# smart.net
KiCad netlist of a schematic drawn in Altium Designer
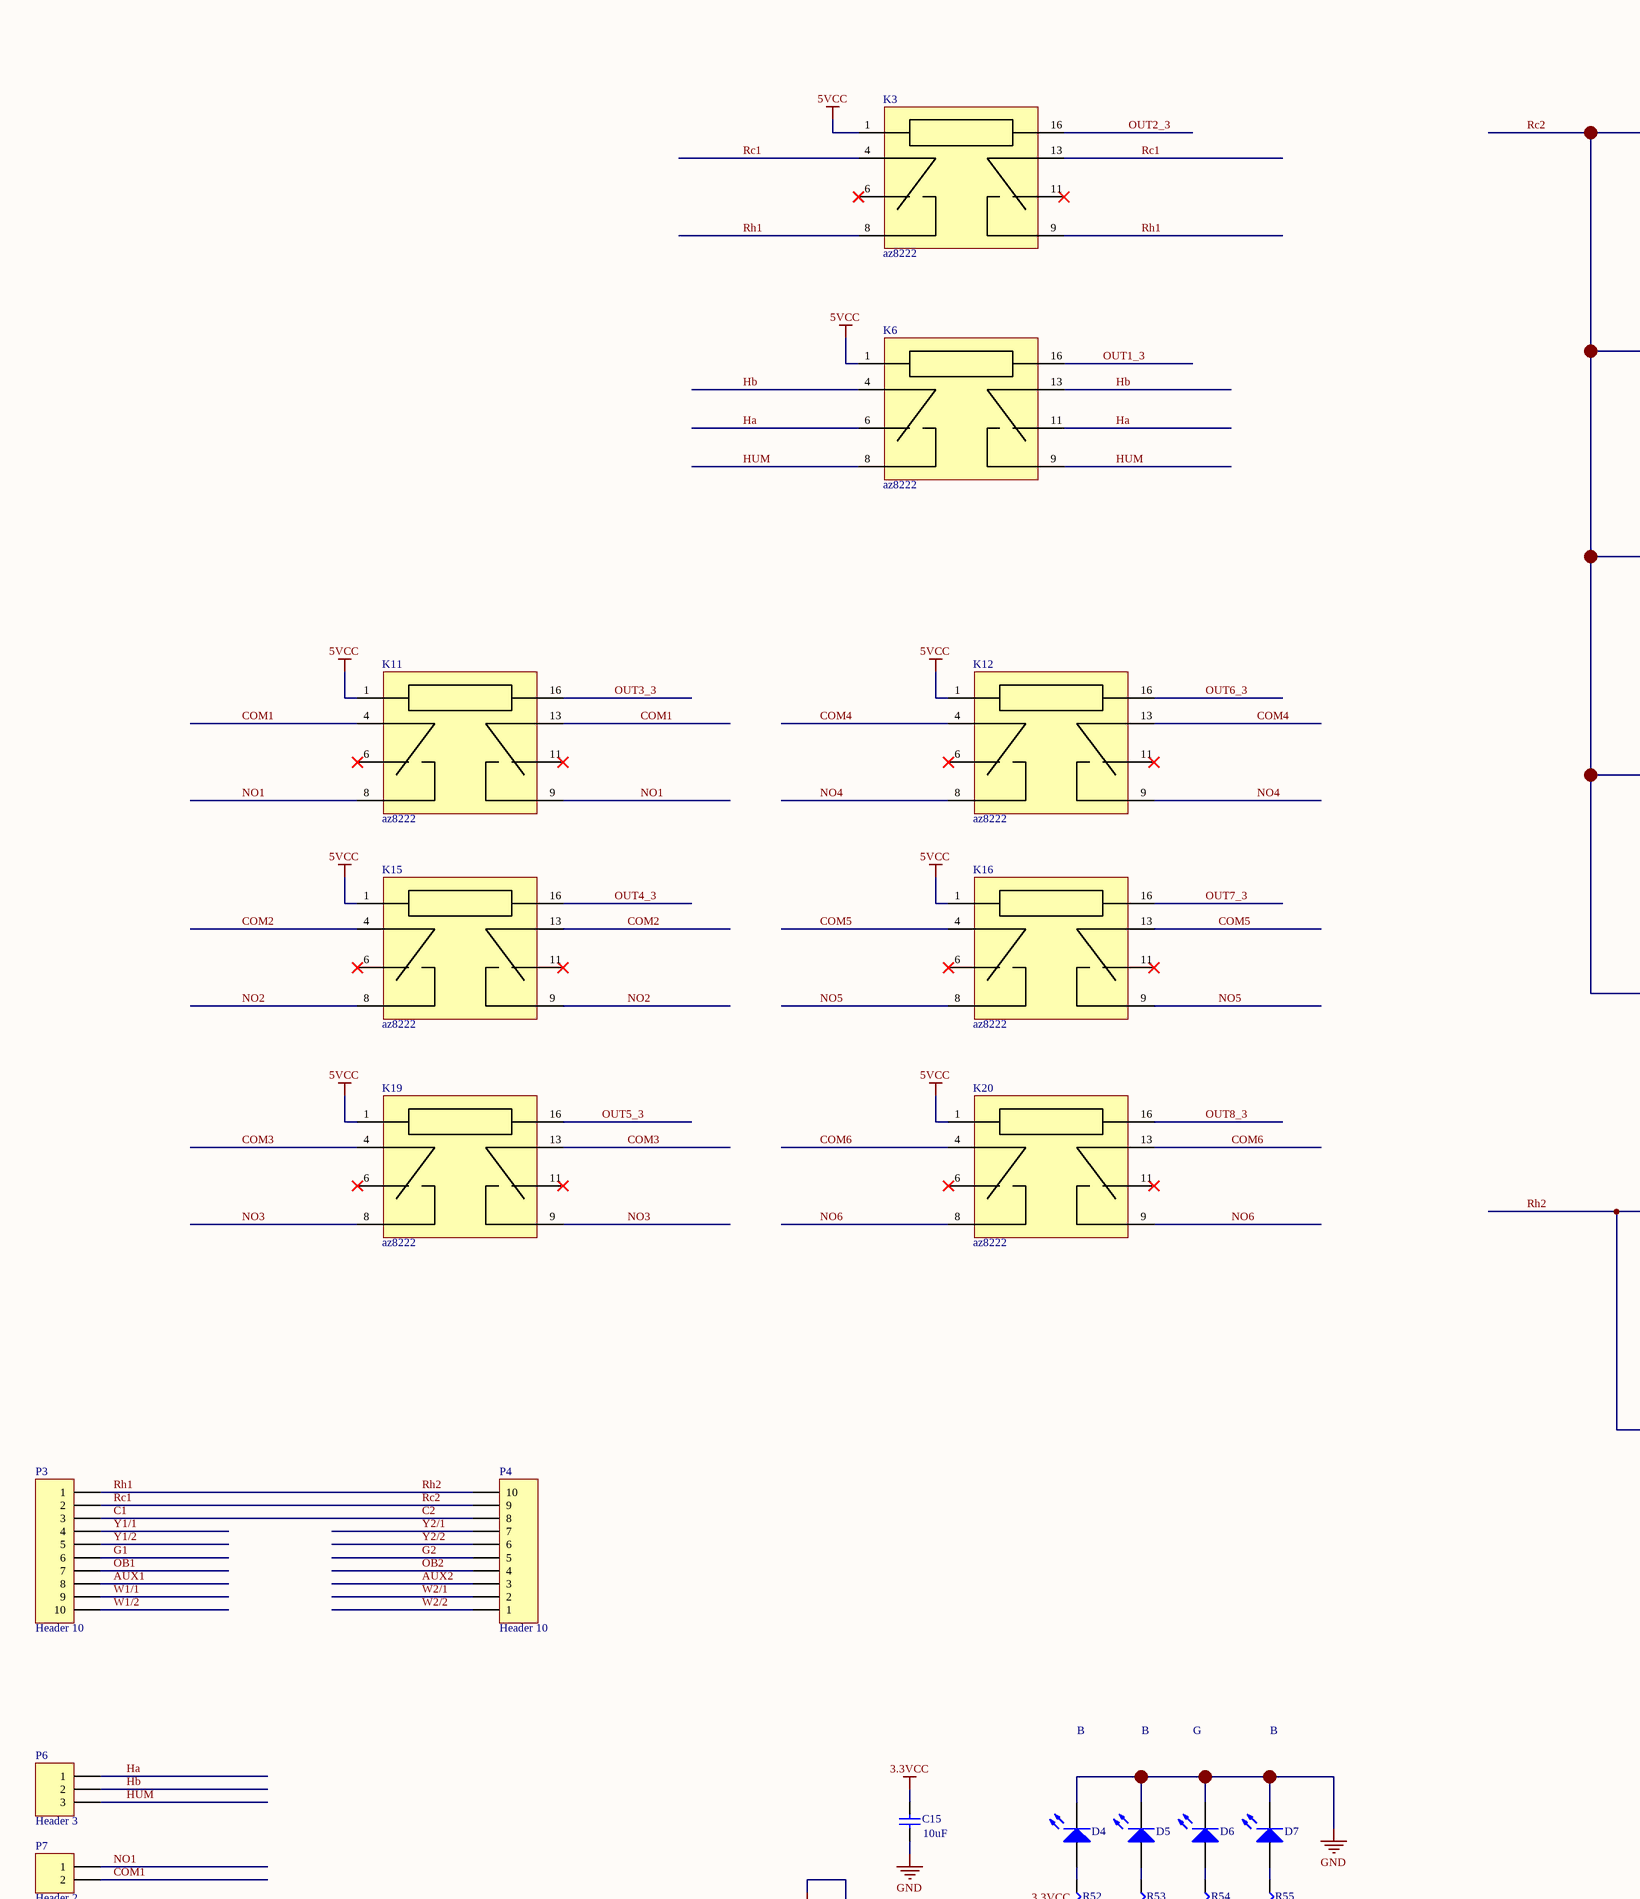
[diagram p0: smart.SchDoc, top left]
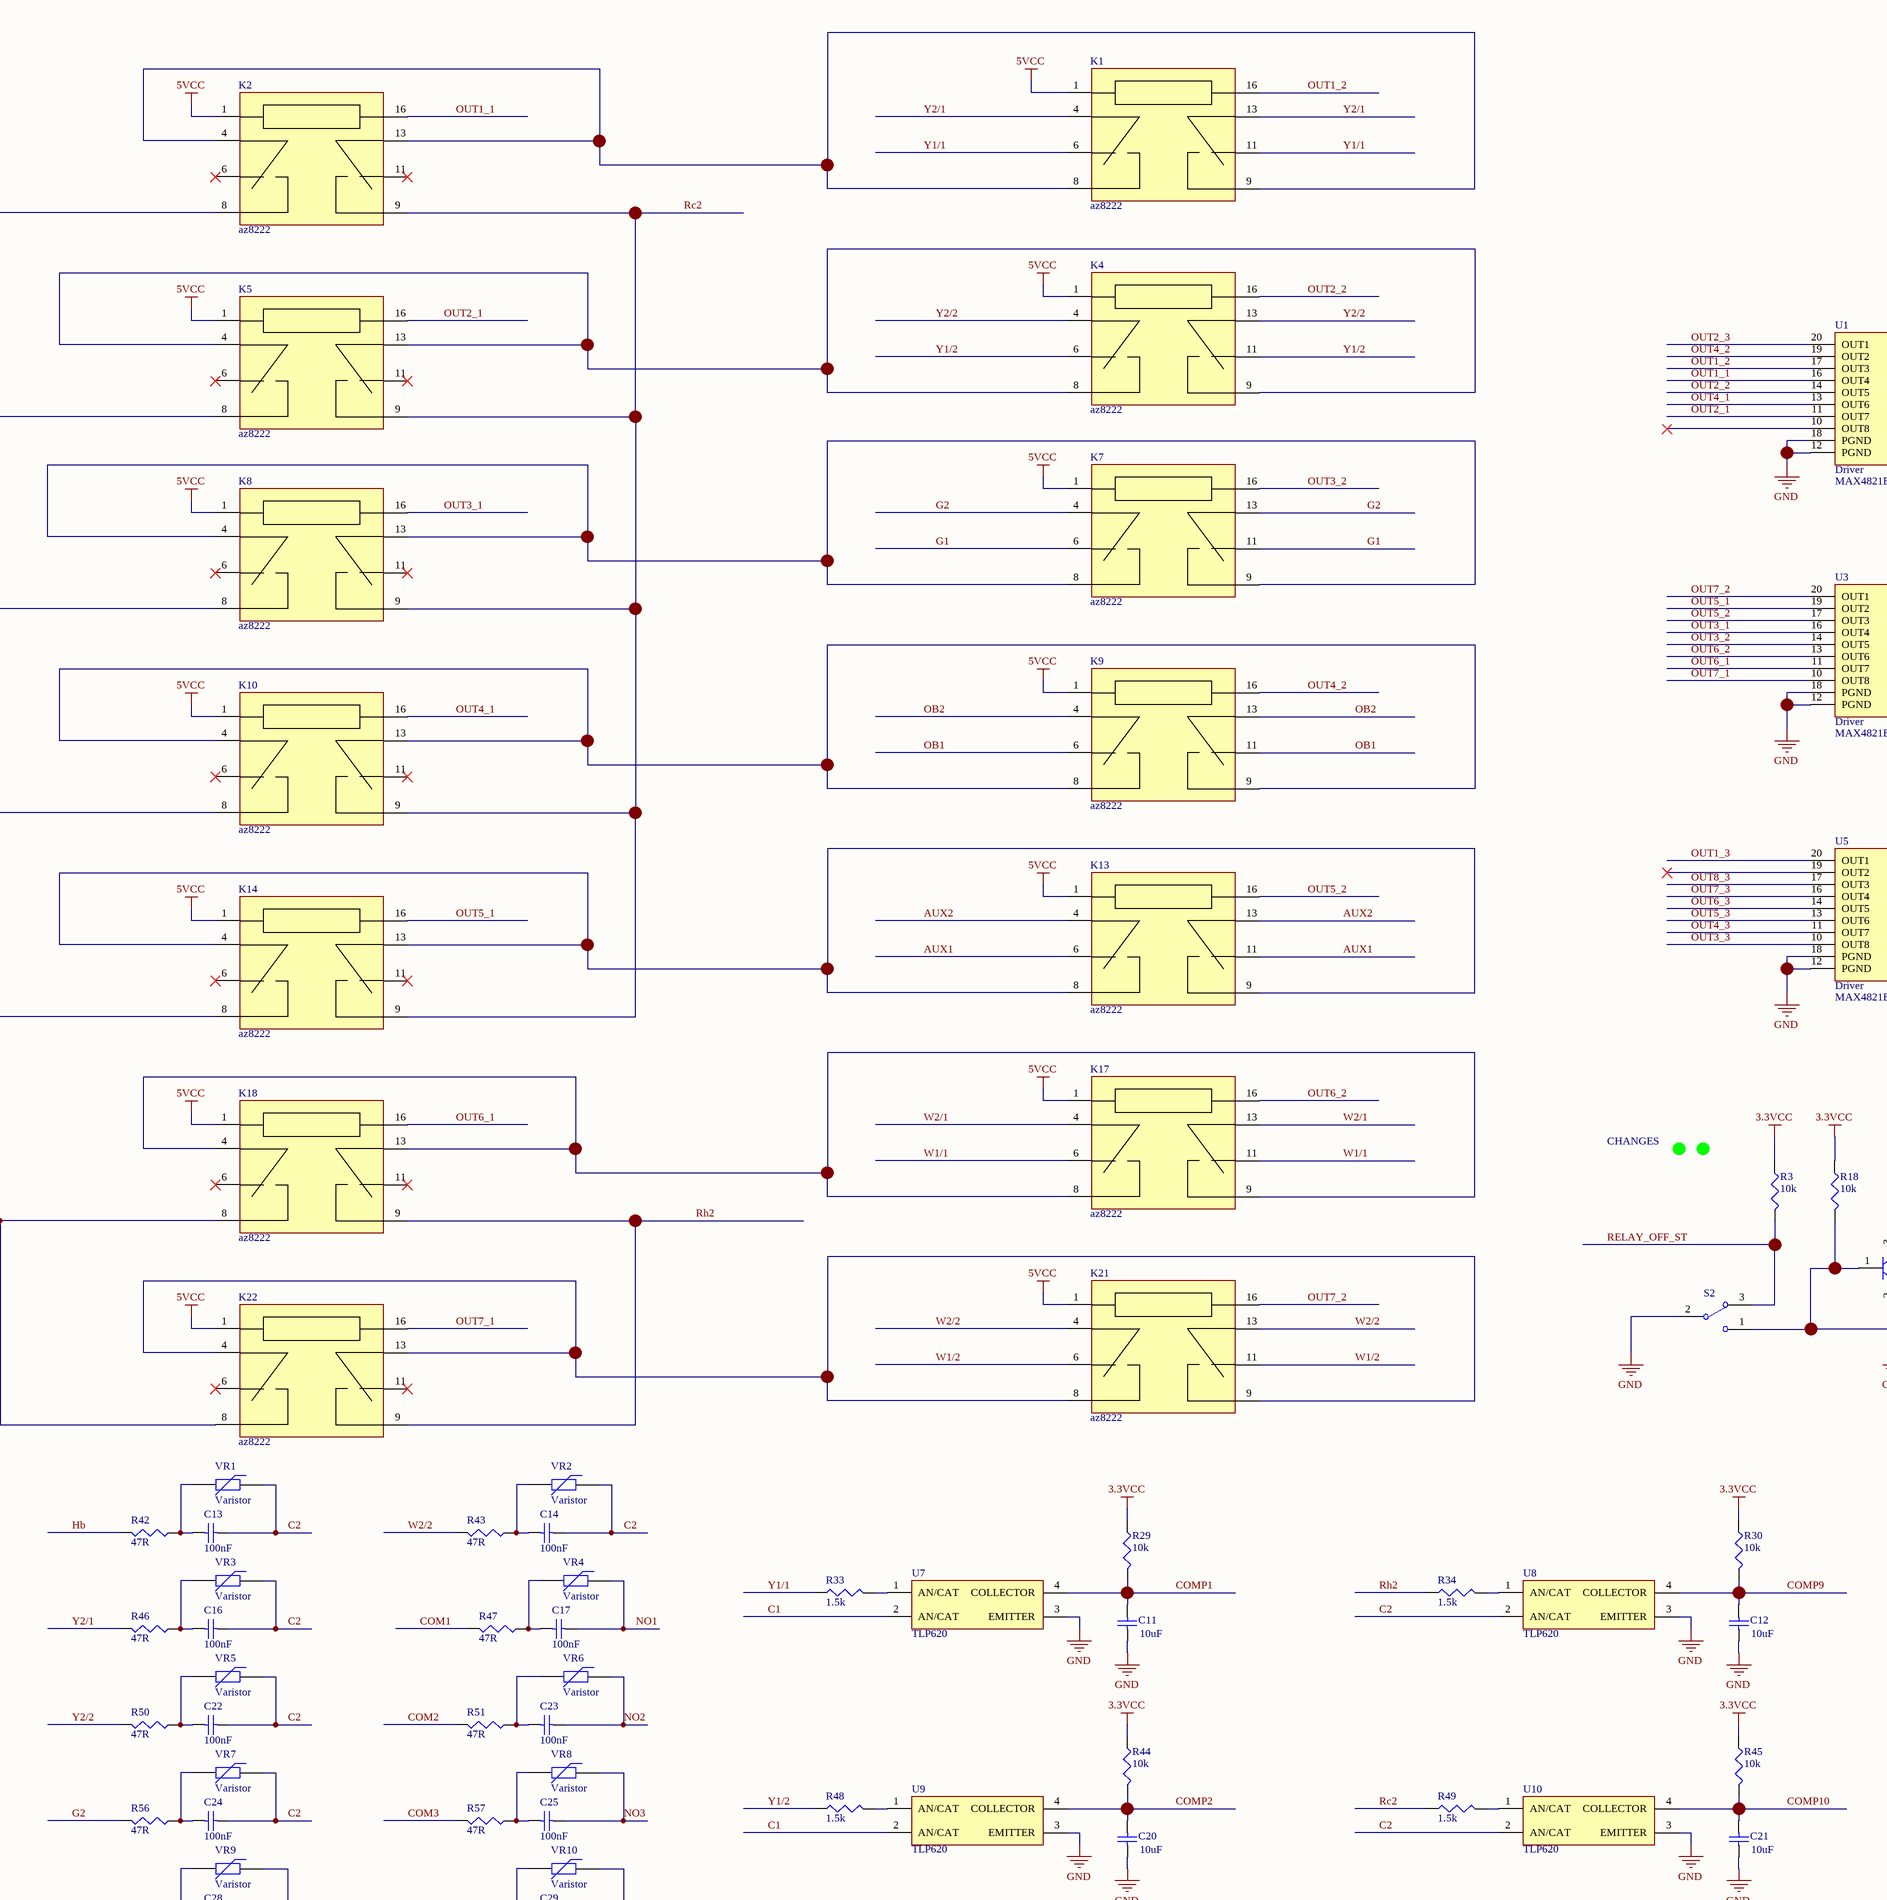
[diagram p1: smart.SchDoc, top middle]
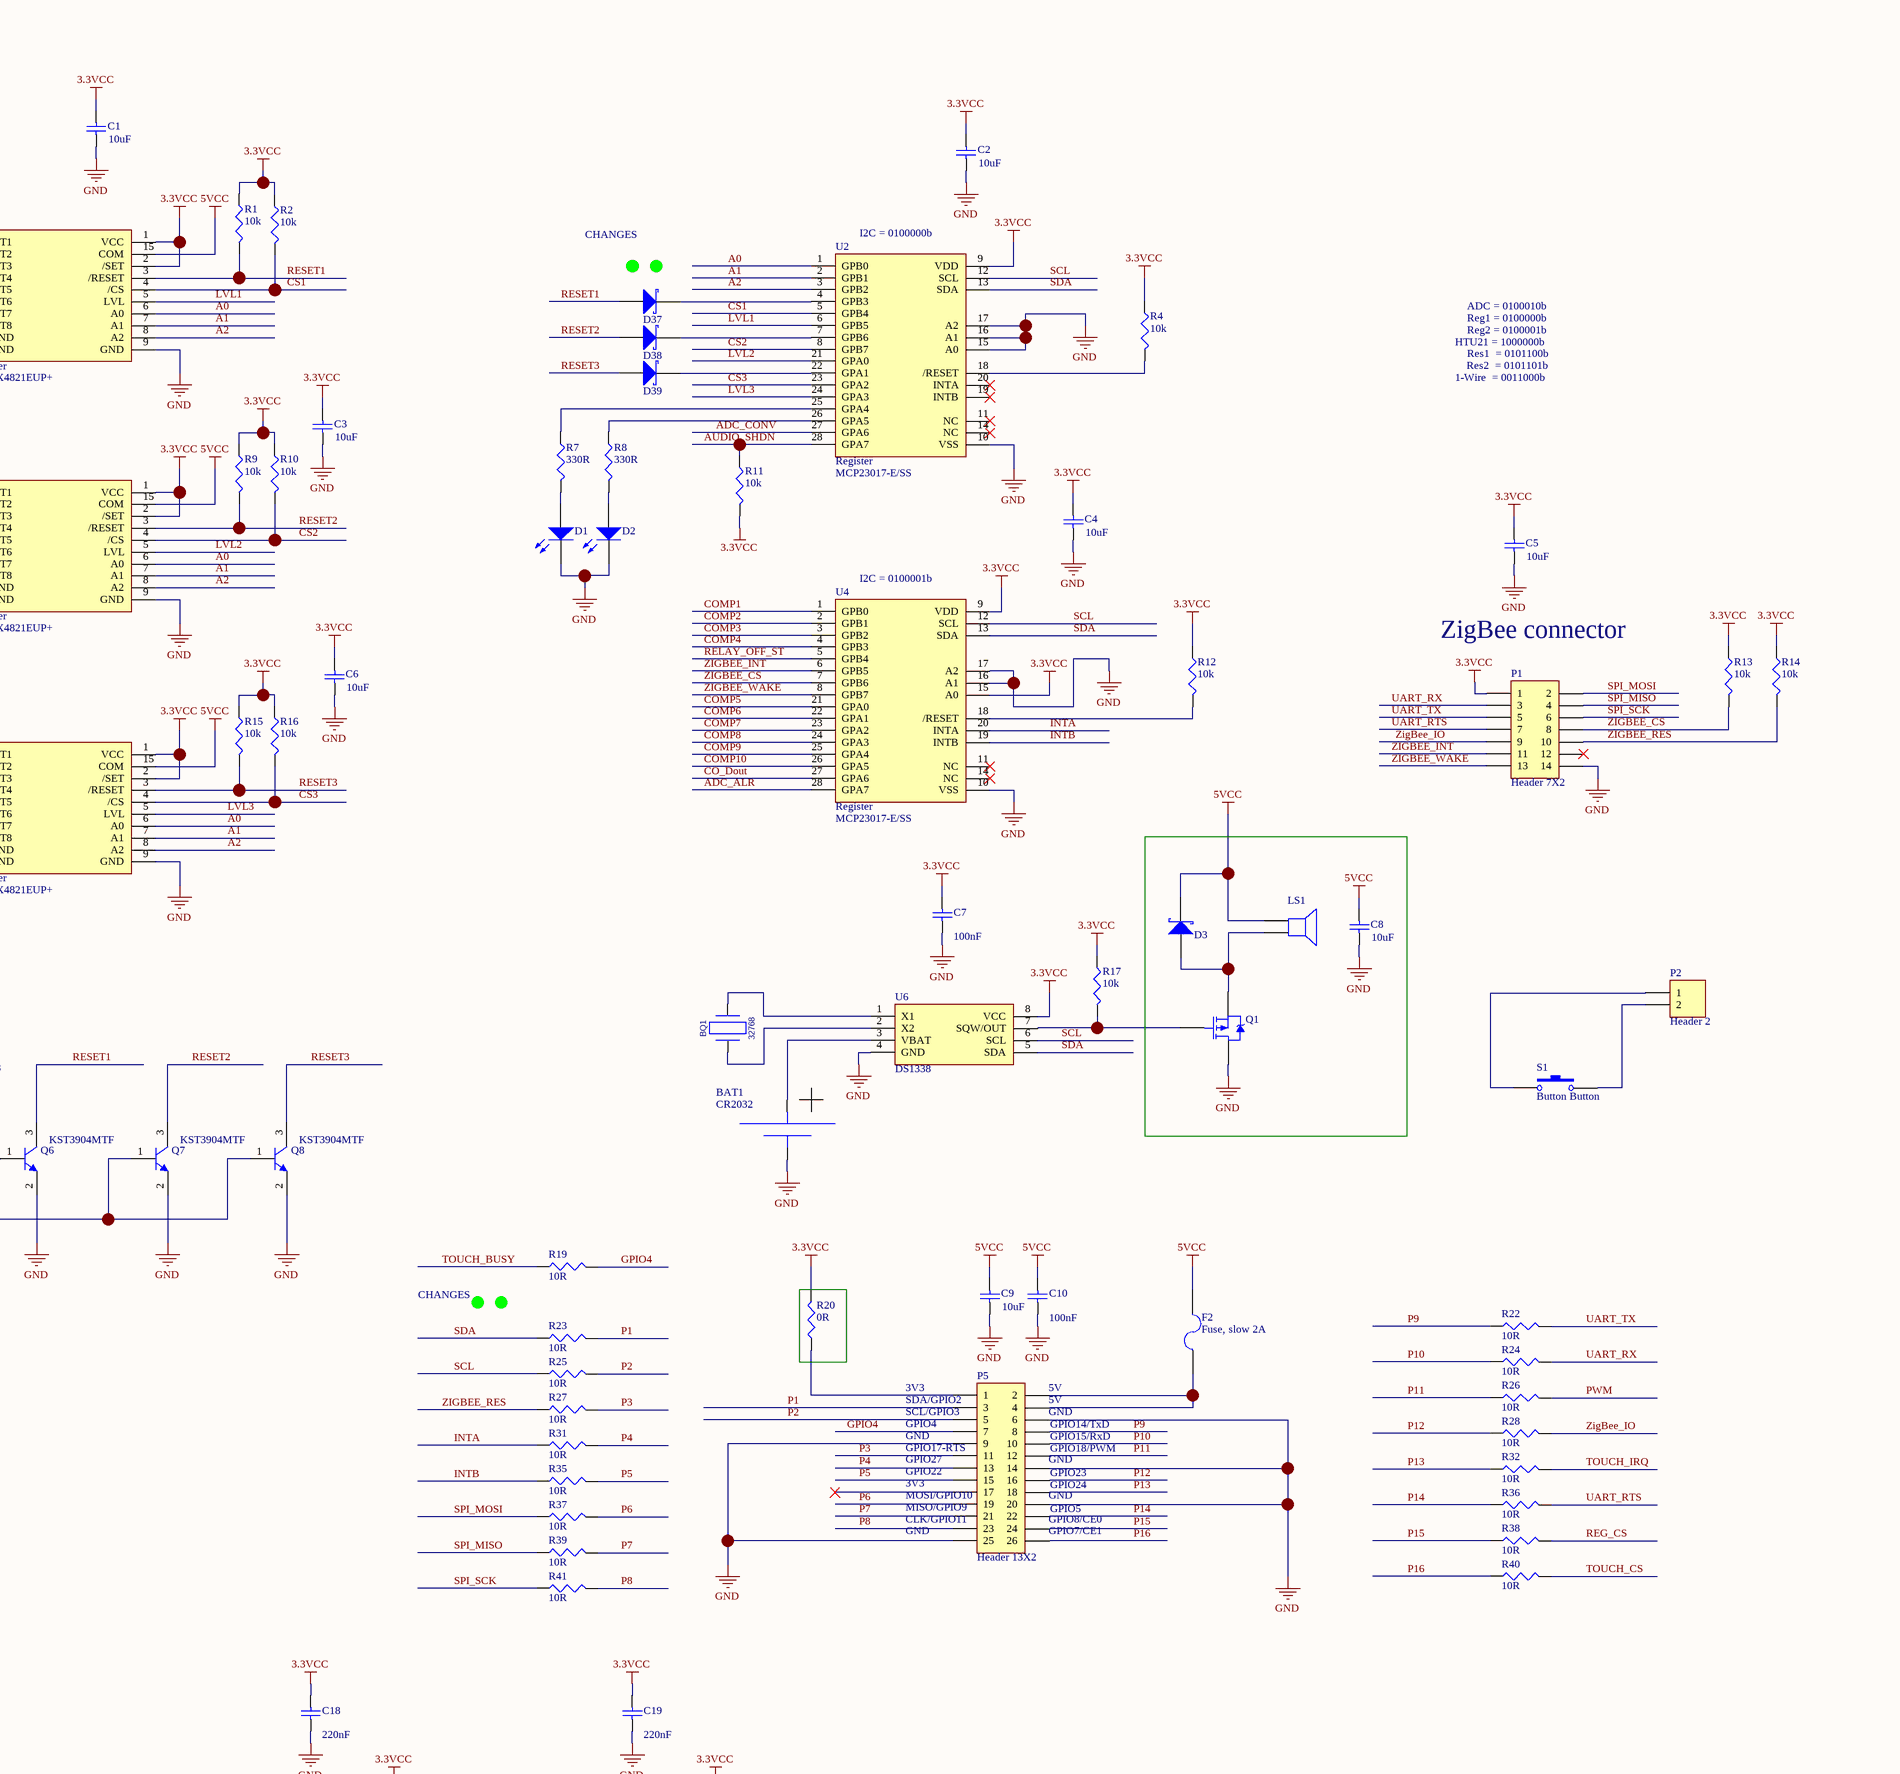
[diagram p2: smart.SchDoc, top right]
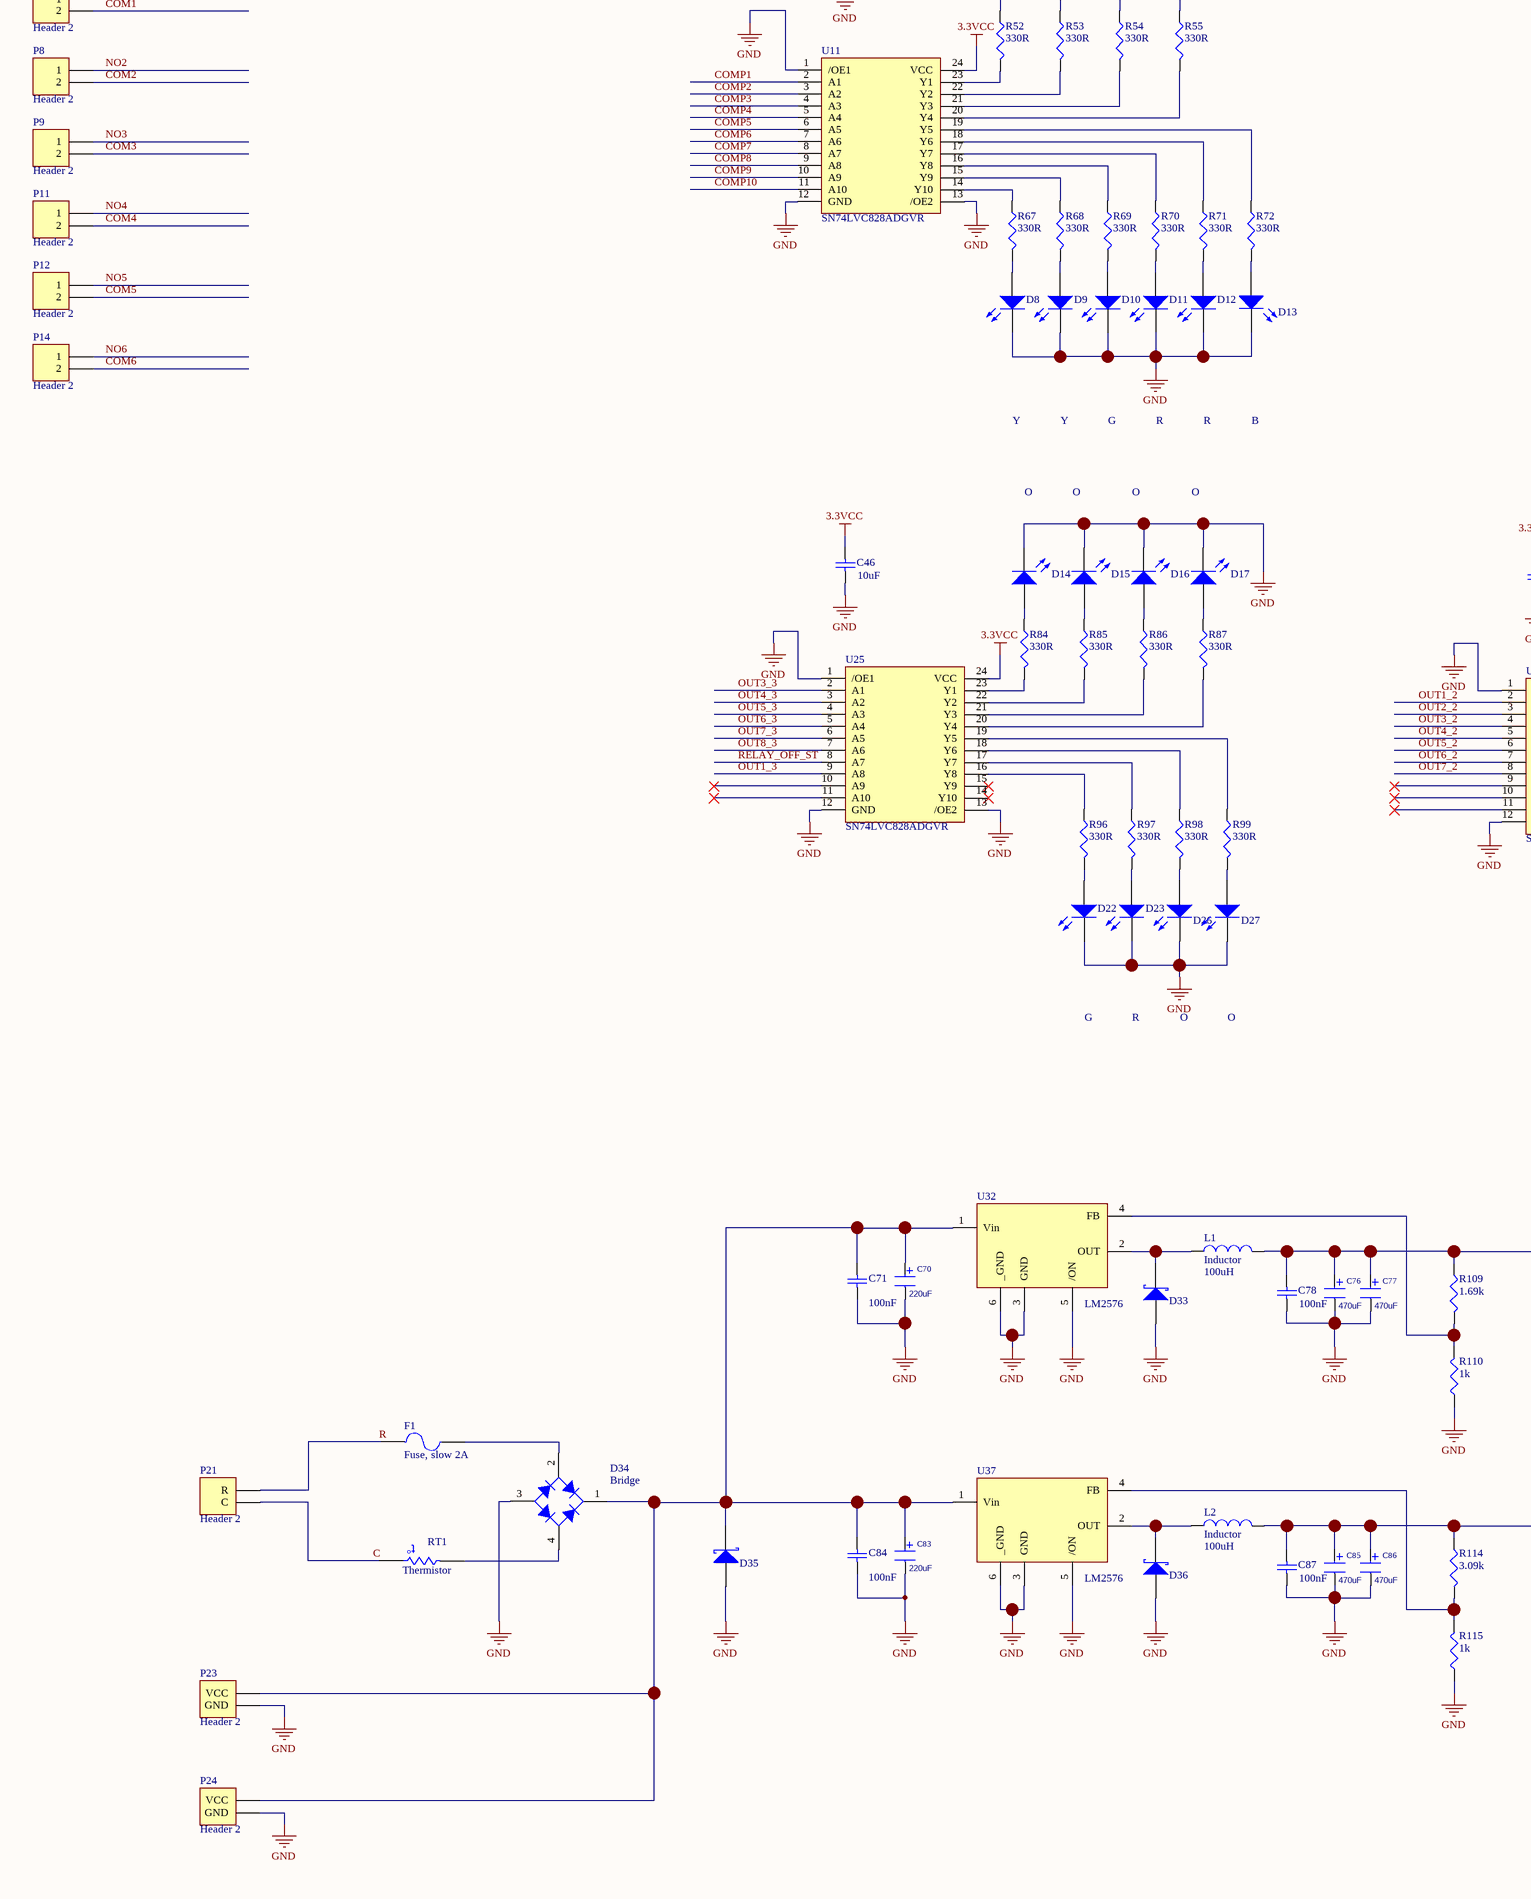
[diagram p3: smart.SchDoc, bottom left]
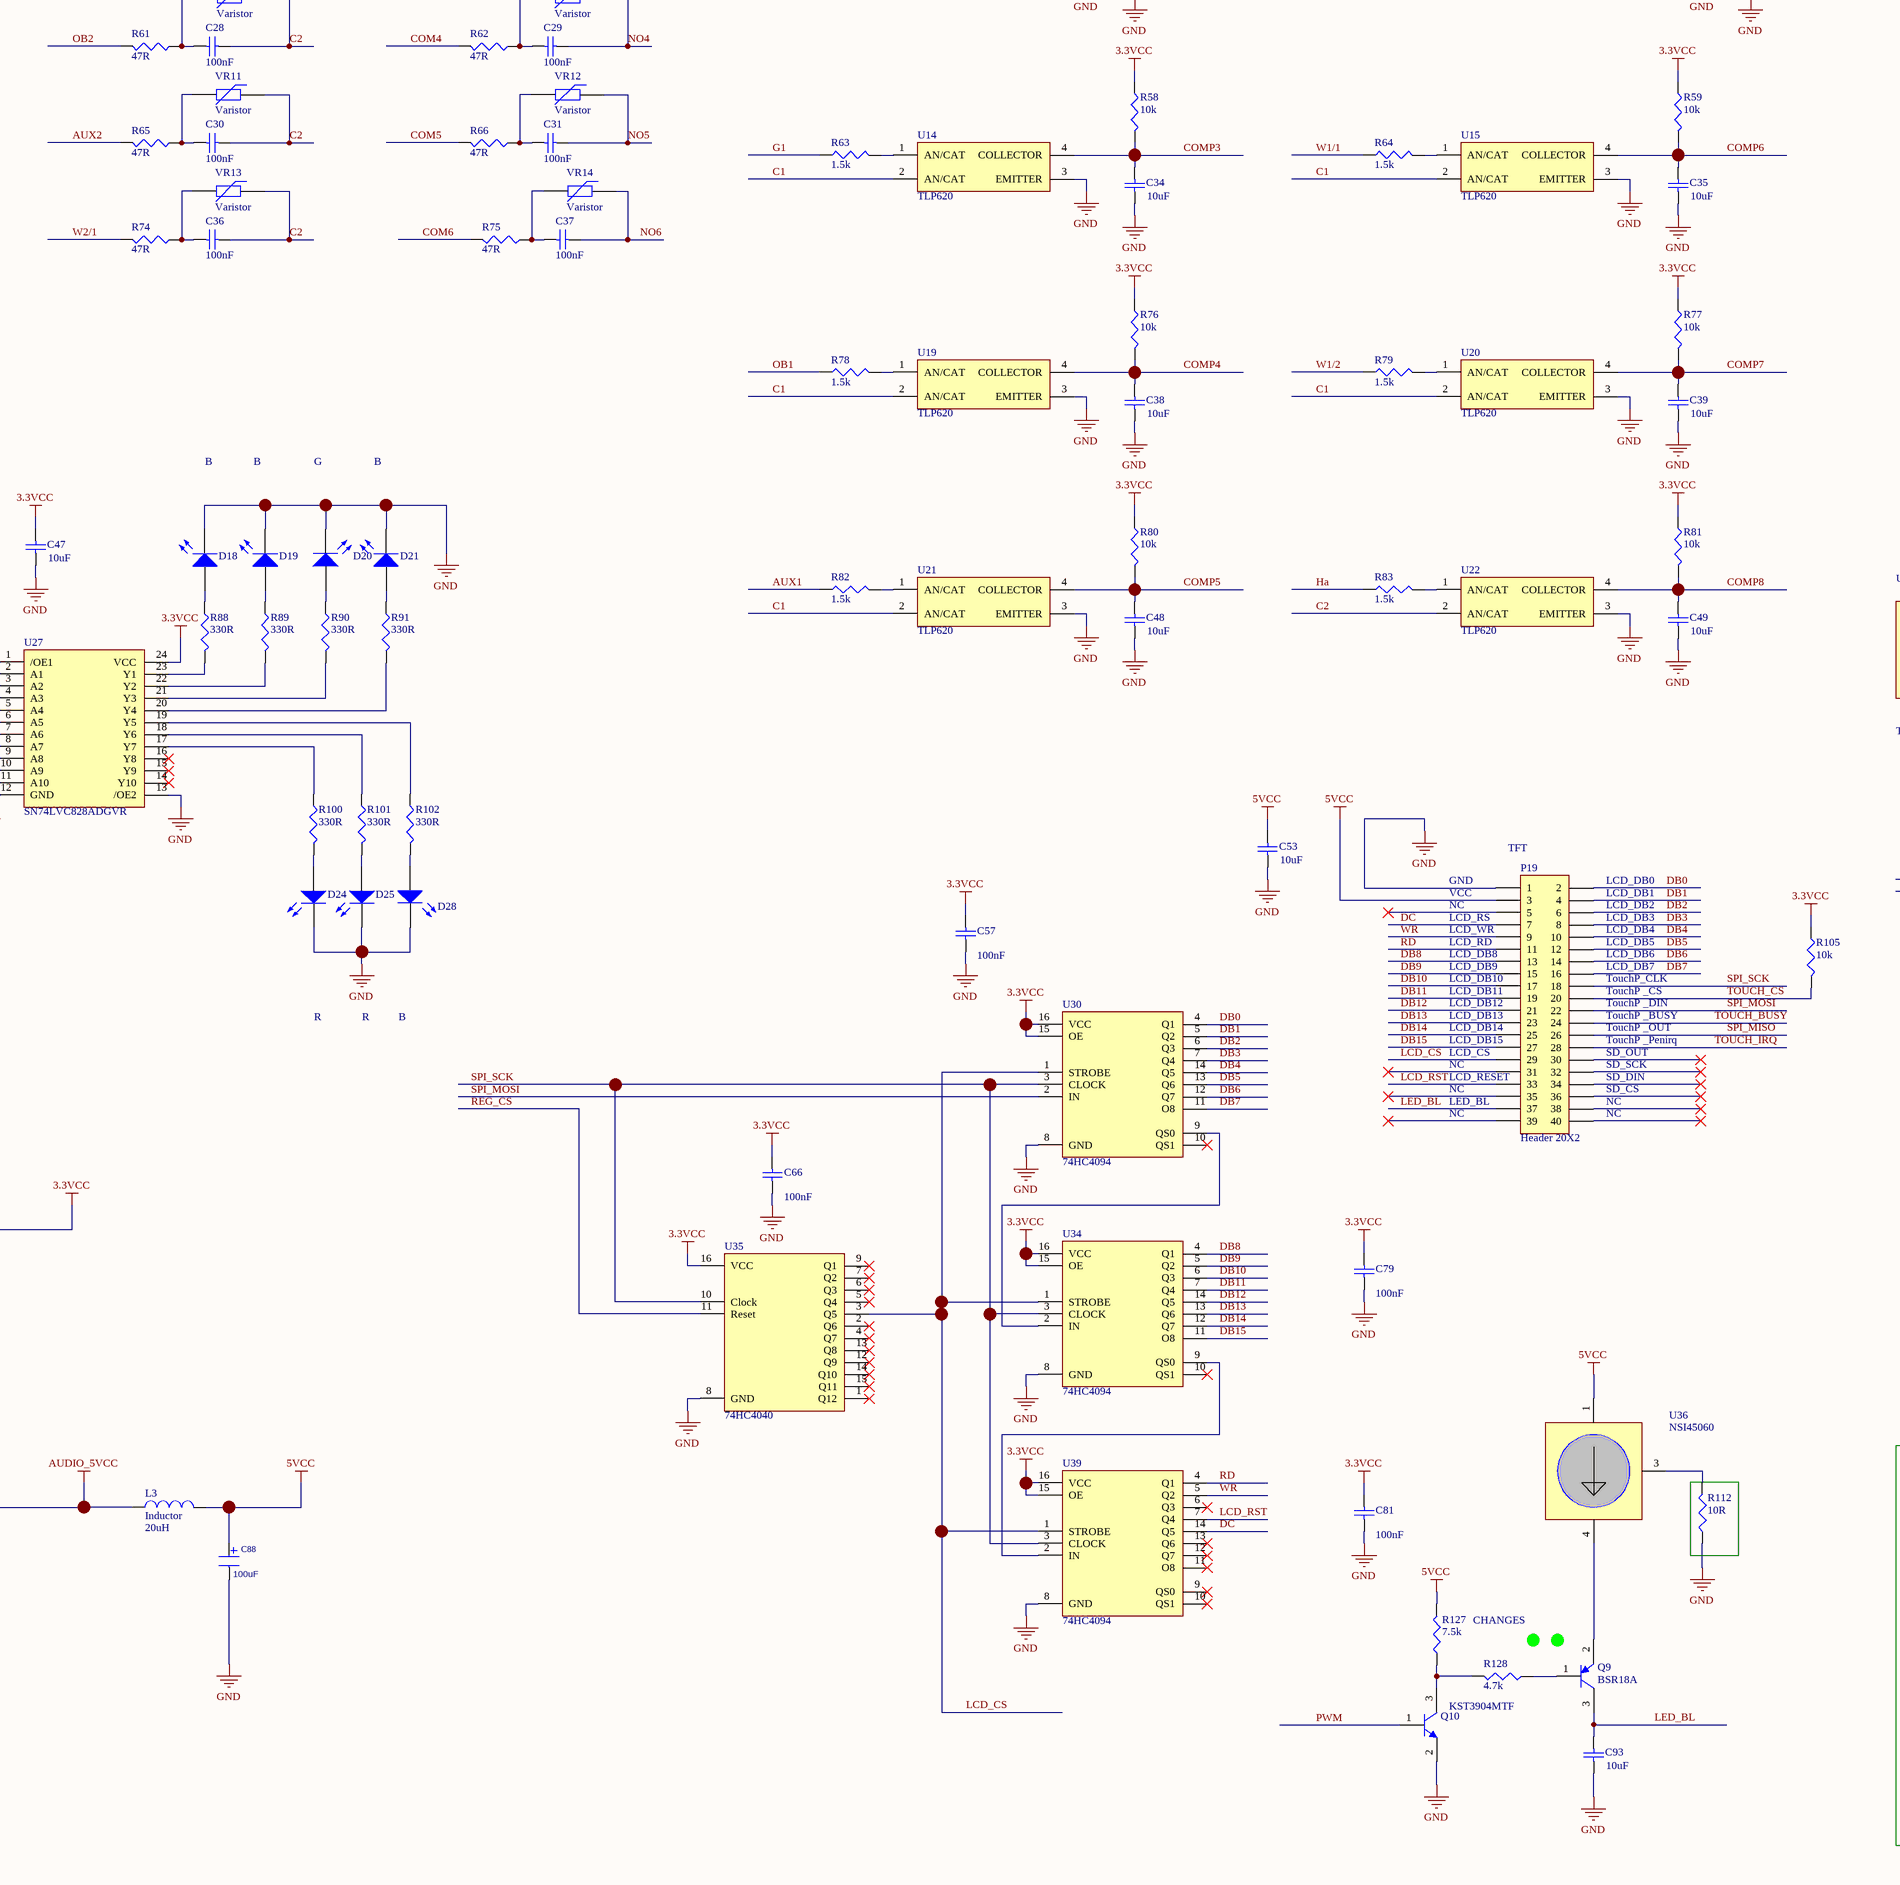
[diagram p4: smart.SchDoc, bottom middle]
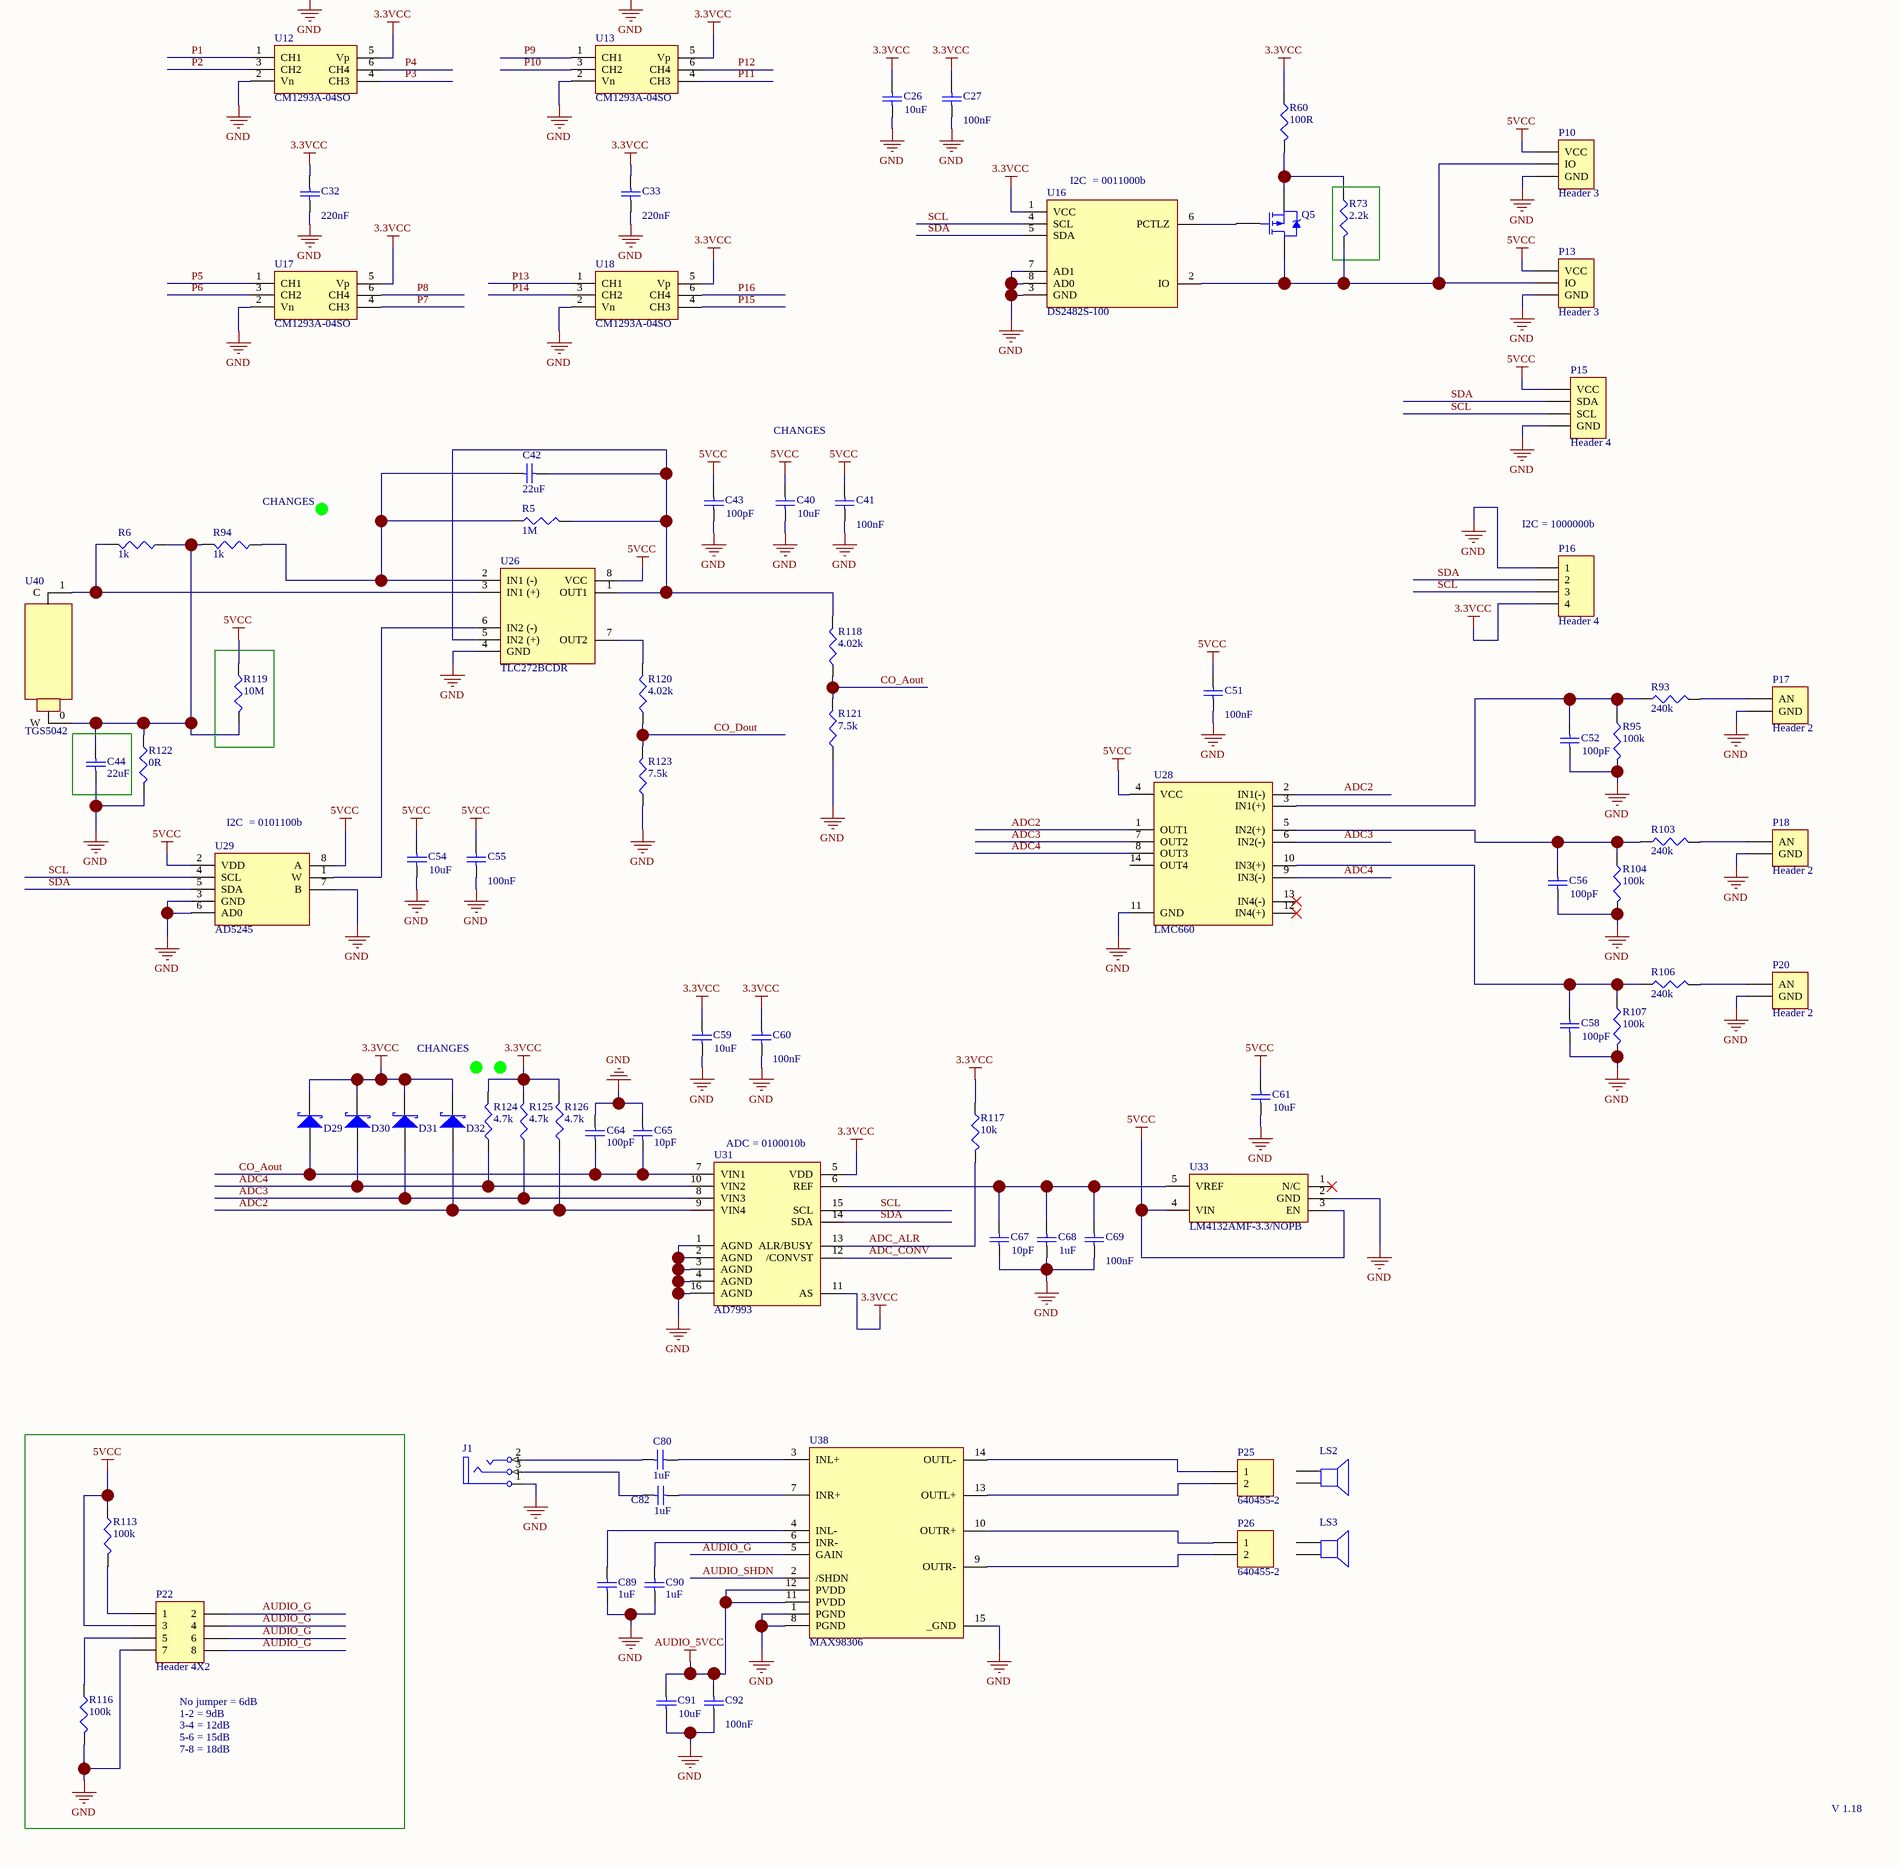
[diagram p5: smart.SchDoc, bottom right]

(export (version "E")
  (design (tool "Eeschema 10.0.6"))
  (components
    (comp (ref "BAT1")
      (value "CR2032")
      (footprint "BS-3")
      (description "Battery holder")
      (fields
        (field (name "MANUFACTURER PART NUMBER") "BH32T-C")
        (field (name "MANUFACTURER") "MPD (Memory Protection Devices)")
      )
      (libsource (lib "thermostat_main") (part "Battery"))
    )
    (comp (ref "BQ1")
      (value "32768")
      (footprint "SOJ4")
      (description "CRYSTAL 32.768KHZ 12.5PF SMD")
      (fields
        (field (name "MANUFACTURER PART NUMBER") "ABS25-32.768KHZ-T")
        (field (name "MANUFACTURER") "Abracon Corporation")
      )
      (libsource (lib "*") (part "6LC{colon}308C"))
    )
    (comp (ref "C1")
      (value "10uF")
      (footprint "C0805")
      (description "CAP CER 10UF 10V 20% X5R 0805")
      (fields
        (field (name "MANUFACTURER PART NUMBER") "C2012X5R1A106M125AB")
        (field (name "MANUFACTURER") "TDK Corporation")
      )
      (libsource (lib "") (part "Cap_1"))
    )
    (comp (ref "C2")
      (value "10uF")
      (footprint "C0805")
      (description "CAP CER 10UF 10V 20% X5R 0805")
      (fields
        (field (name "MANUFACTURER PART NUMBER") "C2012X5R1A106M125AB")
        (field (name "MANUFACTURER") "TDK Corporation")
      )
      (libsource (lib "") (part "Cap_1"))
    )
    (comp (ref "C3")
      (value "10uF")
      (footprint "C0805")
      (description "CAP CER 10UF 10V 20% X5R 0805")
      (fields
        (field (name "MANUFACTURER PART NUMBER") "C2012X5R1A106M125AB")
        (field (name "MANUFACTURER") "TDK Corporation")
      )
      (libsource (lib "") (part "Cap_1"))
    )
    (comp (ref "C4")
      (value "10uF")
      (footprint "C0805")
      (description "CAP CER 10UF 10V 20% X5R 0805")
      (fields
        (field (name "MANUFACTURER PART NUMBER") "C2012X5R1A106M125AB")
        (field (name "MANUFACTURER") "TDK Corporation")
      )
      (libsource (lib "") (part "Cap_1"))
    )
    (comp (ref "C5")
      (value "10uF")
      (footprint "C0805")
      (description "CAP CER 10UF 10V 20% X5R 0805")
      (fields
        (field (name "MANUFACTURER PART NUMBER") "C2012X5R1A106M125AB")
        (field (name "MANUFACTURER") "TDK Corporation")
      )
      (libsource (lib "") (part "Cap_1"))
    )
    (comp (ref "C6")
      (value "10uF")
      (footprint "C0805")
      (description "CAP CER 10UF 10V 20% X5R 0805")
      (fields
        (field (name "MANUFACTURER PART NUMBER") "C2012X5R1A106M125AB")
        (field (name "MANUFACTURER") "TDK Corporation")
      )
      (libsource (lib "") (part "Cap_1"))
    )
    (comp (ref "C7")
      (value "100nF")
      (footprint "0603")
      (description "CAP CER 0.1UF 50V Y5V 0603")
      (fields
        (field (name "MANUFACTURER PART NUMBER") "CC0603ZRY5V9BB104")
        (field (name "MANUFACTURER") "Yageo")
      )
      (libsource (lib "Miscellaneous Devices") (part "Cap"))
    )
    (comp (ref "C8")
      (value "10uF")
      (footprint "C0805")
      (description "CAP CER 10UF 10V 20% X5R 0805")
      (fields
        (field (name "MANUFACTURER PART NUMBER") "C2012X5R1A106M125AB")
        (field (name "MANUFACTURER") "TDK Corporation")
      )
      (libsource (lib "") (part "Cap_1"))
    )
    (comp (ref "C9")
      (value "10uF")
      (footprint "C0805")
      (description "CAP CER 10UF 10V 20% X5R 0805")
      (fields
        (field (name "MANUFACTURER PART NUMBER") "C2012X5R1A106M125AB")
        (field (name "MANUFACTURER") "TDK Corporation")
      )
      (libsource (lib "") (part "Cap_1"))
    )
    (comp (ref "C10")
      (value "100nF")
      (footprint "0603")
      (description "CAP CER 0.1UF 50V Y5V 0603")
      (fields
        (field (name "MANUFACTURER PART NUMBER") "CC0603ZRY5V9BB104")
        (field (name "MANUFACTURER") "Yageo")
      )
      (libsource (lib "Miscellaneous Devices") (part "Cap"))
    )
    (comp (ref "C11")
      (value "10uF")
      (footprint "C0805")
      (description "CAP CER 10UF 10V 20% X5R 0805")
      (fields
        (field (name "MANUFACTURER PART NUMBER") "C2012X5R1A106M125AB")
        (field (name "MANUFACTURER") "TDK Corporation")
      )
      (libsource (lib "") (part "Cap_1"))
    )
    (comp (ref "C12")
      (value "10uF")
      (footprint "C0805")
      (description "CAP CER 10UF 10V 20% X5R 0805")
      (fields
        (field (name "MANUFACTURER PART NUMBER") "C2012X5R1A106M125AB")
        (field (name "MANUFACTURER") "TDK Corporation")
      )
      (libsource (lib "") (part "Cap_1"))
    )
    (comp (ref "C13")
      (value "100nF")
      (footprint "B32521C3104K")
      (description "CAP FILM 0.1UF 250VDC RADIAL")
      (fields
        (field (name "MANUFACTURER PART NUMBER") "B32521C3104K")
        (field (name "MANUFACTURER") "EPCOS Inc")
      )
      (libsource (lib "Miscellaneous Devices") (part "Cap"))
    )
    (comp (ref "C14")
      (value "100nF")
      (footprint "B32521C3104K")
      (description "CAP FILM 0.1UF 250VDC RADIAL")
      (fields
        (field (name "MANUFACTURER") "EPCOS Inc")
        (field (name "MANUFACTURER PART NUMBER") "B32521C3104K")
      )
      (libsource (lib "Miscellaneous Devices") (part "Cap"))
    )
    (comp (ref "C15")
      (value "10uF")
      (footprint "C0805")
      (description "CAP CER 10UF 10V 20% X5R 0805")
      (fields
        (field (name "MANUFACTURER PART NUMBER") "C2012X5R1A106M125AB")
        (field (name "MANUFACTURER") "TDK Corporation")
      )
      (libsource (lib "") (part "Cap_1"))
    )
    (comp (ref "C16")
      (value "100nF")
      (footprint "B32521C3104K")
      (description "CAP FILM 0.1UF 250VDC RADIAL")
      (fields
        (field (name "MANUFACTURER PART NUMBER") "B32521C3104K")
        (field (name "MANUFACTURER") "EPCOS Inc")
      )
      (libsource (lib "Miscellaneous Devices") (part "Cap"))
    )
    (comp (ref "C17")
      (value "100nF")
      (footprint "B32521C3104K")
      (description "CAP FILM 0.1UF 250VDC RADIAL")
      (fields
        (field (name "MANUFACTURER") "EPCOS Inc")
        (field (name "MANUFACTURER PART NUMBER") "B32521C3104K")
      )
      (libsource (lib "Miscellaneous Devices") (part "Cap"))
    )
    (comp (ref "C18")
      (value "220nF")
      (footprint "0603")
      (description "CAP CER 0.22UF 50V 10% X7R 0603")
      (fields
        (field (name "MANUFACTURER PART NUMBER") "C1608X7R1H224K080AB")
        (field (name "MANUFACTURER") "TDK Corporation")
      )
      (libsource (lib "Miscellaneous Devices") (part "Cap"))
    )
    (comp (ref "C19")
      (value "220nF")
      (footprint "0603")
      (description "CAP CER 0.22UF 50V 10% X7R 0603")
      (fields
        (field (name "MANUFACTURER PART NUMBER") "C1608X7R1H224K080AB")
        (field (name "MANUFACTURER") "TDK Corporation")
      )
      (libsource (lib "Miscellaneous Devices") (part "Cap"))
    )
    (comp (ref "C20")
      (value "10uF")
      (footprint "C0805")
      (description "CAP CER 10UF 10V 20% X5R 0805")
      (fields
        (field (name "MANUFACTURER PART NUMBER") "C2012X5R1A106M125AB")
        (field (name "MANUFACTURER") "TDK Corporation")
      )
      (libsource (lib "") (part "Cap_1"))
    )
    (comp (ref "C21")
      (value "10uF")
      (footprint "C0805")
      (description "CAP CER 10UF 10V 20% X5R 0805")
      (fields
        (field (name "MANUFACTURER PART NUMBER") "C2012X5R1A106M125AB")
        (field (name "MANUFACTURER") "TDK Corporation")
      )
      (libsource (lib "") (part "Cap_1"))
    )
    (comp (ref "C22")
      (value "100nF")
      (footprint "B32521C3104K")
      (description "CAP FILM 0.1UF 250VDC RADIAL")
      (fields
        (field (name "MANUFACTURER") "EPCOS Inc")
        (field (name "MANUFACTURER PART NUMBER") "B32521C3104K")
      )
      (libsource (lib "Miscellaneous Devices") (part "Cap"))
    )
    (comp (ref "C23")
      (value "100nF")
      (footprint "B32521C3104K")
      (description "CAP FILM 0.1UF 250VDC RADIAL")
      (fields
        (field (name "MANUFACTURER") "EPCOS Inc")
        (field (name "MANUFACTURER PART NUMBER") "B32521C3104K")
      )
      (libsource (lib "Miscellaneous Devices") (part "Cap"))
    )
    (comp (ref "C24")
      (value "100nF")
      (footprint "B32521C3104K")
      (description "CAP FILM 0.1UF 250VDC RADIAL")
      (fields
        (field (name "MANUFACTURER") "EPCOS Inc")
        (field (name "MANUFACTURER PART NUMBER") "B32521C3104K")
      )
      (libsource (lib "Miscellaneous Devices") (part "Cap"))
    )
    (comp (ref "C25")
      (value "100nF")
      (footprint "B32521C3104K")
      (description "CAP FILM 0.1UF 250VDC RADIAL")
      (fields
        (field (name "MANUFACTURER") "EPCOS Inc")
        (field (name "MANUFACTURER PART NUMBER") "B32521C3104K")
      )
      (libsource (lib "Miscellaneous Devices") (part "Cap"))
    )
    (comp (ref "C26")
      (value "10uF")
      (footprint "C0805")
      (description "CAP CER 10UF 10V 20% X5R 0805")
      (fields
        (field (name "MANUFACTURER PART NUMBER") "C2012X5R1A106M125AB")
        (field (name "MANUFACTURER") "TDK Corporation")
      )
      (libsource (lib "") (part "Cap_1"))
    )
    (comp (ref "C27")
      (value "100nF")
      (footprint "0603")
      (description "CAP CER 0.1UF 50V Y5V 0603")
      (fields
        (field (name "MANUFACTURER PART NUMBER") "CC0603ZRY5V9BB104")
        (field (name "MANUFACTURER") "Yageo")
      )
      (libsource (lib "Miscellaneous Devices") (part "Cap"))
    )
    (comp (ref "C28")
      (value "100nF")
      (footprint "B32521C3104K")
      (description "CAP FILM 0.1UF 250VDC RADIAL")
      (fields
        (field (name "MANUFACTURER") "EPCOS Inc")
        (field (name "MANUFACTURER PART NUMBER") "B32521C3104K")
      )
      (libsource (lib "Miscellaneous Devices") (part "Cap"))
    )
    (comp (ref "C29")
      (value "100nF")
      (footprint "B32521C3104K")
      (description "CAP FILM 0.1UF 250VDC RADIAL")
      (fields
        (field (name "MANUFACTURER") "EPCOS Inc")
        (field (name "MANUFACTURER PART NUMBER") "B32521C3104K")
      )
      (libsource (lib "Miscellaneous Devices") (part "Cap"))
    )
    (comp (ref "C30")
      (value "100nF")
      (footprint "B32521C3104K")
      (description "CAP FILM 0.1UF 250VDC RADIAL")
      (fields
        (field (name "MANUFACTURER") "EPCOS Inc")
        (field (name "MANUFACTURER PART NUMBER") "B32521C3104K")
      )
      (libsource (lib "Miscellaneous Devices") (part "Cap"))
    )
    (comp (ref "C31")
      (value "100nF")
      (footprint "B32521C3104K")
      (description "CAP FILM 0.1UF 250VDC RADIAL")
      (fields
        (field (name "MANUFACTURER") "EPCOS Inc")
        (field (name "MANUFACTURER PART NUMBER") "B32521C3104K")
      )
      (libsource (lib "Miscellaneous Devices") (part "Cap"))
    )
    (comp (ref "C32")
      (value "220nF")
      (footprint "0603")
      (description "CAP CER 0.22UF 50V 10% X7R 0603")
      (fields
        (field (name "MANUFACTURER PART NUMBER") "C1608X7R1H224K080AB")
        (field (name "MANUFACTURER") "TDK Corporation")
      )
      (libsource (lib "Miscellaneous Devices") (part "Cap"))
    )
    (comp (ref "C33")
      (value "220nF")
      (footprint "0603")
      (description "CAP CER 0.22UF 50V 10% X7R 0603")
      (fields
        (field (name "MANUFACTURER PART NUMBER") "C1608X7R1H224K080AB")
        (field (name "MANUFACTURER") "TDK Corporation")
      )
      (libsource (lib "Miscellaneous Devices") (part "Cap"))
    )
    (comp (ref "C34")
      (value "10uF")
      (footprint "C0805")
      (description "CAP CER 10UF 10V 20% X5R 0805")
      (fields
        (field (name "MANUFACTURER PART NUMBER") "C2012X5R1A106M125AB")
        (field (name "MANUFACTURER") "TDK Corporation")
      )
      (libsource (lib "") (part "Cap_1"))
    )
    (comp (ref "C35")
      (value "10uF")
      (footprint "C0805")
      (description "CAP CER 10UF 10V 20% X5R 0805")
      (fields
        (field (name "MANUFACTURER PART NUMBER") "C2012X5R1A106M125AB")
        (field (name "MANUFACTURER") "TDK Corporation")
      )
      (libsource (lib "") (part "Cap_1"))
    )
    (comp (ref "C36")
      (value "100nF")
      (footprint "B32521C3104K")
      (description "CAP FILM 0.1UF 250VDC RADIAL")
      (fields
        (field (name "MANUFACTURER") "EPCOS Inc")
        (field (name "MANUFACTURER PART NUMBER") "B32521C3104K")
      )
      (libsource (lib "Miscellaneous Devices") (part "Cap"))
    )
    (comp (ref "C37")
      (value "100nF")
      (footprint "B32521C3104K")
      (description "CAP FILM 0.1UF 250VDC RADIAL")
      (fields
        (field (name "MANUFACTURER") "EPCOS Inc")
        (field (name "MANUFACTURER PART NUMBER") "B32521C3104K")
      )
      (libsource (lib "Miscellaneous Devices") (part "Cap"))
    )
    (comp (ref "C38")
      (value "10uF")
      (footprint "C0805")
      (description "CAP CER 10UF 10V 20% X5R 0805")
      (fields
        (field (name "MANUFACTURER PART NUMBER") "C2012X5R1A106M125AB")
        (field (name "MANUFACTURER") "TDK Corporation")
      )
      (libsource (lib "") (part "Cap_1"))
    )
    (comp (ref "C39")
      (value "10uF")
      (footprint "C0805")
      (description "CAP CER 10UF 10V 20% X5R 0805")
      (fields
        (field (name "MANUFACTURER PART NUMBER") "C2012X5R1A106M125AB")
        (field (name "MANUFACTURER") "TDK Corporation")
      )
      (libsource (lib "") (part "Cap_1"))
    )
    (comp (ref "C40")
      (value "10uF")
      (footprint "C0805")
      (description "CAP CER 10UF 10V 20% X5R 0805")
      (fields
        (field (name "MANUFACTURER PART NUMBER") "C2012X5R1A106M125AB")
        (field (name "MANUFACTURER") "TDK Corporation")
      )
      (libsource (lib "") (part "Cap_1"))
    )
    (comp (ref "C41")
      (value "100nF")
      (footprint "0603")
      (description "CAP CER 0.1UF 50V Y5V 0603")
      (fields
        (field (name "MANUFACTURER PART NUMBER") "CC0603ZRY5V9BB104")
        (field (name "MANUFACTURER") "Yageo")
      )
      (libsource (lib "Miscellaneous Devices") (part "Cap"))
    )
    (comp (ref "C42")
      (value "22uF")
      (footprint "0603")
      (description "CAP CER 22UF 6.3V 10% X5R 0603")
      (fields
        (field (name "MANUFACTURER PART NUMBER") "CL10A226KQ8NRNE")
        (field (name "MANUFACTURER") "Samsung Electro-Mechanics America, Inc")
      )
      (libsource (lib "Miscellaneous Devices") (part "Cap"))
    )
    (comp (ref "C43")
      (value "100pF")
      (footprint "0603")
      (description "CAP CER 100PF 100V 5% NP0 0603")
      (fields
        (field (name "MANUFACTURER PART NUMBER") "CL10C101JC81PNC")
        (field (name "MANUFACTURER") "Samsung Electro-Mechanics America, Inc")
      )
      (libsource (lib "Miscellaneous Devices") (part "Cap"))
    )
    (comp (ref "C44")
      (value "22uF")
      (footprint "0603")
      (description "CAP CER 22UF 6.3V 10% X5R 0603")
      (fields
        (field (name "MANUFACTURER PART NUMBER") "CL10A226KQ8NRNE")
        (field (name "MANUFACTURER") "Samsung Electro-Mechanics America, Inc")
      )
      (libsource (lib "Miscellaneous Devices") (part "Cap"))
    )
    (comp (ref "C46")
      (value "10uF")
      (footprint "C0805")
      (description "CAP CER 10UF 10V 20% X5R 0805")
      (fields
        (field (name "MANUFACTURER PART NUMBER") "C2012X5R1A106M125AB")
        (field (name "MANUFACTURER") "TDK Corporation")
      )
      (libsource (lib "") (part "Cap_1"))
    )
    (comp (ref "C47")
      (value "10uF")
      (footprint "C0805")
      (description "CAP CER 10UF 10V 20% X5R 0805")
      (fields
        (field (name "MANUFACTURER PART NUMBER") "C2012X5R1A106M125AB")
        (field (name "MANUFACTURER") "TDK Corporation")
      )
      (libsource (lib "") (part "Cap_1"))
    )
    (comp (ref "C48")
      (value "10uF")
      (footprint "C0805")
      (description "CAP CER 10UF 10V 20% X5R 0805")
      (fields
        (field (name "MANUFACTURER PART NUMBER") "C2012X5R1A106M125AB")
        (field (name "MANUFACTURER") "TDK Corporation")
      )
      (libsource (lib "") (part "Cap_1"))
    )
    (comp (ref "C49")
      (value "10uF")
      (footprint "C0805")
      (description "CAP CER 10UF 10V 20% X5R 0805")
      (fields
        (field (name "MANUFACTURER PART NUMBER") "C2012X5R1A106M125AB")
        (field (name "MANUFACTURER") "TDK Corporation")
      )
      (libsource (lib "") (part "Cap_1"))
    )
    (comp (ref "C51")
      (value "100nF")
      (footprint "0603")
      (description "CAP CER 0.1UF 50V Y5V 0603")
      (fields
        (field (name "MANUFACTURER PART NUMBER") "CC0603ZRY5V9BB104")
        (field (name "MANUFACTURER") "Yageo")
      )
      (libsource (lib "Miscellaneous Devices") (part "Cap"))
    )
    (comp (ref "C52")
      (value "100pF")
      (footprint "0603")
      (description "CAP CER 100PF 100V 5% NP0 0603")
      (fields
        (field (name "MANUFACTURER PART NUMBER") "CL10C101JC81PNC")
        (field (name "MANUFACTURER") "Samsung Electro-Mechanics America, Inc")
      )
      (libsource (lib "Miscellaneous Devices") (part "Cap"))
    )
    (comp (ref "C53")
      (value "10uF")
      (footprint "C0805")
      (description "CAP CER 10UF 10V 20% X5R 0805")
      (fields
        (field (name "MANUFACTURER PART NUMBER") "C2012X5R1A106M125AB")
        (field (name "MANUFACTURER") "TDK Corporation")
      )
      (libsource (lib "") (part "Cap_1"))
    )
    (comp (ref "C54")
      (value "10uF")
      (footprint "C0805")
      (description "CAP CER 10UF 10V 20% X5R 0805")
      (fields
        (field (name "MANUFACTURER PART NUMBER") "C2012X5R1A106M125AB")
        (field (name "MANUFACTURER") "TDK Corporation")
      )
      (libsource (lib "") (part "Cap_1"))
    )
    (comp (ref "C55")
      (value "100nF")
      (footprint "0603")
      (description "CAP CER 0.1UF 50V Y5V 0603")
      (fields
        (field (name "MANUFACTURER PART NUMBER") "CC0603ZRY5V9BB104")
        (field (name "MANUFACTURER") "Yageo")
      )
      (libsource (lib "Miscellaneous Devices") (part "Cap"))
    )
    (comp (ref "C56")
      (value "100pF")
      (footprint "0603")
      (description "CAP CER 100PF 100V 5% NP0 0603")
      (fields
        (field (name "MANUFACTURER PART NUMBER") "CL10C101JC81PNC")
        (field (name "MANUFACTURER") "Samsung Electro-Mechanics America, Inc")
      )
      (libsource (lib "Miscellaneous Devices") (part "Cap"))
    )
    (comp (ref "C57")
      (value "100nF")
      (footprint "0603")
      (description "CAP CER 0.1UF 50V Y5V 0603")
      (fields
        (field (name "MANUFACTURER PART NUMBER") "CC0603ZRY5V9BB104")
        (field (name "MANUFACTURER") "Yageo")
      )
      (libsource (lib "Miscellaneous Devices") (part "Cap"))
    )
    (comp (ref "C58")
      (value "100pF")
      (footprint "0603")
      (description "CAP CER 100PF 100V 5% NP0 0603")
      (fields
        (field (name "MANUFACTURER PART NUMBER") "CL10C101JC81PNC")
        (field (name "MANUFACTURER") "Samsung Electro-Mechanics America, Inc")
      )
      (libsource (lib "Miscellaneous Devices") (part "Cap"))
    )
    (comp (ref "C59")
      (value "10uF")
      (footprint "C0805")
      (description "CAP CER 10UF 10V 20% X5R 0805")
      (fields
        (field (name "MANUFACTURER PART NUMBER") "C2012X5R1A106M125AB")
        (field (name "MANUFACTURER") "TDK Corporation")
      )
      (libsource (lib "") (part "Cap_1"))
    )
    (comp (ref "C60")
      (value "100nF")
      (footprint "0603")
      (description "CAP CER 0.1UF 50V Y5V 0603")
      (fields
        (field (name "MANUFACTURER PART NUMBER") "CC0603ZRY5V9BB104")
        (field (name "MANUFACTURER") "Yageo")
      )
      (libsource (lib "Miscellaneous Devices") (part "Cap"))
    )
    (comp (ref "C61")
      (value "10uF")
      (footprint "C0805")
      (description "CAP CER 10UF 10V 20% X5R 0805")
      (fields
        (field (name "MANUFACTURER PART NUMBER") "C2012X5R1A106M125AB")
        (field (name "MANUFACTURER") "TDK Corporation")
      )
      (libsource (lib "") (part "Cap_1"))
    )
    (comp (ref "C64")
      (value "100pF")
      (footprint "0603")
      (description "CAP CER 100PF 100V 5% NP0 0603")
      (fields
        (field (name "MANUFACTURER PART NUMBER") "CL10C101JC81PNC")
        (field (name "MANUFACTURER") "Samsung Electro-Mechanics America, Inc")
      )
      (libsource (lib "Miscellaneous Devices") (part "Cap"))
    )
    (comp (ref "C65")
      (value "10pF")
      (footprint "0603")
      (description "CAP CER 10PF 50V NP0 0603")
      (fields
        (field (name "MANUFACTURER PART NUMBER") "CL10C100CB81PNC")
        (field (name "MANUFACTURER") "Samsung Electro-Mechanics America, Inc")
      )
      (libsource (lib "Miscellaneous Devices") (part "Cap"))
    )
    (comp (ref "C66")
      (value "100nF")
      (footprint "0603")
      (description "CAP CER 0.1UF 50V Y5V 0603")
      (fields
        (field (name "MANUFACTURER PART NUMBER") "CC0603ZRY5V9BB104")
        (field (name "MANUFACTURER") "Yageo")
      )
      (libsource (lib "Miscellaneous Devices") (part "Cap"))
    )
    (comp (ref "C67")
      (value "10pF")
      (footprint "0603")
      (description "CAP CER 10PF 50V NP0 0603")
      (fields
        (field (name "MANUFACTURER PART NUMBER") "CL10C100CB81PNC")
        (field (name "MANUFACTURER") "Samsung Electro-Mechanics America, Inc")
      )
      (libsource (lib "Miscellaneous Devices") (part "Cap"))
    )
    (comp (ref "C68")
      (value "1uF")
      (footprint "0603")
      (description "CAP CER 1UF 10V 10% X5R 0603")
      (fields
        (field (name "MANUFACTURER PART NUMBER") "C0603C105K8PACTU")
        (field (name "MANUFACTURER") "Kemet")
      )
      (libsource (lib "Miscellaneous Devices") (part "Cap"))
    )
    (comp (ref "C69")
      (value "100nF")
      (footprint "0603")
      (description "CAP CER 0.1UF 50V 10% X7R 0603")
      (fields
        (field (name "MANUFACTURER PART NUMBER") "CL10B104KB8SFNC")
        (field (name "MANUFACTURER") "Samsung Electro-Mechanics America, Inc")
      )
      (libsource (lib "Miscellaneous Devices") (part "Cap"))
    )
    (comp (ref "C70")
      (value "220uF")
      (footprint "UUR1H330MCL1GS")
      (description "CAP ALUM 220UF 50V 20% SMD")
      (fields
        (field (name "MANUFACTURER PART NUMBER") "EEE-FT1H221AP")
        (field (name "MANUFACTURER") "Panasonic Electronic Components")
      )
      (libsource (lib "AX_Altium_v2.3") (part "CAP0810Alu"))
    )
    (comp (ref "C71")
      (value "100nF")
      (footprint "1206")
      (description "CAP CER 0.1UF 100V 10% X7R 1206")
      (fields
        (field (name "MANUFACTURER PART NUMBER") "CC1206KKX7R0BB104")
        (field (name "MANUFACTURER") "Yageo")
      )
      (libsource (lib "Miscellaneous Devices") (part "Cap"))
    )
    (comp (ref "C76")
      (value "470uF")
      (footprint "UUR1H330MCL1GS")
      (description "CAP ALUM 470UF 16V 20% SMD")
      (fields
        (field (name "MANUFACTURER PART NUMBER") "EEE-FP1C471AP")
        (field (name "MANUFACTURER") "Panasonic Electronic Components")
      )
      (libsource (lib "AX_Altium_v2.3") (part "CAP0810Alu"))
    )
    (comp (ref "C77")
      (value "470uF")
      (footprint "UUR1H330MCL1GS")
      (description "CAP ALUM 470UF 16V 20% SMD")
      (fields
        (field (name "MANUFACTURER PART NUMBER") "EEE-FP1C471AP")
        (field (name "MANUFACTURER") "Panasonic Electronic Components")
      )
      (libsource (lib "AX_Altium_v2.3") (part "CAP0810Alu"))
    )
    (comp (ref "C78")
      (value "100nF")
      (footprint "0603")
      (description "CAP CER 0.1UF 50V Y5V 0603")
      (fields
        (field (name "MANUFACTURER PART NUMBER") "CC0603ZRY5V9BB104")
        (field (name "MANUFACTURER") "Yageo")
      )
      (libsource (lib "Miscellaneous Devices") (part "Cap"))
    )
    (comp (ref "C79")
      (value "100nF")
      (footprint "0603")
      (description "CAP CER 0.1UF 50V Y5V 0603")
      (fields
        (field (name "MANUFACTURER PART NUMBER") "CC0603ZRY5V9BB104")
        (field (name "MANUFACTURER") "Yageo")
      )
      (libsource (lib "Miscellaneous Devices") (part "Cap"))
    )
    (comp (ref "C80")
      (value "1uF")
      (footprint "0603")
      (description "CAP CER 1UF 10V 10% X5R 0603")
      (fields
        (field (name "MANUFACTURER PART NUMBER") "C0603C105K8PACTU")
        (field (name "MANUFACTURER") "Kemet")
      )
      (libsource (lib "Miscellaneous Devices") (part "Cap"))
    )
    (comp (ref "C81")
      (value "100nF")
      (footprint "0603")
      (description "CAP CER 0.1UF 50V Y5V 0603")
      (fields
        (field (name "MANUFACTURER PART NUMBER") "CC0603ZRY5V9BB104")
        (field (name "MANUFACTURER") "Yageo")
      )
      (libsource (lib "Miscellaneous Devices") (part "Cap"))
    )
    (comp (ref "C82")
      (value "1uF")
      (footprint "0603")
      (description "CAP CER 1UF 10V 10% X5R 0603")
      (fields
        (field (name "MANUFACTURER PART NUMBER") "C0603C105K8PACTU")
        (field (name "MANUFACTURER") "Kemet")
      )
      (libsource (lib "Miscellaneous Devices") (part "Cap"))
    )
    (comp (ref "C83")
      (value "220uF")
      (footprint "UUR1H330MCL1GS")
      (description "CAP ALUM 220UF 50V 20% SMD")
      (fields
        (field (name "MANUFACTURER PART NUMBER") "EEE-FT1H221AP")
        (field (name "MANUFACTURER") "Panasonic Electronic Components")
      )
      (libsource (lib "AX_Altium_v2.3") (part "CAP0810Alu"))
    )
    (comp (ref "C84")
      (value "100nF")
      (footprint "1206")
      (description "CAP CER 0.1UF 100V 10% X7R 1206")
      (fields
        (field (name "MANUFACTURER PART NUMBER") "CC1206KKX7R0BB104")
        (field (name "MANUFACTURER") "Yageo")
      )
      (libsource (lib "Miscellaneous Devices") (part "Cap"))
    )
    (comp (ref "C85")
      (value "470uF")
      (footprint "UUR1H330MCL1GS")
      (description "CAP ALUM 470UF 16V 20% SMD")
      (fields
        (field (name "MANUFACTURER PART NUMBER") "EEE-FP1C471AP")
        (field (name "MANUFACTURER") "Panasonic Electronic Components")
      )
      (libsource (lib "AX_Altium_v2.3") (part "CAP0810Alu"))
    )
    (comp (ref "C86")
      (value "470uF")
      (footprint "UUR1H330MCL1GS")
      (description "CAP ALUM 470UF 16V 20% SMD")
      (fields
        (field (name "MANUFACTURER PART NUMBER") "EEE-FP1C471AP")
        (field (name "MANUFACTURER") "Panasonic Electronic Components")
      )
      (libsource (lib "AX_Altium_v2.3") (part "CAP0810Alu"))
    )
    (comp (ref "C87")
      (value "100nF")
      (footprint "0603")
      (description "CAP CER 0.1UF 50V Y5V 0603")
      (fields
        (field (name "MANUFACTURER PART NUMBER") "CC0603ZRY5V9BB104")
        (field (name "MANUFACTURER") "Yageo")
      )
      (libsource (lib "Miscellaneous Devices") (part "Cap"))
    )
    (comp (ref "C88")
      (value "100uF")
      (footprint "UUR1H330MCL1GS")
      (description "CAP ALUM 100UF 35V 20% SMD")
      (fields
        (field (name "MANUFACTURER PART NUMBER") "EEE-FP1V101AP")
        (field (name "MANUFACTURER") "Panasonic Electronic Components")
      )
      (libsource (lib "AX_Altium_v2.3") (part "CAP0810Alu"))
    )
    (comp (ref "C89")
      (value "1uF")
      (footprint "0603")
      (description "CAP CER 1UF 10V 10% X5R 0603")
      (fields
        (field (name "MANUFACTURER PART NUMBER") "C0603C105K8PACTU")
        (field (name "MANUFACTURER") "Kemet")
      )
      (libsource (lib "Miscellaneous Devices") (part "Cap"))
    )
    (comp (ref "C90")
      (value "1uF")
      (footprint "0603")
      (description "CAP CER 1UF 10V 10% X5R 0603")
      (fields
        (field (name "MANUFACTURER PART NUMBER") "C0603C105K8PACTU")
        (field (name "MANUFACTURER") "Kemet")
      )
      (libsource (lib "Miscellaneous Devices") (part "Cap"))
    )
    (comp (ref "C91")
      (value "10uF")
      (footprint "C0805")
      (description "CAP CER 10UF 10V 20% X5R 0805")
      (fields
        (field (name "MANUFACTURER PART NUMBER") "C2012X5R1A106M125AB")
        (field (name "MANUFACTURER") "TDK Corporation")
      )
      (libsource (lib "") (part "Cap_1"))
    )
    (comp (ref "C92")
      (value "100nF")
      (footprint "0603")
      (description "CAP CER 0.1UF 50V Y5V 0603")
      (fields
        (field (name "MANUFACTURER PART NUMBER") "CC0603ZRY5V9BB104")
        (field (name "MANUFACTURER") "Yageo")
      )
      (libsource (lib "Miscellaneous Devices") (part "Cap"))
    )
    (comp (ref "C93")
      (value "10uF")
      (footprint "C0805")
      (description "CAP CER 10UF 10V 20% X5R 0805")
      (fields
        (field (name "MANUFACTURER PART NUMBER") "C2012X5R1A106M125AB")
        (field (name "MANUFACTURER") "TDK Corporation")
      )
      (libsource (lib "") (part "Cap_1"))
    )
    (comp (ref "D1")
      (value "Led")
      (footprint "LED0603")
      (description "LED RED CLEAR 0603 SMD")
      (fields
        (field (name "MANUFACTURER PART NUMBER") "LTST-C190EKT")
        (field (name "MANUFACTURER") "Lite-On Inc")
      )
      (libsource (lib "Miscellaneous Devices") (part "LED0"))
    )
    (comp (ref "D2")
      (value "Led")
      (footprint "LED0603")
      (description "LED GREEN CLEAR THIN 0603 SMD")
      (fields
        (field (name "MANUFACTURER PART NUMBER") "LTST-C191KGKT")
        (field (name "MANUFACTURER") "Lite-On Inc")
      )
      (libsource (lib "Miscellaneous Devices") (part "LED0"))
    )
    (comp (ref "D3")
      (value "Diode")
      (footprint "D1206")
      (description "DIODE SCHOTTKY 100V 1A 1206")
      (fields
        (field (name "MANUFACTURER PART NUMBER") "SD1206S100S1R0")
        (field (name "MANUFACTURER") "AVX Corporation")
      )
      (libsource (lib "Miscellaneous Devices") (part "Diode 10TQ035"))
    )
    (comp (ref "D4")
      (value "Led")
      (footprint "LED0603")
      (description "LED BLUE CLEAR THIN 0603 SMD")
      (fields
        (field (name "MANUFACTURER PART NUMBER") "LTST-C191TBKT")
        (field (name "MANUFACTURER") "Lite-On Inc")
      )
      (libsource (lib "Miscellaneous Devices") (part "LED0"))
    )
    (comp (ref "D5")
      (value "Led")
      (footprint "LED0603")
      (description "LED BLUE CLEAR THIN 0603 SMD")
      (fields
        (field (name "MANUFACTURER PART NUMBER") "LTST-C191TBKT")
        (field (name "MANUFACTURER") "Lite-On Inc")
      )
      (libsource (lib "Miscellaneous Devices") (part "LED0"))
    )
    (comp (ref "D6")
      (value "Led")
      (footprint "LED0603")
      (description "LED GREEN CLEAR THIN 0603 SMD")
      (fields
        (field (name "MANUFACTURER PART NUMBER") "LTST-C191KGKT")
        (field (name "MANUFACTURER") "Lite-On Inc")
      )
      (libsource (lib "Miscellaneous Devices") (part "LED0"))
    )
    (comp (ref "D7")
      (value "Led")
      (footprint "LED0603")
      (description "LED BLUE CLEAR THIN 0603 SMD")
      (fields
        (field (name "MANUFACTURER PART NUMBER") "LTST-C191TBKT")
        (field (name "MANUFACTURER") "Lite-On Inc")
      )
      (libsource (lib "Miscellaneous Devices") (part "LED0"))
    )
    (comp (ref "D8")
      (value "Led")
      (footprint "LED0603")
      (description "LED YELLOW CLEAR THIN 0603 SMD")
      (fields
        (field (name "MANUFACTURER PART NUMBER") "LTST-C191KSKT")
        (field (name "MANUFACTURER") "Lite-On Inc")
      )
      (libsource (lib "Miscellaneous Devices") (part "LED0"))
    )
    (comp (ref "D9")
      (value "Led")
      (footprint "LED0603")
      (description "LED YELLOW CLEAR THIN 0603 SMD")
      (fields
        (field (name "MANUFACTURER PART NUMBER") "LTST-C191KSKT")
        (field (name "MANUFACTURER") "Lite-On Inc")
      )
      (libsource (lib "Miscellaneous Devices") (part "LED0"))
    )
    (comp (ref "D10")
      (value "Led")
      (footprint "LED0603")
      (description "LED GREEN CLEAR THIN 0603 SMD")
      (fields
        (field (name "MANUFACTURER PART NUMBER") "LTST-C191KGKT")
        (field (name "MANUFACTURER") "Lite-On Inc")
      )
      (libsource (lib "Miscellaneous Devices") (part "LED0"))
    )
    (comp (ref "D11")
      (value "Led")
      (footprint "LED0603")
      (description "LED RED CLEAR 0603 SMD")
      (fields
        (field (name "MANUFACTURER PART NUMBER") "LTST-C190EKT")
        (field (name "MANUFACTURER") "Lite-On Inc")
      )
      (libsource (lib "Miscellaneous Devices") (part "LED0"))
    )
    (comp (ref "D12")
      (value "Led")
      (footprint "LED0603")
      (description "LED RED CLEAR 0603 SMD")
      (fields
        (field (name "MANUFACTURER PART NUMBER") "LTST-C190EKT")
        (field (name "MANUFACTURER") "Lite-On Inc")
      )
      (libsource (lib "Miscellaneous Devices") (part "LED0"))
    )
    (comp (ref "D13")
      (value "Led")
      (footprint "LED0603")
      (description "LED BLUE CLEAR THIN 0603 SMD")
      (fields
        (field (name "MANUFACTURER PART NUMBER") "LTST-C191TBKT")
        (field (name "MANUFACTURER") "Lite-On Inc")
      )
      (libsource (lib "Miscellaneous Devices") (part "LED0"))
    )
    (comp (ref "D14")
      (value "Led")
      (footprint "LED0603")
      (description "LED  ORAN CLR THIN 0603 SMD")
      (fields
        (field (name "MANUFACTURER PART NUMBER") "LTST-C191KFKT")
        (field (name "MANUFACTURER") "Lite-On Inc")
      )
      (libsource (lib "Miscellaneous Devices") (part "LED0"))
    )
    (comp (ref "D15")
      (value "Led")
      (footprint "LED0603")
      (description "LED  ORAN CLR THIN 0603 SMD")
      (fields
        (field (name "MANUFACTURER PART NUMBER") "LTST-C191KFKT")
        (field (name "MANUFACTURER") "Lite-On Inc")
      )
      (libsource (lib "Miscellaneous Devices") (part "LED0"))
    )
    (comp (ref "D16")
      (value "Led")
      (footprint "LED0603")
      (description "LED  ORAN CLR THIN 0603 SMD")
      (fields
        (field (name "MANUFACTURER PART NUMBER") "LTST-C191KFKT")
        (field (name "MANUFACTURER") "Lite-On Inc")
      )
      (libsource (lib "Miscellaneous Devices") (part "LED0"))
    )
    (comp (ref "D17")
      (value "Led")
      (footprint "LED0603")
      (description "LED  ORAN CLR THIN 0603 SMD")
      (fields
        (field (name "MANUFACTURER PART NUMBER") "LTST-C191KFKT")
        (field (name "MANUFACTURER") "Lite-On Inc")
      )
      (libsource (lib "Miscellaneous Devices") (part "LED0"))
    )
    (comp (ref "D18")
      (value "Led")
      (footprint "LED0603")
      (description "LED BLUE CLEAR THIN 0603 SMD")
      (fields
        (field (name "MANUFACTURER PART NUMBER") "LTST-C191TBKT")
        (field (name "MANUFACTURER") "Lite-On Inc")
      )
      (libsource (lib "Miscellaneous Devices") (part "LED0"))
    )
    (comp (ref "D19")
      (value "Led")
      (footprint "LED0603")
      (description "LED BLUE CLEAR THIN 0603 SMD")
      (fields
        (field (name "MANUFACTURER PART NUMBER") "LTST-C191TBKT")
        (field (name "MANUFACTURER") "Lite-On Inc")
      )
      (libsource (lib "Miscellaneous Devices") (part "LED0"))
    )
    (comp (ref "D20")
      (value "Led")
      (footprint "LED0603")
      (description "LED GREEN CLEAR THIN 0603 SMD")
      (fields
        (field (name "MANUFACTURER PART NUMBER") "LTST-C191KGKT")
        (field (name "MANUFACTURER") "Lite-On Inc")
      )
      (libsource (lib "Miscellaneous Devices") (part "LED0"))
    )
    (comp (ref "D21")
      (value "Led")
      (footprint "LED0603")
      (description "LED BLUE CLEAR THIN 0603 SMD")
      (fields
        (field (name "MANUFACTURER PART NUMBER") "LTST-C191TBKT")
        (field (name "MANUFACTURER") "Lite-On Inc")
      )
      (libsource (lib "Miscellaneous Devices") (part "LED0"))
    )
    (comp (ref "D22")
      (value "Led")
      (footprint "LED0603")
      (description "LED GREEN CLEAR THIN 0603 SMD")
      (fields
        (field (name "MANUFACTURER PART NUMBER") "LTST-C191KGKT")
        (field (name "MANUFACTURER") "Lite-On Inc")
      )
      (libsource (lib "Miscellaneous Devices") (part "LED0"))
    )
    (comp (ref "D23")
      (value "Led")
      (footprint "LED0603")
      (description "LED RED CLEAR 0603 SMD")
      (fields
        (field (name "MANUFACTURER PART NUMBER") "LTST-C190EKT")
        (field (name "MANUFACTURER") "Lite-On Inc")
      )
      (libsource (lib "Miscellaneous Devices") (part "LED0"))
    )
    (comp (ref "D24")
      (value "Led")
      (footprint "LED0603")
      (description "LED RED CLEAR 0603 SMD")
      (fields
        (field (name "MANUFACTURER PART NUMBER") "LTST-C190EKT")
        (field (name "MANUFACTURER") "Lite-On Inc")
      )
      (libsource (lib "Miscellaneous Devices") (part "LED0"))
    )
    (comp (ref "D25")
      (value "Led")
      (footprint "LED0603")
      (description "LED RED CLEAR 0603 SMD")
      (fields
        (field (name "MANUFACTURER PART NUMBER") "LTST-C190EKT")
        (field (name "MANUFACTURER") "Lite-On Inc")
      )
      (libsource (lib "Miscellaneous Devices") (part "LED0"))
    )
    (comp (ref "D26")
      (value "Led")
      (footprint "LED0603")
      (description "LED  ORAN CLR THIN 0603 SMD")
      (fields
        (field (name "MANUFACTURER PART NUMBER") "LTST-C191KFKT")
        (field (name "MANUFACTURER") "Lite-On Inc")
      )
      (libsource (lib "Miscellaneous Devices") (part "LED0"))
    )
    (comp (ref "D27")
      (value "Led")
      (footprint "LED0603")
      (description "LED  ORAN CLR THIN 0603 SMD")
      (fields
        (field (name "MANUFACTURER PART NUMBER") "LTST-C191KFKT")
        (field (name "MANUFACTURER") "Lite-On Inc")
      )
      (libsource (lib "Miscellaneous Devices") (part "LED0"))
    )
    (comp (ref "D28")
      (value "Led")
      (footprint "LED0603")
      (description "LED BLUE CLEAR THIN 0603 SMD")
      (fields
        (field (name "MANUFACTURER PART NUMBER") "LTST-C191TBKT")
        (field (name "MANUFACTURER") "Lite-On Inc")
      )
      (libsource (lib "Miscellaneous Devices") (part "LED0"))
    )
    (comp (ref "D29")
      (value "Diode")
      (footprint "D1206")
      (description "DIODE SCHOTTKY 100V 1A 1206")
      (fields
        (field (name "MANUFACTURER PART NUMBER") "SD1206S100S1R0")
        (field (name "MANUFACTURER") "AVX Corporation")
      )
      (libsource (lib "Miscellaneous Devices") (part "Diode 10TQ035"))
    )
    (comp (ref "D30")
      (value "Diode")
      (footprint "D1206")
      (description "DIODE SCHOTTKY 100V 1A 1206")
      (fields
        (field (name "MANUFACTURER PART NUMBER") "SD1206S100S1R0")
        (field (name "MANUFACTURER") "AVX Corporation")
      )
      (libsource (lib "Miscellaneous Devices") (part "Diode 10TQ035"))
    )
    (comp (ref "D31")
      (value "Diode")
      (footprint "D1206")
      (description "DIODE SCHOTTKY 100V 1A 1206")
      (fields
        (field (name "MANUFACTURER PART NUMBER") "SD1206S100S1R0")
        (field (name "MANUFACTURER") "AVX Corporation")
      )
      (libsource (lib "Miscellaneous Devices") (part "Diode 10TQ035"))
    )
    (comp (ref "D32")
      (value "Diode")
      (footprint "D1206")
      (description "DIODE SCHOTTKY 100V 1A 1206")
      (fields
        (field (name "MANUFACTURER PART NUMBER") "SD1206S100S1R0")
        (field (name "MANUFACTURER") "AVX Corporation")
      )
      (libsource (lib "Miscellaneous Devices") (part "Diode 10TQ035"))
    )
    (comp (ref "D33")
      (value "Diode")
      (footprint "D1206")
      (description "DIODE SCHOTTKY 100V 1A 1206")
      (fields
        (field (name "MANUFACTURER PART NUMBER") "SD1206S100S1R0")
        (field (name "MANUFACTURER") "AVX Corporation")
      )
      (libsource (lib "Miscellaneous Devices") (part "Diode 10TQ035"))
    )
    (comp (ref "D34")
      (value "Bridge")
      (footprint "CDBHM2100L-HF")
      (description "BRIDGE RECTIFIER 100V 2A MBS2")
      (fields
        (field (name "MANUFACTURER PART NUMBER") "CDBHM2100L-HF")
        (field (name "MANUFACTURER") "Comchip Technology")
      )
      (libsource (lib "Miscellaneous Devices") (part "Bridge1"))
    )
    (comp (ref "D35")
      (value "Suppressor")
      (footprint "DO214AA")
      (description "TVS DIODE 51VWM 82.4VC SMB")
      (fields
        (field (name "MANUFACTURER PART NUMBER") "SMBJ51A")
        (field (name "MANUFACTURER") "Fairchild Semiconductor")
      )
      (libsource (lib "Miscellaneous Devices") (part "Diode 10TQ035"))
    )
    (comp (ref "D36")
      (value "Diode")
      (footprint "D1206")
      (description "DIODE SCHOTTKY 100V 1A 1206")
      (fields
        (field (name "MANUFACTURER PART NUMBER") "SD1206S100S1R0")
        (field (name "MANUFACTURER") "AVX Corporation")
      )
      (libsource (lib "Miscellaneous Devices") (part "Diode 10TQ035"))
    )
    (comp (ref "D37")
      (value "Diode")
      (footprint "D0603")
      (description "DIODE SCHOTTKY 40V 0.03A 0603")
      (fields
        (field (name "MANUFACTURER PART NUMBER") "CDBU00340")
        (field (name "MANUFACTURER") "Comchip Technology")
      )
      (libsource (lib "Miscellaneous Devices") (part "Diode 10TQ035"))
    )
    (comp (ref "D38")
      (value "Diode")
      (footprint "D0603")
      (description "DIODE SCHOTTKY 40V 0.03A 0603")
      (fields
        (field (name "MANUFACTURER PART NUMBER") "CDBU00340")
        (field (name "MANUFACTURER") "Comchip Technology")
      )
      (libsource (lib "Miscellaneous Devices") (part "Diode 10TQ035"))
    )
    (comp (ref "D39")
      (value "Diode")
      (footprint "D0603")
      (description "DIODE SCHOTTKY 40V 0.03A 0603")
      (fields
        (field (name "MANUFACTURER PART NUMBER") "CDBU00340")
        (field (name "MANUFACTURER") "Comchip Technology")
      )
      (libsource (lib "Miscellaneous Devices") (part "Diode 10TQ035"))
    )
    (comp (ref "F1")
      (value "Fuse, slow 2A")
      (footprint "C1206")
      (description "FUSE 2A 63V 1206 SLOW C1S")
      (fields (field (name "MANUFACTURER PART NUMBER") "C1S 2") (field (name "MANUFACTURER") "Bel Fuse Inc"))
      (libsource (lib "Miscellaneous Devices") (part "Fuse 2"))
    )
    (comp (ref "F2")
      (value "Fuse, slow 2A")
      (footprint "C1206")
      (description "FUSE 2A 63V 1206 SLOW C1S")
      (fields (field (name "MANUFACTURER PART NUMBER") "C1S 2") (field (name "MANUFACTURER") "Bel Fuse Inc"))
      (libsource (lib "Miscellaneous Devices") (part "Fuse 2"))
    )
    (comp (ref "J1")
      (value "Phonejack3")
      (footprint "audio")
      (description "CONN JACK STEREO 3POS 3.5MM SMD")
      (fields
        (field (name "MANUFACTURER PART NUMBER") "SJ1-3513-SMT-TR")
        (field (name "MANUFACTURER") "CUI Inc")
      )
      (libsource (lib "Miscellaneous Connectors") (part "Phonejack3"))
    )
    (comp (ref "K1")
      (value "az8222")
      (footprint "az8222")
      (description "5V 2A Relay")
      (fields
        (field (name "MANUFACTURER PART NUMBER") "AZ8222–2C–5DME")
        (field (name "MANUFACTURER") "American Zettler")
      )
      (libsource (lib "thermostat_main") (part "az8222"))
    )
    (comp (ref "K2")
      (value "az8222")
      (footprint "az8222")
      (description "5V 2A Relay")
      (fields
        (field (name "MANUFACTURER PART NUMBER") "AZ8222–2C–5DME")
        (field (name "MANUFACTURER") "American Zettler")
      )
      (libsource (lib "thermostat_main") (part "az8222"))
    )
    (comp (ref "K3")
      (value "az8222")
      (footprint "az8222")
      (description "5V 2A Relay")
      (fields
        (field (name "MANUFACTURER PART NUMBER") "AZ8222–2C–5DME")
        (field (name "MANUFACTURER") "American Zettler")
      )
      (libsource (lib "thermostat_main") (part "az8222"))
    )
    (comp (ref "K4")
      (value "az8222")
      (footprint "az8222")
      (description "5V 2A Relay")
      (fields
        (field (name "MANUFACTURER PART NUMBER") "AZ8222–2C–5DME")
        (field (name "MANUFACTURER") "American Zettler")
      )
      (libsource (lib "thermostat_main") (part "az8222"))
    )
    (comp (ref "K5")
      (value "az8222")
      (footprint "az8222")
      (description "5V 2A Relay")
      (fields
        (field (name "MANUFACTURER PART NUMBER") "AZ8222–2C–5DME")
        (field (name "MANUFACTURER") "American Zettler")
      )
      (libsource (lib "thermostat_main") (part "az8222"))
    )
    (comp (ref "K6")
      (value "az8222")
      (footprint "az8222")
      (description "5V 2A Relay")
      (fields
        (field (name "MANUFACTURER PART NUMBER") "AZ8222–2C–5DME")
        (field (name "MANUFACTURER") "American Zettler")
      )
      (libsource (lib "thermostat_main") (part "az8222"))
    )
    (comp (ref "K7")
      (value "az8222")
      (footprint "az8222")
      (description "5V 2A Relay")
      (fields
        (field (name "MANUFACTURER PART NUMBER") "AZ8222–2C–5DME")
        (field (name "MANUFACTURER") "American Zettler")
      )
      (libsource (lib "thermostat_main") (part "az8222"))
    )
    (comp (ref "K8")
      (value "az8222")
      (footprint "az8222")
      (description "5V 2A Relay")
      (fields
        (field (name "MANUFACTURER PART NUMBER") "AZ8222–2C–5DME")
        (field (name "MANUFACTURER") "American Zettler")
      )
      (libsource (lib "thermostat_main") (part "az8222"))
    )
    (comp (ref "K9")
      (value "az8222")
      (footprint "az8222")
      (description "5V 2A Relay")
      (fields
        (field (name "MANUFACTURER PART NUMBER") "AZ8222–2C–5DME")
        (field (name "MANUFACTURER") "American Zettler")
      )
      (libsource (lib "thermostat_main") (part "az8222"))
    )
    (comp (ref "K10")
      (value "az8222")
      (footprint "az8222")
      (description "5V 2A Relay")
      (fields
        (field (name "MANUFACTURER PART NUMBER") "AZ8222–2C–5DME")
        (field (name "MANUFACTURER") "American Zettler")
      )
      (libsource (lib "thermostat_main") (part "az8222"))
    )
    (comp (ref "K11")
      (value "az8222")
      (footprint "az8222")
      (description "5V 2A Relay")
      (fields
        (field (name "MANUFACTURER PART NUMBER") "AZ8222–2C–5DME")
        (field (name "MANUFACTURER") "American Zettler")
      )
      (libsource (lib "thermostat_main") (part "az8222"))
    )
    (comp (ref "K12")
      (value "az8222")
      (footprint "az8222")
      (description "5V 2A Relay")
      (fields
        (field (name "MANUFACTURER PART NUMBER") "AZ8222–2C–5DME")
        (field (name "MANUFACTURER") "American Zettler")
      )
      (libsource (lib "thermostat_main") (part "az8222"))
    )
    (comp (ref "K13")
      (value "az8222")
      (footprint "az8222")
      (description "5V 2A Relay")
      (fields
        (field (name "MANUFACTURER PART NUMBER") "AZ8222–2C–5DME")
        (field (name "MANUFACTURER") "American Zettler")
      )
      (libsource (lib "thermostat_main") (part "az8222"))
    )
    (comp (ref "K14")
      (value "az8222")
      (footprint "az8222")
      (description "5V 2A Relay")
      (fields
        (field (name "MANUFACTURER PART NUMBER") "AZ8222–2C–5DME")
        (field (name "MANUFACTURER") "American Zettler")
      )
      (libsource (lib "thermostat_main") (part "az8222"))
    )
    (comp (ref "K15")
      (value "az8222")
      (footprint "az8222")
      (description "5V 2A Relay")
      (fields
        (field (name "MANUFACTURER PART NUMBER") "AZ8222–2C–5DME")
        (field (name "MANUFACTURER") "American Zettler")
      )
      (libsource (lib "thermostat_main") (part "az8222"))
    )
    (comp (ref "K16")
      (value "az8222")
      (footprint "az8222")
      (description "5V 2A Relay")
      (fields
        (field (name "MANUFACTURER PART NUMBER") "AZ8222–2C–5DME")
        (field (name "MANUFACTURER") "American Zettler")
      )
      (libsource (lib "thermostat_main") (part "az8222"))
    )
    (comp (ref "K17")
      (value "az8222")
      (footprint "az8222")
      (description "5V 2A Relay")
      (fields
        (field (name "MANUFACTURER PART NUMBER") "AZ8222–2C–5DME")
        (field (name "MANUFACTURER") "American Zettler")
      )
      (libsource (lib "thermostat_main") (part "az8222"))
    )
    (comp (ref "K18")
      (value "az8222")
      (footprint "az8222")
      (description "5V 2A Relay")
      (fields
        (field (name "MANUFACTURER PART NUMBER") "AZ8222–2C–5DME")
        (field (name "MANUFACTURER") "American Zettler")
      )
      (libsource (lib "thermostat_main") (part "az8222"))
    )
    (comp (ref "K19")
      (value "az8222")
      (footprint "az8222")
      (description "5V 2A Relay")
      (fields
        (field (name "MANUFACTURER PART NUMBER") "AZ8222–2C–5DME")
        (field (name "MANUFACTURER") "American Zettler")
      )
      (libsource (lib "thermostat_main") (part "az8222"))
    )
    (comp (ref "K20")
      (value "az8222")
      (footprint "az8222")
      (description "5V 2A Relay")
      (fields
        (field (name "MANUFACTURER PART NUMBER") "AZ8222–2C–5DME")
        (field (name "MANUFACTURER") "American Zettler")
      )
      (libsource (lib "thermostat_main") (part "az8222"))
    )
    (comp (ref "K21")
      (value "az8222")
      (footprint "az8222")
      (description "5V 2A Relay")
      (fields
        (field (name "MANUFACTURER PART NUMBER") "AZ8222–2C–5DME")
        (field (name "MANUFACTURER") "American Zettler")
      )
      (libsource (lib "thermostat_main") (part "az8222"))
    )
    (comp (ref "K22")
      (value "az8222")
      (footprint "az8222")
      (description "5V 2A Relay")
      (fields
        (field (name "MANUFACTURER PART NUMBER") "AZ8222–2C–5DME")
        (field (name "MANUFACTURER") "American Zettler")
      )
      (libsource (lib "thermostat_main") (part "az8222"))
    )
    (comp (ref "L1")
      (value "Inductor")
      (footprint "KM_4")
      (description "INDUCTOR PWR TOROID 100UH T/H")
      (fields
        (field (name "ALTIUM_VALUE") "100uH")
        (field (name "MANUFACTURER PART NUMBER") "PE-92108KNL")
        (field (name "MANUFACTURER") "Pulse Electronics Corporation")
      )
      (libsource (lib "Miscellaneous Devices") (part "Inductor"))
    )
    (comp (ref "L2")
      (value "Inductor")
      (footprint "KM_4")
      (description "INDUCTOR PWR TOROID 100UH T/H")
      (fields
        (field (name "ALTIUM_VALUE") "100uH")
        (field (name "MANUFACTURER PART NUMBER") "PE-92108KNL")
        (field (name "MANUFACTURER") "Pulse Electronics Corporation")
      )
      (libsource (lib "Miscellaneous Devices") (part "Inductor"))
    )
    (comp (ref "L3")
      (value "Inductor")
      (footprint "IND22")
      (description "INDUCTOR 20UH 2.6A 8095 RAD")
      (fields
        (field (name "ALTIUM_VALUE") "20uH")
        (field (name "MANUFACTURER PART NUMBER") "744772200")
        (field (name "MANUFACTURER") "Wurth Electronics Inc")
      )
      (libsource (lib "Miscellaneous Devices") (part "Inductor"))
    )
    (comp (ref "LS1")
      (value "Speaker")
      (footprint "CEP2242")
      (description "BUZZER PIEZO 12V 13.7MM RADIAL")
      (fields
        (field (name "MANUFACTURER PART NUMBER") "CEP-2242")
        (field (name "MANUFACTURER") "CUI Inc")
        (field (name "PUBLISHER") "Altium Limited")
      )
      (libsource (lib "Miscellaneous Devices") (part "Speaker"))
    )
    (comp (ref "LS2")
      (value "Speaker")
      (footprint "AS02808MR")
      (description "SPEAKER 8OHM 1W 80DB 28MM")
      (fields
        (field (name "MANUFACTURER PART NUMBER") "AS02808MR-R")
        (field (name "MANUFACTURER") "PUI Audio, Inc.")
        (field (name "PUBLISHER") "Altium Limited")
      )
      (libsource (lib "Miscellaneous Devices") (part "Speaker"))
    )
    (comp (ref "LS3")
      (value "Speaker")
      (footprint "AS02808MR")
      (description "SPEAKER 8OHM 1W 80DB 28MM")
      (fields
        (field (name "MANUFACTURER PART NUMBER") "AS02808MR-R")
        (field (name "MANUFACTURER") "PUI Audio, Inc.")
        (field (name "PUBLISHER") "Altium Limited")
      )
      (libsource (lib "Miscellaneous Devices") (part "Speaker"))
    )
    (comp (ref "P1")
      (value "Header 7X2")
      (footprint "JTAG14")
      (description "CONN FEMALE 14POS DL .1\" TIN SMD")
      (fields
        (field (name "MANUFACTURER PART NUMBER") "NPTC072KFMS-RC")
        (field (name "MANUFACTURER") "Sullins Connector Solutions")
      )
      (libsource (lib "Miscellaneous Connectors") (part "Header 7X2"))
    )
    (comp (ref "P2")
      (value "Header 2")
      (footprint "HDR1X2")
      (description "CONN HDR BRKWAY .100 2POS VERT")
      (fields
        (field (name "MANUFACTURER PART NUMBER") "5-146274-2")
        (field (name "MANUFACTURER") "TE Connectivity")
      )
      (libsource (lib "") (part "Header 2_1"))
    )
    (comp (ref "P3")
      (value "Header 10")
      (footprint "10pin_socket")
      (description "TERM BLOCK HDR 10POS R/A 5.08MM")
      (fields
        (field (name "MANUFACTURER PART NUMBER") "20020109-H101A01LF")
        (field (name "MANUFACTURER") "FCI")
      )
      (libsource (lib "Miscellaneous Connectors") (part "Header 10"))
    )
    (comp (ref "P4")
      (value "Header 10")
      (footprint "10pin_socket")
      (description "TERM BLOCK HDR 10POS R/A 5.08MM")
      (fields
        (field (name "MANUFACTURER PART NUMBER") "20020109-H101A01LF")
        (field (name "MANUFACTURER") "FCI")
      )
      (libsource (lib "") (part "Header 10_1"))
    )
    (comp (ref "P5")
      (value "Header 13X2")
      (footprint "HDR2X13")
      (description "CONN HEADER 26POS .100 STR 30AU")
      (fields (field (name "MANUFACTURER PART NUMBER") "68602-126HLF") (field (name "MANUFACTURER") "FCI"))
      (libsource (lib "Miscellaneous Connectors") (part "Header 13X2"))
    )
    (comp (ref "P6")
      (value "Header 3")
      (footprint "3pin_socket")
      (description "Header, 3-Pin")
      (fields
        (field (name "MANUFACTURER PART NUMBER") "1759020")
        (field (name "MANUFACTURER") "Phoenix Contact")
      )
      (libsource (lib "Miscellaneous Connectors") (part "Header 3"))
    )
    (comp (ref "P7")
      (value "Header 2")
      (footprint "2pin_socket")
      (description "TERM BLOCK HDR 2POS R/A 5.08MM")
      (fields
        (field (name "MANUFACTURER PART NUMBER") "1759017")
        (field (name "MANUFACTURER") "Phoenix Contact")
      )
      (libsource (lib "Miscellaneous Connectors") (part "Header 2"))
    )
    (comp (ref "P8")
      (value "Header 2")
      (footprint "2pin_socket")
      (description "TERM BLOCK HDR 2POS R/A 5.08MM")
      (fields
        (field (name "MANUFACTURER PART NUMBER") "1759017")
        (field (name "MANUFACTURER") "Phoenix Contact")
      )
      (libsource (lib "Miscellaneous Connectors") (part "Header 2"))
    )
    (comp (ref "P9")
      (value "Header 2")
      (footprint "2pin_socket")
      (description "TERM BLOCK HDR 2POS R/A 5.08MM")
      (fields
        (field (name "MANUFACTURER PART NUMBER") "1759017")
        (field (name "MANUFACTURER") "Phoenix Contact")
      )
      (libsource (lib "Miscellaneous Connectors") (part "Header 2"))
    )
    (comp (ref "P10")
      (value "Header 3")
      (footprint "RJ11")
      (description "CONN MOD JACK R/A 6P6C")
      (fields
        (field (name "MANUFACTURER PART NUMBER") "5555165-1")
        (field (name "MANUFACTURER") "TE Connectivity")
        (field (name "PUBLISHER") "Altium Limited")
      )
      (libsource (lib "") (part "Header 3_1"))
    )
    (comp (ref "P11")
      (value "Header 2")
      (footprint "2pin_socket")
      (description "TERM BLOCK HDR 2POS R/A 5.08MM")
      (fields
        (field (name "MANUFACTURER PART NUMBER") "1759017")
        (field (name "MANUFACTURER") "Phoenix Contact")
      )
      (libsource (lib "Miscellaneous Connectors") (part "Header 2"))
    )
    (comp (ref "P12")
      (value "Header 2")
      (footprint "2pin_socket")
      (description "TERM BLOCK HDR 2POS R/A 5.08MM")
      (fields
        (field (name "MANUFACTURER PART NUMBER") "1759017")
        (field (name "MANUFACTURER") "Phoenix Contact")
      )
      (libsource (lib "Miscellaneous Connectors") (part "Header 2"))
    )
    (comp (ref "P13")
      (value "Header 3")
      (footprint "RJ11")
      (description "CONN MOD JACK R/A 6P6C")
      (fields
        (field (name "MANUFACTURER PART NUMBER") "5555165-1")
        (field (name "MANUFACTURER") "TE Connectivity")
        (field (name "PUBLISHER") "Altium Limited")
      )
      (libsource (lib "") (part "Header 3_1"))
    )
    (comp (ref "P14")
      (value "Header 2")
      (footprint "2pin_socket")
      (description "TERM BLOCK HDR 2POS R/A 5.08MM")
      (fields
        (field (name "MANUFACTURER PART NUMBER") "1759017")
        (field (name "MANUFACTURER") "Phoenix Contact")
      )
      (libsource (lib "Miscellaneous Connectors") (part "Header 2"))
    )
    (comp (ref "P15")
      (value "Header 4")
      (footprint "RJ11")
      (description "CONN MOD JACK R/A 6P6C")
      (fields
        (field (name "MANUFACTURER PART NUMBER") "5555165-1")
        (field (name "MANUFACTURER") "TE Connectivity")
      )
      (libsource (lib "") (part "Header 4_1"))
    )
    (comp (ref "P16")
      (value "Header 4")
      (footprint "GRPB041VWCN_RC")
      (description "CONN HEADER .050\" 4POS PCB R/A")
      (fields
        (field (name "MANUFACTURER PART NUMBER") "GRPB041VWCN-RC")
        (field (name "MANUFACTURER") "Sullins Connector Solutions")
      )
      (libsource (lib "Miscellaneous Connectors") (part "Header 4"))
    )
    (comp (ref "P17")
      (value "Header 2")
      (footprint "2pin_socket")
      (description "TERM BLOCK HDR 2POS R/A 5.08MM")
      (fields
        (field (name "MANUFACTURER PART NUMBER") "1759017")
        (field (name "MANUFACTURER") "Phoenix Contact")
      )
      (libsource (lib "") (part "Header 2_2"))
    )
    (comp (ref "P18")
      (value "Header 2")
      (footprint "2pin_socket")
      (description "TERM BLOCK HDR 2POS R/A 5.08MM")
      (fields
        (field (name "MANUFACTURER PART NUMBER") "1759017")
        (field (name "MANUFACTURER") "Phoenix Contact")
      )
      (libsource (lib "") (part "Header 2_2"))
    )
    (comp (ref "P19")
      (value "Header 20X2")
      (footprint "CON40")
      (description "CONN FMALE 40POS DL .1\" GOLD SMD")
      (fields
        (field (name "MANUFACTURER PART NUMBER") "NPPC202KFMS-RC")
        (field (name "MANUFACTURER") "Sullins Connector Solutions")
      )
      (libsource (lib "Miscellaneous Connectors") (part "Header 20X2"))
    )
    (comp (ref "P20")
      (value "Header 2")
      (footprint "2pin_socket")
      (description "TERM BLOCK HDR 2POS R/A 5.08MM")
      (fields
        (field (name "MANUFACTURER PART NUMBER") "1759017")
        (field (name "MANUFACTURER") "Phoenix Contact")
      )
      (libsource (lib "") (part "Header 2_2"))
    )
    (comp (ref "P21")
      (value "Header 2")
      (footprint "2pin_socket")
      (description "TERM BLOCK HDR 2POS R/A 5.08MM")
      (fields
        (field (name "MANUFACTURER PART NUMBER") "1759017")
        (field (name "MANUFACTURER") "Phoenix Contact")
      )
      (libsource (lib "Miscellaneous Connectors") (part "Header 2"))
    )
    (comp (ref "P22")
      (value "Header 4X2")
      (footprint "CON8")
      (description "CONN HEADER 8POS .100\" VERT TIN")
      (fields
        (field (name "MANUFACTURER PART NUMBER") "0015912080")
        (field (name "MANUFACTURER") "Molex Inc")
      )
      (libsource (lib "Miscellaneous Connectors") (part "Header 4X2"))
    )
    (comp (ref "P23")
      (value "Header 2")
      (footprint "2pin_socket")
      (description "TERM BLOCK HDR 2POS R/A 5.08MM")
      (fields
        (field (name "MANUFACTURER PART NUMBER") "1759017")
        (field (name "MANUFACTURER") "Phoenix Contact")
      )
      (libsource (lib "Miscellaneous Connectors") (part "Header 2"))
    )
    (comp (ref "P24")
      (value "Header 2")
      (footprint "2pin_socket")
      (description "TERM BLOCK HDR 2POS R/A 5.08MM")
      (fields
        (field (name "MANUFACTURER PART NUMBER") "1759017")
        (field (name "MANUFACTURER") "Phoenix Contact")
      )
      (libsource (lib "Miscellaneous Connectors") (part "Header 2"))
    )
    (comp (ref "P25")
      (value "Connector")
      (footprint "BAT_CON")
      (description "CONN HEADER VERT 2POS .100 TIN")
      (fields
        (field (name "MANUFACTURER PART NUMBER") "640455-2")
        (field (name "MANUFACTURER") "TE Connectivity")
      )
      (libsource (lib "") (part "Header 2_1"))
    )
    (comp (ref "P26")
      (value "Connector")
      (footprint "BAT_CON")
      (description "CONN HEADER VERT 2POS .100 TIN")
      (fields
        (field (name "MANUFACTURER PART NUMBER") "640455-2")
        (field (name "MANUFACTURER") "TE Connectivity")
      )
      (libsource (lib "") (part "Header 2_1"))
    )
    (comp (ref "Q1")
      (value "IRLML6302GTRPBF")
      (footprint "SOT-23_N")
      (description "HEXFET Power MOSFET")
      (fields
        (field (name "MANUFACTURER") "International Rectifier")
        (field (name "PUBLISHER") "Altium Limited")
      )
      (libsource (lib "IR Discrete MOSFET - Power") (part "IRLML6302"))
    )
    (comp (ref "Q5")
      (value "IRLML6302GTRPBF")
      (footprint "SOT-23_N")
      (description "HEXFET Power MOSFET")
      (fields
        (field (name "MANUFACTURER") "International Rectifier")
        (field (name "PUBLISHER") "Altium Limited")
      )
      (libsource (lib "IR Discrete MOSFET - Power") (part "IRLML6302"))
    )
    (comp (ref "Q6")
      (value "KST3904MTF")
      (footprint "SOT-23_N")
      (description "TRANSISTOR NPN 40V 200MA SOT-23")
      (fields (field (name "MANUFACTURER") "Fairchild Semiconductor"))
      (libsource (lib "Miscellaneous Devices") (part "2N3904"))
    )
    (comp (ref "Q7")
      (value "KST3904MTF")
      (footprint "SOT-23_N")
      (description "TRANSISTOR NPN 40V 200MA SOT-23")
      (fields (field (name "MANUFACTURER") "Fairchild Semiconductor"))
      (libsource (lib "Miscellaneous Devices") (part "2N3904"))
    )
    (comp (ref "Q8")
      (value "KST3904MTF")
      (footprint "SOT-23_N")
      (description "TRANSISTOR NPN 40V 200MA SOT-23")
      (fields (field (name "MANUFACTURER") "Fairchild Semiconductor"))
      (libsource (lib "Miscellaneous Devices") (part "2N3904"))
    )
    (comp (ref "Q9")
      (value "BSR18A")
      (footprint "SOT-23_N")
      (description "IC AMP PNP 40V 200MA SOT-23")
      (fields (field (name "MANUFACTURER") "Fairchild Semiconductor"))
      (libsource (lib "Miscellaneous Devices") (part "2N3906"))
    )
    (comp (ref "Q10")
      (value "KST3904MTF")
      (footprint "SOT-23_N")
      (description "TRANSISTOR NPN 40V 200MA SOT-23")
      (fields (field (name "MANUFACTURER") "Fairchild Semiconductor"))
      (libsource (lib "Miscellaneous Devices") (part "2N3904"))
    )
    (comp (ref "R1")
      (value "10k")
      (footprint "0603")
      (description "RES 10K OHM 1/10W 5% 0603 SMD")
      (fields
        (field (name "MANUFACTURER PART NUMBER") "RC0603JR-0710KL")
        (field (name "MANUFACTURER") "Yageo")
      )
      (libsource (lib "Miscellaneous Devices") (part "Res3"))
    )
    (comp (ref "R2")
      (value "10k")
      (footprint "0603")
      (description "RES 10K OHM 1/10W 5% 0603 SMD")
      (fields
        (field (name "MANUFACTURER PART NUMBER") "RC0603JR-0710KL")
        (field (name "MANUFACTURER") "Yageo")
      )
      (libsource (lib "Miscellaneous Devices") (part "Res3"))
    )
    (comp (ref "R3")
      (value "10k")
      (footprint "0603")
      (description "RES 10K OHM 1/10W 5% 0603 SMD")
      (fields
        (field (name "MANUFACTURER PART NUMBER") "RC0603JR-0710KL")
        (field (name "MANUFACTURER") "Yageo")
      )
      (libsource (lib "Miscellaneous Devices") (part "Res3"))
    )
    (comp (ref "R4")
      (value "10k")
      (footprint "0603")
      (description "RES 10K OHM 1/10W 5% 0603 SMD")
      (fields
        (field (name "MANUFACTURER PART NUMBER") "RC0603JR-0710KL")
        (field (name "MANUFACTURER") "Yageo")
      )
      (libsource (lib "Miscellaneous Devices") (part "Res3"))
    )
    (comp (ref "R5")
      (value "1M")
      (footprint "0603")
      (description "RES 1M OHM 1/10W 1% 0603 SMD")
      (fields
        (field (name "MANUFACTURER PART NUMBER") "ERJ-3EKF1004V")
        (field (name "MANUFACTURER") "Panasonic Electronic Components")
      )
      (libsource (lib "Miscellaneous Devices") (part "Res3"))
    )
    (comp (ref "R6")
      (value "1k")
      (footprint "0603")
      (description "RES 1K OHM 1/10W 1% 0603")
      (fields
        (field (name "MANUFACTURER PART NUMBER") "RC1608F102CS")
        (field (name "MANUFACTURER") "Samsung Electro-Mechanics America, Inc")
      )
      (libsource (lib "Miscellaneous Devices") (part "Res3"))
    )
    (comp (ref "R7")
      (value "330R")
      (footprint "0603")
      (description "RES 330 OHM 1/10W 5% 0603")
      (fields
        (field (name "MANUFACTURER PART NUMBER") "RC1608J331CS")
        (field (name "MANUFACTURER") "Samsung Electro-Mechanics America, Inc")
      )
      (libsource (lib "Miscellaneous Devices") (part "Res3"))
    )
    (comp (ref "R8")
      (value "330R")
      (footprint "0603")
      (description "RES 330 OHM 1/10W 5% 0603")
      (fields
        (field (name "MANUFACTURER PART NUMBER") "RC1608J331CS")
        (field (name "MANUFACTURER") "Samsung Electro-Mechanics America, Inc")
      )
      (libsource (lib "Miscellaneous Devices") (part "Res3"))
    )
    (comp (ref "R9")
      (value "10k")
      (footprint "0603")
      (description "RES 10K OHM 1/10W 5% 0603 SMD")
      (fields
        (field (name "MANUFACTURER PART NUMBER") "RC0603JR-0710KL")
        (field (name "MANUFACTURER") "Yageo")
      )
      (libsource (lib "Miscellaneous Devices") (part "Res3"))
    )
    (comp (ref "R10")
      (value "10k")
      (footprint "0603")
      (description "RES 10K OHM 1/10W 5% 0603 SMD")
      (fields
        (field (name "MANUFACTURER PART NUMBER") "RC0603JR-0710KL")
        (field (name "MANUFACTURER") "Yageo")
      )
      (libsource (lib "Miscellaneous Devices") (part "Res3"))
    )
    (comp (ref "R11")
      (value "10k")
      (footprint "0603")
      (description "RES 10K OHM 1/10W 5% 0603 SMD")
      (fields
        (field (name "MANUFACTURER PART NUMBER") "RC0603JR-0710KL")
        (field (name "MANUFACTURER") "Yageo")
      )
      (libsource (lib "Miscellaneous Devices") (part "Res3"))
    )
    (comp (ref "R12")
      (value "10k")
      (footprint "0603")
      (description "RES 10K OHM 1/10W 5% 0603 SMD")
      (fields
        (field (name "MANUFACTURER PART NUMBER") "RC0603JR-0710KL")
        (field (name "MANUFACTURER") "Yageo")
      )
      (libsource (lib "Miscellaneous Devices") (part "Res3"))
    )
    (comp (ref "R13")
      (value "10k")
      (footprint "0603")
      (description "RES 10K OHM 1/10W 5% 0603 SMD")
      (fields
        (field (name "MANUFACTURER PART NUMBER") "RC0603JR-0710KL")
        (field (name "MANUFACTURER") "Yageo")
      )
      (libsource (lib "Miscellaneous Devices") (part "Res3"))
    )
    (comp (ref "R14")
      (value "10k")
      (footprint "0603")
      (description "RES 10K OHM 1/10W 5% 0603 SMD")
      (fields
        (field (name "MANUFACTURER PART NUMBER") "RC0603JR-0710KL")
        (field (name "MANUFACTURER") "Yageo")
      )
      (libsource (lib "Miscellaneous Devices") (part "Res3"))
    )
    (comp (ref "R15")
      (value "10k")
      (footprint "0603")
      (description "RES 10K OHM 1/10W 5% 0603 SMD")
      (fields
        (field (name "MANUFACTURER PART NUMBER") "RC0603JR-0710KL")
        (field (name "MANUFACTURER") "Yageo")
      )
      (libsource (lib "Miscellaneous Devices") (part "Res3"))
    )
    (comp (ref "R16")
      (value "10k")
      (footprint "0603")
      (description "RES 10K OHM 1/10W 5% 0603 SMD")
      (fields
        (field (name "MANUFACTURER PART NUMBER") "RC0603JR-0710KL")
        (field (name "MANUFACTURER") "Yageo")
      )
      (libsource (lib "Miscellaneous Devices") (part "Res3"))
    )
    (comp (ref "R17")
      (value "10k")
      (footprint "0603")
      (description "RES 10K OHM 1/10W 5% 0603 SMD")
      (fields
        (field (name "MANUFACTURER PART NUMBER") "RC0603JR-0710KL")
        (field (name "MANUFACTURER") "Yageo")
      )
      (libsource (lib "Miscellaneous Devices") (part "Res3"))
    )
    (comp (ref "R18")
      (value "10k")
      (footprint "0603")
      (description "RES 10K OHM 1/10W 5% 0603 SMD")
      (fields
        (field (name "MANUFACTURER PART NUMBER") "RC0603JR-0710KL")
        (field (name "MANUFACTURER") "Yageo")
      )
      (libsource (lib "Miscellaneous Devices") (part "Res3"))
    )
    (comp (ref "R19")
      (value "10R")
      (footprint "6-0805_L")
      (description "RES 10 OHM 1/8W 5% 0805")
      (fields
        (field (name "MANUFACTURER PART NUMBER") "RC2012J100CS")
        (field (name "MANUFACTURER") "Samsung Electro-Mechanics America, Inc")
      )
      (libsource (lib "Miscellaneous Devices") (part "Res3"))
    )
    (comp (ref "R20")
      (value "0R")
      (footprint "1206")
      (description "RES 0.0 OHM 1/4W JUMP 1206")
      (fields
        (field (name "MANUFACTURER PART NUMBER") "RC3216J000CS")
        (field (name "MANUFACTURER") "Samsung Electro-Mechanics America, Inc")
      )
      (libsource (lib "Miscellaneous Devices") (part "Res3"))
    )
    (comp (ref "R22")
      (value "10R")
      (footprint "6-0805_L")
      (description "RES 10 OHM 1/8W 5% 0805")
      (fields
        (field (name "MANUFACTURER PART NUMBER") "RC2012J100CS")
        (field (name "MANUFACTURER") "Samsung Electro-Mechanics America, Inc")
      )
      (libsource (lib "Miscellaneous Devices") (part "Res3"))
    )
    (comp (ref "R23")
      (value "10R")
      (footprint "6-0805_L")
      (description "RES 10 OHM 1/8W 5% 0805")
      (fields
        (field (name "MANUFACTURER PART NUMBER") "RC2012J100CS")
        (field (name "MANUFACTURER") "Samsung Electro-Mechanics America, Inc")
      )
      (libsource (lib "Miscellaneous Devices") (part "Res3"))
    )
    (comp (ref "R24")
      (value "10R")
      (footprint "6-0805_L")
      (description "RES 10 OHM 1/8W 5% 0805")
      (fields
        (field (name "MANUFACTURER PART NUMBER") "RC2012J100CS")
        (field (name "MANUFACTURER") "Samsung Electro-Mechanics America, Inc")
      )
      (libsource (lib "Miscellaneous Devices") (part "Res3"))
    )
    (comp (ref "R25")
      (value "10R")
      (footprint "6-0805_L")
      (description "RES 10 OHM 1/8W 5% 0805")
      (fields
        (field (name "MANUFACTURER PART NUMBER") "RC2012J100CS")
        (field (name "MANUFACTURER") "Samsung Electro-Mechanics America, Inc")
      )
      (libsource (lib "Miscellaneous Devices") (part "Res3"))
    )
    (comp (ref "R26")
      (value "10R")
      (footprint "6-0805_L")
      (description "RES 10 OHM 1/8W 5% 0805")
      (fields
        (field (name "MANUFACTURER PART NUMBER") "RC2012J100CS")
        (field (name "MANUFACTURER") "Samsung Electro-Mechanics America, Inc")
      )
      (libsource (lib "Miscellaneous Devices") (part "Res3"))
    )
    (comp (ref "R27")
      (value "10R")
      (footprint "6-0805_L")
      (description "RES 10 OHM 1/8W 5% 0805")
      (fields
        (field (name "MANUFACTURER PART NUMBER") "RC2012J100CS")
        (field (name "MANUFACTURER") "Samsung Electro-Mechanics America, Inc")
      )
      (libsource (lib "Miscellaneous Devices") (part "Res3"))
    )
    (comp (ref "R28")
      (value "10R")
      (footprint "6-0805_L")
      (description "RES 10 OHM 1/8W 5% 0805")
      (fields
        (field (name "MANUFACTURER PART NUMBER") "RC2012J100CS")
        (field (name "MANUFACTURER") "Samsung Electro-Mechanics America, Inc")
      )
      (libsource (lib "Miscellaneous Devices") (part "Res3"))
    )
    (comp (ref "R29")
      (value "10k")
      (footprint "0603")
      (description "RES 10K OHM 1/10W 5% 0603 SMD")
      (fields
        (field (name "MANUFACTURER PART NUMBER") "RC0603JR-0710KL")
        (field (name "MANUFACTURER") "Yageo")
      )
      (libsource (lib "Miscellaneous Devices") (part "Res3"))
    )
    (comp (ref "R30")
      (value "10k")
      (footprint "0603")
      (description "RES 10K OHM 1/10W 5% 0603 SMD")
      (fields
        (field (name "MANUFACTURER PART NUMBER") "RC0603JR-0710KL")
        (field (name "MANUFACTURER") "Yageo")
      )
      (libsource (lib "Miscellaneous Devices") (part "Res3"))
    )
    (comp (ref "R31")
      (value "10R")
      (footprint "6-0805_L")
      (description "RES 10 OHM 1/8W 5% 0805")
      (fields
        (field (name "MANUFACTURER PART NUMBER") "RC2012J100CS")
        (field (name "MANUFACTURER") "Samsung Electro-Mechanics America, Inc")
      )
      (libsource (lib "Miscellaneous Devices") (part "Res3"))
    )
    (comp (ref "R32")
      (value "10R")
      (footprint "6-0805_L")
      (description "RES 10 OHM 1/8W 5% 0805")
      (fields
        (field (name "MANUFACTURER PART NUMBER") "RC2012J100CS")
        (field (name "MANUFACTURER") "Samsung Electro-Mechanics America, Inc")
      )
      (libsource (lib "Miscellaneous Devices") (part "Res3"))
    )
    (comp (ref "R33")
      (value "1.5k")
      (footprint "1206")
      (description "RES 1.5K OHM 1/4W 5% 1206")
      (fields
        (field (name "MANUFACTURER PART NUMBER") "RC3216J152CS")
        (field (name "MANUFACTURER") "Samsung Electro-Mechanics America, Inc")
      )
      (libsource (lib "Miscellaneous Devices") (part "Res3"))
    )
    (comp (ref "R34")
      (value "1.5k")
      (footprint "1206")
      (description "RES 1.5K OHM 1/4W 5% 1206")
      (fields
        (field (name "MANUFACTURER PART NUMBER") "RC3216J152CS")
        (field (name "MANUFACTURER") "Samsung Electro-Mechanics America, Inc")
      )
      (libsource (lib "Miscellaneous Devices") (part "Res3"))
    )
    (comp (ref "R35")
      (value "10R")
      (footprint "6-0805_L")
      (description "RES 10 OHM 1/8W 5% 0805")
      (fields
        (field (name "MANUFACTURER PART NUMBER") "RC2012J100CS")
        (field (name "MANUFACTURER") "Samsung Electro-Mechanics America, Inc")
      )
      (libsource (lib "Miscellaneous Devices") (part "Res3"))
    )
    (comp (ref "R36")
      (value "10R")
      (footprint "6-0805_L")
      (description "RES 10 OHM 1/8W 5% 0805")
      (fields
        (field (name "MANUFACTURER PART NUMBER") "RC2012J100CS")
        (field (name "MANUFACTURER") "Samsung Electro-Mechanics America, Inc")
      )
      (libsource (lib "Miscellaneous Devices") (part "Res3"))
    )
    (comp (ref "R37")
      (value "10R")
      (footprint "6-0805_L")
      (description "RES 10 OHM 1/8W 5% 0805")
      (fields
        (field (name "MANUFACTURER PART NUMBER") "RC2012J100CS")
        (field (name "MANUFACTURER") "Samsung Electro-Mechanics America, Inc")
      )
      (libsource (lib "Miscellaneous Devices") (part "Res3"))
    )
    (comp (ref "R38")
      (value "10R")
      (footprint "6-0805_L")
      (description "RES 10 OHM 1/8W 5% 0805")
      (fields
        (field (name "MANUFACTURER PART NUMBER") "RC2012J100CS")
        (field (name "MANUFACTURER") "Samsung Electro-Mechanics America, Inc")
      )
      (libsource (lib "Miscellaneous Devices") (part "Res3"))
    )
    (comp (ref "R39")
      (value "10R")
      (footprint "6-0805_L")
      (description "RES 10 OHM 1/8W 5% 0805")
      (fields
        (field (name "MANUFACTURER PART NUMBER") "RC2012J100CS")
        (field (name "MANUFACTURER") "Samsung Electro-Mechanics America, Inc")
      )
      (libsource (lib "Miscellaneous Devices") (part "Res3"))
    )
    (comp (ref "R40")
      (value "10R")
      (footprint "6-0805_L")
      (description "RES 10 OHM 1/8W 5% 0805")
      (fields
        (field (name "MANUFACTURER PART NUMBER") "RC2012J100CS")
        (field (name "MANUFACTURER") "Samsung Electro-Mechanics America, Inc")
      )
      (libsource (lib "Miscellaneous Devices") (part "Res3"))
    )
    (comp (ref "R41")
      (value "10R")
      (footprint "6-0805_L")
      (description "RES 10 OHM 1/8W 5% 0805")
      (fields
        (field (name "MANUFACTURER PART NUMBER") "RC2012J100CS")
        (field (name "MANUFACTURER") "Samsung Electro-Mechanics America, Inc")
      )
      (libsource (lib "Miscellaneous Devices") (part "Res3"))
    )
    (comp (ref "R42")
      (value "47R")
      (footprint "RESMELF3614N")
      (description "RES 47 OHM .4W 2% 0204 MELF")
      (fields
        (field (name "MANUFACTURER PART NUMBER") "CMA02040X4709GB300")
        (field (name "MANUFACTURER") "Vishay Beyschlag")
      )
      (libsource (lib "Miscellaneous Devices") (part "Res3"))
    )
    (comp (ref "R43")
      (value "47R")
      (footprint "RESMELF3614N")
      (description "RES 47 OHM .4W 2% 0204 MELF")
      (fields
        (field (name "MANUFACTURER PART NUMBER") "CMA02040X4709GB300")
        (field (name "MANUFACTURER") "Vishay Beyschlag")
      )
      (libsource (lib "Miscellaneous Devices") (part "Res3"))
    )
    (comp (ref "R44")
      (value "10k")
      (footprint "0603")
      (description "RES 10K OHM 1/10W 5% 0603 SMD")
      (fields
        (field (name "MANUFACTURER PART NUMBER") "RC0603JR-0710KL")
        (field (name "MANUFACTURER") "Yageo")
      )
      (libsource (lib "Miscellaneous Devices") (part "Res3"))
    )
    (comp (ref "R45")
      (value "10k")
      (footprint "0603")
      (description "RES 10K OHM 1/10W 5% 0603 SMD")
      (fields
        (field (name "MANUFACTURER PART NUMBER") "RC0603JR-0710KL")
        (field (name "MANUFACTURER") "Yageo")
      )
      (libsource (lib "Miscellaneous Devices") (part "Res3"))
    )
    (comp (ref "R46")
      (value "47R")
      (footprint "RESMELF3614N")
      (description "RES 47 OHM .4W 2% 0204 MELF")
      (fields
        (field (name "MANUFACTURER PART NUMBER") "CMA02040X4709GB300")
        (field (name "MANUFACTURER") "Vishay Beyschlag")
      )
      (libsource (lib "Miscellaneous Devices") (part "Res3"))
    )
    (comp (ref "R47")
      (value "47R")
      (footprint "RESMELF3614N")
      (description "RES 47 OHM .4W 2% 0204 MELF")
      (fields
        (field (name "MANUFACTURER PART NUMBER") "CMA02040X4709GB300")
        (field (name "MANUFACTURER") "Vishay Beyschlag")
      )
      (libsource (lib "Miscellaneous Devices") (part "Res3"))
    )
    (comp (ref "R48")
      (value "1.5k")
      (footprint "1206")
      (description "RES 1.5K OHM 1/4W 5% 1206")
      (fields
        (field (name "MANUFACTURER PART NUMBER") "RC3216J152CS")
        (field (name "MANUFACTURER") "Samsung Electro-Mechanics America, Inc")
      )
      (libsource (lib "Miscellaneous Devices") (part "Res3"))
    )
    (comp (ref "R49")
      (value "1.5k")
      (footprint "1206")
      (description "RES 1.5K OHM 1/4W 5% 1206")
      (fields
        (field (name "MANUFACTURER PART NUMBER") "RC3216J152CS")
        (field (name "MANUFACTURER") "Samsung Electro-Mechanics America, Inc")
      )
      (libsource (lib "Miscellaneous Devices") (part "Res3"))
    )
    (comp (ref "R50")
      (value "47R")
      (footprint "RESMELF3614N")
      (description "RES 47 OHM .4W 2% 0204 MELF")
      (fields
        (field (name "MANUFACTURER PART NUMBER") "CMA02040X4709GB300")
        (field (name "MANUFACTURER") "Vishay Beyschlag")
      )
      (libsource (lib "Miscellaneous Devices") (part "Res3"))
    )
    (comp (ref "R51")
      (value "47R")
      (footprint "RESMELF3614N")
      (description "RES 47 OHM .4W 2% 0204 MELF")
      (fields
        (field (name "MANUFACTURER PART NUMBER") "CMA02040X4709GB300")
        (field (name "MANUFACTURER") "Vishay Beyschlag")
      )
      (libsource (lib "Miscellaneous Devices") (part "Res3"))
    )
    (comp (ref "R52")
      (value "330R")
      (footprint "0603")
      (description "RES 330 OHM 1/10W 5% 0603")
      (fields
        (field (name "MANUFACTURER PART NUMBER") "RC1608J331CS")
        (field (name "MANUFACTURER") "Samsung Electro-Mechanics America, Inc")
      )
      (libsource (lib "Miscellaneous Devices") (part "Res3"))
    )
    (comp (ref "R53")
      (value "330R")
      (footprint "0603")
      (description "RES 330 OHM 1/10W 5% 0603")
      (fields
        (field (name "MANUFACTURER PART NUMBER") "RC1608J331CS")
        (field (name "MANUFACTURER") "Samsung Electro-Mechanics America, Inc")
      )
      (libsource (lib "Miscellaneous Devices") (part "Res3"))
    )
    (comp (ref "R54")
      (value "330R")
      (footprint "0603")
      (description "RES 330 OHM 1/10W 5% 0603")
      (fields
        (field (name "MANUFACTURER PART NUMBER") "RC1608J331CS")
        (field (name "MANUFACTURER") "Samsung Electro-Mechanics America, Inc")
      )
      (libsource (lib "Miscellaneous Devices") (part "Res3"))
    )
    (comp (ref "R55")
      (value "330R")
      (footprint "0603")
      (description "RES 330 OHM 1/10W 5% 0603")
      (fields
        (field (name "MANUFACTURER PART NUMBER") "RC1608J331CS")
        (field (name "MANUFACTURER") "Samsung Electro-Mechanics America, Inc")
      )
      (libsource (lib "Miscellaneous Devices") (part "Res3"))
    )
    (comp (ref "R56")
      (value "47R")
      (footprint "RESMELF3614N")
      (description "RES 47 OHM .4W 2% 0204 MELF")
      (fields
        (field (name "MANUFACTURER PART NUMBER") "CMA02040X4709GB300")
        (field (name "MANUFACTURER") "Vishay Beyschlag")
      )
      (libsource (lib "Miscellaneous Devices") (part "Res3"))
    )
    (comp (ref "R57")
      (value "47R")
      (footprint "RESMELF3614N")
      (description "RES 47 OHM .4W 2% 0204 MELF")
      (fields
        (field (name "MANUFACTURER PART NUMBER") "CMA02040X4709GB300")
        (field (name "MANUFACTURER") "Vishay Beyschlag")
      )
      (libsource (lib "Miscellaneous Devices") (part "Res3"))
    )
    (comp (ref "R58")
      (value "10k")
      (footprint "0603")
      (description "RES 10K OHM 1/10W 5% 0603 SMD")
      (fields
        (field (name "MANUFACTURER PART NUMBER") "RC0603JR-0710KL")
        (field (name "MANUFACTURER") "Yageo")
      )
      (libsource (lib "Miscellaneous Devices") (part "Res3"))
    )
    (comp (ref "R59")
      (value "10k")
      (footprint "0603")
      (description "RES 10K OHM 1/10W 5% 0603 SMD")
      (fields
        (field (name "MANUFACTURER PART NUMBER") "RC0603JR-0710KL")
        (field (name "MANUFACTURER") "Yageo")
      )
      (libsource (lib "Miscellaneous Devices") (part "Res3"))
    )
    (comp (ref "R60")
      (value "100R")
      (footprint "6-0805_L")
      (description "RES 100 OHM 1/8W 5% 0805")
      (fields
        (field (name "MANUFACTURER PART NUMBER") "RC2012J101CS")
        (field (name "MANUFACTURER") "Samsung Electro-Mechanics America, Inc")
      )
      (libsource (lib "Miscellaneous Devices") (part "Res3"))
    )
    (comp (ref "R61")
      (value "47R")
      (footprint "RESMELF3614N")
      (description "RES 47 OHM .4W 2% 0204 MELF")
      (fields
        (field (name "MANUFACTURER PART NUMBER") "CMA02040X4709GB300")
        (field (name "MANUFACTURER") "Vishay Beyschlag")
      )
      (libsource (lib "Miscellaneous Devices") (part "Res3"))
    )
    (comp (ref "R62")
      (value "47R")
      (footprint "RESMELF3614N")
      (description "RES 47 OHM .4W 2% 0204 MELF")
      (fields
        (field (name "MANUFACTURER PART NUMBER") "CMA02040X4709GB300")
        (field (name "MANUFACTURER") "Vishay Beyschlag")
      )
      (libsource (lib "Miscellaneous Devices") (part "Res3"))
    )
    (comp (ref "R63")
      (value "1.5k")
      (footprint "1206")
      (description "RES 1.5K OHM 1/4W 5% 1206")
      (fields
        (field (name "MANUFACTURER PART NUMBER") "RC3216J152CS")
        (field (name "MANUFACTURER") "Samsung Electro-Mechanics America, Inc")
      )
      (libsource (lib "Miscellaneous Devices") (part "Res3"))
    )
    (comp (ref "R64")
      (value "1.5k")
      (footprint "1206")
      (description "RES 1.5K OHM 1/4W 5% 1206")
      (fields
        (field (name "MANUFACTURER PART NUMBER") "RC3216J152CS")
        (field (name "MANUFACTURER") "Samsung Electro-Mechanics America, Inc")
      )
      (libsource (lib "Miscellaneous Devices") (part "Res3"))
    )
    (comp (ref "R65")
      (value "47R")
      (footprint "RESMELF3614N")
      (description "RES 47 OHM .4W 2% 0204 MELF")
      (fields
        (field (name "MANUFACTURER PART NUMBER") "CMA02040X4709GB300")
        (field (name "MANUFACTURER") "Vishay Beyschlag")
      )
      (libsource (lib "Miscellaneous Devices") (part "Res3"))
    )
    (comp (ref "R66")
      (value "47R")
      (footprint "RESMELF3614N")
      (description "RES 47 OHM .4W 2% 0204 MELF")
      (fields
        (field (name "MANUFACTURER PART NUMBER") "CMA02040X4709GB300")
        (field (name "MANUFACTURER") "Vishay Beyschlag")
      )
      (libsource (lib "Miscellaneous Devices") (part "Res3"))
    )
    (comp (ref "R67")
      (value "330R")
      (footprint "0603")
      (description "RES 330 OHM 1/10W 5% 0603")
      (fields
        (field (name "MANUFACTURER PART NUMBER") "RC1608J331CS")
        (field (name "MANUFACTURER") "Samsung Electro-Mechanics America, Inc")
      )
      (libsource (lib "Miscellaneous Devices") (part "Res3"))
    )
    (comp (ref "R68")
      (value "330R")
      (footprint "0603")
      (description "RES 330 OHM 1/10W 5% 0603")
      (fields
        (field (name "MANUFACTURER PART NUMBER") "RC1608J331CS")
        (field (name "MANUFACTURER") "Samsung Electro-Mechanics America, Inc")
      )
      (libsource (lib "Miscellaneous Devices") (part "Res3"))
    )
    (comp (ref "R69")
      (value "330R")
      (footprint "0603")
      (description "RES 330 OHM 1/10W 5% 0603")
      (fields
        (field (name "MANUFACTURER PART NUMBER") "RC1608J331CS")
        (field (name "MANUFACTURER") "Samsung Electro-Mechanics America, Inc")
      )
      (libsource (lib "Miscellaneous Devices") (part "Res3"))
    )
    (comp (ref "R70")
      (value "330R")
      (footprint "0603")
      (description "RES 330 OHM 1/10W 5% 0603")
      (fields
        (field (name "MANUFACTURER PART NUMBER") "RC1608J331CS")
        (field (name "MANUFACTURER") "Samsung Electro-Mechanics America, Inc")
      )
      (libsource (lib "Miscellaneous Devices") (part "Res3"))
    )
    (comp (ref "R71")
      (value "330R")
      (footprint "0603")
      (description "RES 330 OHM 1/10W 5% 0603")
      (fields
        (field (name "MANUFACTURER PART NUMBER") "RC1608J331CS")
        (field (name "MANUFACTURER") "Samsung Electro-Mechanics America, Inc")
      )
      (libsource (lib "Miscellaneous Devices") (part "Res3"))
    )
    (comp (ref "R72")
      (value "330R")
      (footprint "0603")
      (description "RES 330 OHM 1/10W 5% 0603")
      (fields
        (field (name "MANUFACTURER PART NUMBER") "RC1608J331CS")
        (field (name "MANUFACTURER") "Samsung Electro-Mechanics America, Inc")
      )
      (libsource (lib "Miscellaneous Devices") (part "Res3"))
    )
    (comp (ref "R73")
      (value "2.2k")
      (footprint "0603")
      (description "RES 2.2K OHM 1/10W 5% 0603")
      (fields
        (field (name "MANUFACTURER PART NUMBER") "RC1608J222CS")
        (field (name "MANUFACTURER") "Samsung Electro-Mechanics America, Inc")
      )
      (libsource (lib "Miscellaneous Devices") (part "Res3"))
    )
    (comp (ref "R74")
      (value "47R")
      (footprint "RESMELF3614N")
      (description "RES 47 OHM .4W 2% 0204 MELF")
      (fields
        (field (name "MANUFACTURER PART NUMBER") "CMA02040X4709GB300")
        (field (name "MANUFACTURER") "Vishay Beyschlag")
      )
      (libsource (lib "Miscellaneous Devices") (part "Res3"))
    )
    (comp (ref "R75")
      (value "47R")
      (footprint "RESMELF3614N")
      (description "RES 47 OHM .4W 2% 0204 MELF")
      (fields
        (field (name "MANUFACTURER PART NUMBER") "CMA02040X4709GB300")
        (field (name "MANUFACTURER") "Vishay Beyschlag")
      )
      (libsource (lib "Miscellaneous Devices") (part "Res3"))
    )
    (comp (ref "R76")
      (value "10k")
      (footprint "0603")
      (description "RES 10K OHM 1/10W 5% 0603 SMD")
      (fields
        (field (name "MANUFACTURER PART NUMBER") "RC0603JR-0710KL")
        (field (name "MANUFACTURER") "Yageo")
      )
      (libsource (lib "Miscellaneous Devices") (part "Res3"))
    )
    (comp (ref "R77")
      (value "10k")
      (footprint "0603")
      (description "RES 10K OHM 1/10W 5% 0603 SMD")
      (fields
        (field (name "MANUFACTURER PART NUMBER") "RC0603JR-0710KL")
        (field (name "MANUFACTURER") "Yageo")
      )
      (libsource (lib "Miscellaneous Devices") (part "Res3"))
    )
    (comp (ref "R78")
      (value "1.5k")
      (footprint "1206")
      (description "RES 1.5K OHM 1/4W 5% 1206")
      (fields
        (field (name "MANUFACTURER PART NUMBER") "RC3216J152CS")
        (field (name "MANUFACTURER") "Samsung Electro-Mechanics America, Inc")
      )
      (libsource (lib "Miscellaneous Devices") (part "Res3"))
    )
    (comp (ref "R79")
      (value "1.5k")
      (footprint "1206")
      (description "RES 1.5K OHM 1/4W 5% 1206")
      (fields
        (field (name "MANUFACTURER PART NUMBER") "RC3216J152CS")
        (field (name "MANUFACTURER") "Samsung Electro-Mechanics America, Inc")
      )
      (libsource (lib "Miscellaneous Devices") (part "Res3"))
    )
    (comp (ref "R80")
      (value "10k")
      (footprint "0603")
      (description "RES 10K OHM 1/10W 5% 0603 SMD")
      (fields
        (field (name "MANUFACTURER PART NUMBER") "RC0603JR-0710KL")
        (field (name "MANUFACTURER") "Yageo")
      )
      (libsource (lib "Miscellaneous Devices") (part "Res3"))
    )
    (comp (ref "R81")
      (value "10k")
      (footprint "0603")
      (description "RES 10K OHM 1/10W 5% 0603 SMD")
      (fields
        (field (name "MANUFACTURER PART NUMBER") "RC0603JR-0710KL")
        (field (name "MANUFACTURER") "Yageo")
      )
      (libsource (lib "Miscellaneous Devices") (part "Res3"))
    )
    (comp (ref "R82")
      (value "1.5k")
      (footprint "1206")
      (description "RES 1.5K OHM 1/4W 5% 1206")
      (fields
        (field (name "MANUFACTURER PART NUMBER") "RC3216J152CS")
        (field (name "MANUFACTURER") "Samsung Electro-Mechanics America, Inc")
      )
      (libsource (lib "Miscellaneous Devices") (part "Res3"))
    )
    (comp (ref "R83")
      (value "1.5k")
      (footprint "1206")
      (description "RES 1.5K OHM 1/4W 5% 1206")
      (fields
        (field (name "MANUFACTURER PART NUMBER") "RC3216J152CS")
        (field (name "MANUFACTURER") "Samsung Electro-Mechanics America, Inc")
      )
      (libsource (lib "Miscellaneous Devices") (part "Res3"))
    )
    (comp (ref "R84")
      (value "330R")
      (footprint "0603")
      (description "RES 330 OHM 1/10W 5% 0603")
      (fields
        (field (name "MANUFACTURER PART NUMBER") "RC1608J331CS")
        (field (name "MANUFACTURER") "Samsung Electro-Mechanics America, Inc")
      )
      (libsource (lib "Miscellaneous Devices") (part "Res3"))
    )
    (comp (ref "R85")
      (value "330R")
      (footprint "0603")
      (description "RES 330 OHM 1/10W 5% 0603")
      (fields
        (field (name "MANUFACTURER PART NUMBER") "RC1608J331CS")
        (field (name "MANUFACTURER") "Samsung Electro-Mechanics America, Inc")
      )
      (libsource (lib "Miscellaneous Devices") (part "Res3"))
    )
    (comp (ref "R86")
      (value "330R")
      (footprint "0603")
      (description "RES 330 OHM 1/10W 5% 0603")
      (fields
        (field (name "MANUFACTURER PART NUMBER") "RC1608J331CS")
        (field (name "MANUFACTURER") "Samsung Electro-Mechanics America, Inc")
      )
      (libsource (lib "Miscellaneous Devices") (part "Res3"))
    )
    (comp (ref "R87")
      (value "330R")
      (footprint "0603")
      (description "RES 330 OHM 1/10W 5% 0603")
      (fields
        (field (name "MANUFACTURER PART NUMBER") "RC1608J331CS")
        (field (name "MANUFACTURER") "Samsung Electro-Mechanics America, Inc")
      )
      (libsource (lib "Miscellaneous Devices") (part "Res3"))
    )
    (comp (ref "R88")
      (value "330R")
      (footprint "0603")
      (description "RES 330 OHM 1/10W 5% 0603")
      (fields
        (field (name "MANUFACTURER PART NUMBER") "RC1608J331CS")
        (field (name "MANUFACTURER") "Samsung Electro-Mechanics America, Inc")
      )
      (libsource (lib "Miscellaneous Devices") (part "Res3"))
    )
    (comp (ref "R89")
      (value "330R")
      (footprint "0603")
      (description "RES 330 OHM 1/10W 5% 0603")
      (fields
        (field (name "MANUFACTURER PART NUMBER") "RC1608J331CS")
        (field (name "MANUFACTURER") "Samsung Electro-Mechanics America, Inc")
      )
      (libsource (lib "Miscellaneous Devices") (part "Res3"))
    )
    (comp (ref "R90")
      (value "330R")
      (footprint "0603")
      (description "RES 330 OHM 1/10W 5% 0603")
      (fields
        (field (name "MANUFACTURER PART NUMBER") "RC1608J331CS")
        (field (name "MANUFACTURER") "Samsung Electro-Mechanics America, Inc")
      )
      (libsource (lib "Miscellaneous Devices") (part "Res3"))
    )
    (comp (ref "R91")
      (value "330R")
      (footprint "0603")
      (description "RES 330 OHM 1/10W 5% 0603")
      (fields
        (field (name "MANUFACTURER PART NUMBER") "RC1608J331CS")
        (field (name "MANUFACTURER") "Samsung Electro-Mechanics America, Inc")
      )
      (libsource (lib "Miscellaneous Devices") (part "Res3"))
    )
    (comp (ref "R93")
      (value "240k")
      (footprint "0603")
      (description "RES 240K OHM 1/10W 1% 0603")
      (fields
        (field (name "MANUFACTURER PART NUMBER") "RC1608F244CS")
        (field (name "MANUFACTURER") "Samsung Electro-Mechanics America, Inc")
      )
      (libsource (lib "Miscellaneous Devices") (part "Res3"))
    )
    (comp (ref "R94")
      (value "1k")
      (footprint "0603")
      (description "RES 1K OHM 1/10W 1% 0603")
      (fields
        (field (name "MANUFACTURER PART NUMBER") "RC1608F102CS")
        (field (name "MANUFACTURER") "Samsung Electro-Mechanics America, Inc")
      )
      (libsource (lib "Miscellaneous Devices") (part "Res3"))
    )
    (comp (ref "R95")
      (value "100k")
      (footprint "0603")
      (description "RES 100K OHM 1/10W 1% 0603")
      (fields
        (field (name "MANUFACTURER PART NUMBER") "RC1608F104CS")
        (field (name "MANUFACTURER") "Samsung Electro-Mechanics America, Inc")
      )
      (libsource (lib "Miscellaneous Devices") (part "Res3"))
    )
    (comp (ref "R96")
      (value "330R")
      (footprint "0603")
      (description "RES 330 OHM 1/10W 5% 0603")
      (fields
        (field (name "MANUFACTURER PART NUMBER") "RC1608J331CS")
        (field (name "MANUFACTURER") "Samsung Electro-Mechanics America, Inc")
      )
      (libsource (lib "Miscellaneous Devices") (part "Res3"))
    )
    (comp (ref "R97")
      (value "330R")
      (footprint "0603")
      (description "RES 330 OHM 1/10W 5% 0603")
      (fields
        (field (name "MANUFACTURER PART NUMBER") "RC1608J331CS")
        (field (name "MANUFACTURER") "Samsung Electro-Mechanics America, Inc")
      )
      (libsource (lib "Miscellaneous Devices") (part "Res3"))
    )
    (comp (ref "R98")
      (value "330R")
      (footprint "0603")
      (description "RES 330 OHM 1/10W 5% 0603")
      (fields
        (field (name "MANUFACTURER PART NUMBER") "RC1608J331CS")
        (field (name "MANUFACTURER") "Samsung Electro-Mechanics America, Inc")
      )
      (libsource (lib "Miscellaneous Devices") (part "Res3"))
    )
    (comp (ref "R99")
      (value "330R")
      (footprint "0603")
      (description "RES 330 OHM 1/10W 5% 0603")
      (fields
        (field (name "MANUFACTURER PART NUMBER") "RC1608J331CS")
        (field (name "MANUFACTURER") "Samsung Electro-Mechanics America, Inc")
      )
      (libsource (lib "Miscellaneous Devices") (part "Res3"))
    )
    (comp (ref "R100")
      (value "330R")
      (footprint "0603")
      (description "RES 330 OHM 1/10W 5% 0603")
      (fields
        (field (name "MANUFACTURER PART NUMBER") "RC1608J331CS")
        (field (name "MANUFACTURER") "Samsung Electro-Mechanics America, Inc")
      )
      (libsource (lib "Miscellaneous Devices") (part "Res3"))
    )
    (comp (ref "R101")
      (value "330R")
      (footprint "0603")
      (description "RES 330 OHM 1/10W 5% 0603")
      (fields
        (field (name "MANUFACTURER PART NUMBER") "RC1608J331CS")
        (field (name "MANUFACTURER") "Samsung Electro-Mechanics America, Inc")
      )
      (libsource (lib "Miscellaneous Devices") (part "Res3"))
    )
    (comp (ref "R102")
      (value "330R")
      (footprint "0603")
      (description "RES 330 OHM 1/10W 5% 0603")
      (fields
        (field (name "MANUFACTURER PART NUMBER") "RC1608J331CS")
        (field (name "MANUFACTURER") "Samsung Electro-Mechanics America, Inc")
      )
      (libsource (lib "Miscellaneous Devices") (part "Res3"))
    )
    (comp (ref "R103")
      (value "240k")
      (footprint "0603")
      (description "RES 240K OHM 1/10W 1% 0603")
      (fields
        (field (name "MANUFACTURER PART NUMBER") "RC1608F244CS")
        (field (name "MANUFACTURER") "Samsung Electro-Mechanics America, Inc")
      )
      (libsource (lib "Miscellaneous Devices") (part "Res3"))
    )
    (comp (ref "R104")
      (value "100k")
      (footprint "0603")
      (description "RES 100K OHM 1/10W 1% 0603")
      (fields
        (field (name "MANUFACTURER PART NUMBER") "RC1608F104CS")
        (field (name "MANUFACTURER") "Samsung Electro-Mechanics America, Inc")
      )
      (libsource (lib "Miscellaneous Devices") (part "Res3"))
    )
    (comp (ref "R105")
      (value "10k")
      (footprint "0603")
      (description "RES 10K OHM 1/10W 5% 0603 SMD")
      (fields
        (field (name "MANUFACTURER PART NUMBER") "RC0603JR-0710KL")
        (field (name "MANUFACTURER") "Yageo")
      )
      (libsource (lib "Miscellaneous Devices") (part "Res3"))
    )
    (comp (ref "R106")
      (value "240k")
      (footprint "0603")
      (description "RES 240K OHM 1/10W 1% 0603")
      (fields
        (field (name "MANUFACTURER PART NUMBER") "RC1608F244CS")
        (field (name "MANUFACTURER") "Samsung Electro-Mechanics America, Inc")
      )
      (libsource (lib "Miscellaneous Devices") (part "Res3"))
    )
    (comp (ref "R107")
      (value "100k")
      (footprint "0603")
      (description "RES 100K OHM 1/10W 1% 0603")
      (fields
        (field (name "MANUFACTURER PART NUMBER") "RC1608F104CS")
        (field (name "MANUFACTURER") "Samsung Electro-Mechanics America, Inc")
      )
      (libsource (lib "Miscellaneous Devices") (part "Res3"))
    )
    (comp (ref "R109")
      (value "1.69k")
      (footprint "0603")
      (description "RES 1.69K OHM 1/10W 1% 0603")
      (fields
        (field (name "MANUFACTURER PART NUMBER") "RC1608F1691CS")
        (field (name "MANUFACTURER") "Samsung Electro-Mechanics America, Inc")
      )
      (libsource (lib "Miscellaneous Devices") (part "Res3"))
    )
    (comp (ref "R110")
      (value "1k")
      (footprint "0603")
      (description "RES 1K OHM 1/10W 1% 0603")
      (fields
        (field (name "MANUFACTURER PART NUMBER") "RC1608F102CS")
        (field (name "MANUFACTURER") "Samsung Electro-Mechanics America, Inc")
      )
      (libsource (lib "Miscellaneous Devices") (part "Res3"))
    )
    (comp (ref "R112")
      (value "10R")
      (footprint "6-0805_L")
      (description "RES 10 OHM 1/8W 5% 0805")
      (fields
        (field (name "MANUFACTURER PART NUMBER") "RC2012J100CS")
        (field (name "MANUFACTURER") "Samsung Electro-Mechanics America, Inc")
      )
      (libsource (lib "Miscellaneous Devices") (part "Res3"))
    )
    (comp (ref "R113")
      (value "100k")
      (footprint "0603")
      (description "RES 100K OHM 1/10W 5% 0603")
      (fields
        (field (name "MANUFACTURER PART NUMBER") "RC1608J104CS")
        (field (name "MANUFACTURER") "Samsung Electro-Mechanics America, Inc")
      )
      (libsource (lib "Miscellaneous Devices") (part "Res3"))
    )
    (comp (ref "R114")
      (value "3.09k")
      (footprint "0603")
      (description "RES 3.09K OHM 1/10W 1% 0603 SMD")
      (fields
        (field (name "MANUFACTURER PART NUMBER") "CRCW06033K09FKEA")
        (field (name "MANUFACTURER") "Vishay Dale")
      )
      (libsource (lib "Miscellaneous Devices") (part "Res3"))
    )
    (comp (ref "R115")
      (value "1k")
      (footprint "0603")
      (description "RES 1K OHM 1/10W 1% 0603")
      (fields
        (field (name "MANUFACTURER PART NUMBER") "RC1608F102CS")
        (field (name "MANUFACTURER") "Samsung Electro-Mechanics America, Inc")
      )
      (libsource (lib "Miscellaneous Devices") (part "Res3"))
    )
    (comp (ref "R116")
      (value "100k")
      (footprint "0603")
      (description "RES 100K OHM 1/10W 5% 0603")
      (fields
        (field (name "MANUFACTURER PART NUMBER") "RC1608J104CS")
        (field (name "MANUFACTURER") "Samsung Electro-Mechanics America, Inc")
      )
      (libsource (lib "Miscellaneous Devices") (part "Res3"))
    )
    (comp (ref "R117")
      (value "10k")
      (footprint "0603")
      (description "RES 10K OHM 1/10W 1% 0603")
      (fields
        (field (name "MANUFACTURER PART NUMBER") "RC1608F103CS")
        (field (name "MANUFACTURER") "Samsung Electro-Mechanics America, Inc")
      )
      (libsource (lib "Miscellaneous Devices") (part "Res3"))
    )
    (comp (ref "R118")
      (value "4.02k")
      (footprint "0603")
      (description "RES 4.02K OHM 1/10W 1% 0603")
      (fields
        (field (name "MANUFACTURER PART NUMBER") "RC1608F4021CS")
        (field (name "MANUFACTURER") "Samsung Electro-Mechanics America, Inc")
      )
      (libsource (lib "Miscellaneous Devices") (part "Res3"))
    )
    (comp (ref "R119")
      (value "10M")
      (footprint "0603")
      (description "RES 10M OHM 1/10W 5% 0603")
      (fields
        (field (name "MANUFACTURER PART NUMBER") "RC1608J106CS")
        (field (name "MANUFACTURER") "Samsung Electro-Mechanics America, Inc")
      )
      (libsource (lib "Miscellaneous Devices") (part "Res3"))
    )
    (comp (ref "R120")
      (value "4.02k")
      (footprint "0603")
      (description "RES 4.02K OHM 1/10W 1% 0603")
      (fields
        (field (name "MANUFACTURER PART NUMBER") "RC1608F4021CS")
        (field (name "MANUFACTURER") "Samsung Electro-Mechanics America, Inc")
      )
      (libsource (lib "Miscellaneous Devices") (part "Res3"))
    )
    (comp (ref "R121")
      (value "7.5k")
      (footprint "0603")
      (description "RES 7.5K OHM 1/10W 5% 0603")
      (fields
        (field (name "MANUFACTURER PART NUMBER") "RC1608J752CS")
        (field (name "MANUFACTURER") "Samsung Electro-Mechanics America, Inc")
      )
      (libsource (lib "Miscellaneous Devices") (part "Res3"))
    )
    (comp (ref "R122")
      (value "0R")
      (footprint "0402")
      (description "RES 0.0 OHM 1/10W JUMP 0402 SMD")
      (fields
        (field (name "MANUFACTURER PART NUMBER") "ERJ-2GE0R00X")
        (field (name "MANUFACTURER") "Panasonic Electronic Components")
      )
      (libsource (lib "Miscellaneous Devices") (part "Res3"))
    )
    (comp (ref "R123")
      (value "7.5k")
      (footprint "0603")
      (description "RES 7.5K OHM 1/10W 5% 0603")
      (fields
        (field (name "MANUFACTURER PART NUMBER") "RC1608J752CS")
        (field (name "MANUFACTURER") "Samsung Electro-Mechanics America, Inc")
      )
      (libsource (lib "Miscellaneous Devices") (part "Res3"))
    )
    (comp (ref "R124")
      (value "4.7k")
      (footprint "0603")
      (description "RES 4.7K OHM 1/10W 1% 0603")
      (fields
        (field (name "MANUFACTURER PART NUMBER") "RC1608F472CS")
        (field (name "MANUFACTURER") "Samsung Electro-Mechanics America, Inc")
      )
      (libsource (lib "Miscellaneous Devices") (part "Res3"))
    )
    (comp (ref "R125")
      (value "4.7k")
      (footprint "0603")
      (description "RES 4.7K OHM 1/10W 1% 0603")
      (fields
        (field (name "MANUFACTURER PART NUMBER") "RC1608F472CS")
        (field (name "MANUFACTURER") "Samsung Electro-Mechanics America, Inc")
      )
      (libsource (lib "Miscellaneous Devices") (part "Res3"))
    )
    (comp (ref "R126")
      (value "4.7k")
      (footprint "0603")
      (description "RES 4.7K OHM 1/10W 1% 0603")
      (fields
        (field (name "MANUFACTURER PART NUMBER") "RC1608F472CS")
        (field (name "MANUFACTURER") "Samsung Electro-Mechanics America, Inc")
      )
      (libsource (lib "Miscellaneous Devices") (part "Res3"))
    )
    (comp (ref "R127")
      (value "7.5k")
      (footprint "0603")
      (description "RES 7.5K OHM 1/10W 5% 0603")
      (fields
        (field (name "MANUFACTURER PART NUMBER") "RC1608J752CS")
        (field (name "MANUFACTURER") "Samsung Electro-Mechanics America, Inc")
      )
      (libsource (lib "Miscellaneous Devices") (part "Res3"))
    )
    (comp (ref "R128")
      (value "4.7k")
      (footprint "0603")
      (description "RES 4.7K OHM 1/10W 1% 0603")
      (fields
        (field (name "MANUFACTURER PART NUMBER") "RC1608F472CS")
        (field (name "MANUFACTURER") "Samsung Electro-Mechanics America, Inc")
      )
      (libsource (lib "Miscellaneous Devices") (part "Res3"))
    )
    (comp (ref "RT1")
      (value "Thermistor")
      (footprint "MF72-010D11")
      (description "CURRENT LIMITER INRUSH 10OHM 20%")
      (fields
        (field (name "MANUFACTURER PART NUMBER") "MF72-010D11")
        (field (name "MANUFACTURER") "Cantherm")
      )
      (libsource (lib "Miscellaneous Devices") (part "Res Thermal"))
    )
    (comp (ref "S1")
      (value "Button Button")
      (footprint "BUTTON")
      (description "SWITCH TACTILE SPST-NO 0.05A 12V")
      (fields
        (field (name "MANUFACTURER PART NUMBER") "FSMRA4JH")
        (field (name "MANUFACTURER") "TE Connectivity")
      )
      (libsource (lib "Miscellaneous Devices") (part "SW-PB"))
    )
    (comp (ref "S2")
      (value "SW-SPDT")
      (footprint "R_SPDT")
      (description "SWITCH ROCKER SPDT 5A 120V")
      (fields
        (field (name "MANUFACTURER PART NUMBER") "300SP1J1BLKM6QE")
        (field (name "MANUFACTURER") "E-Switch")
      )
      (libsource (lib "Miscellaneous Devices") (part "SW-SPDT"))
    )
    (comp (ref "U1")
      (value "Driver")
      (footprint "TSOP65P650X110_HS-20L")
      (description "3.3V/+5V, 8-Channel, Cascadable Relay Drivers  with Serial/Parallel Interface")
      (fields
        (field (name "MANUFACTURER PART NUMBER") "MAX4821EUP+")
        (field (name "MANUFACTURER") "Maxim Integrated")
      )
      (libsource (lib "MAXxxxx") (part "MAX4821"))
    )
    (comp (ref "U2")
      (value "Register")
      (footprint "SOP65P780X200_HS-28L")
      (description "16-Bit I/O Expander with Serial Interface")
      (fields
        (field (name "MANUFACTURER PART NUMBER") "MCP23017-E/SS")
        (field (name "MANUFACTURER") "Microchip Technology")
      )
      (libsource (lib "MCPxxxxx") (part "MCP23017"))
    )
    (comp (ref "U3")
      (value "Driver")
      (footprint "TSOP65P650X110_HS-20L")
      (description "3.3V/+5V, 8-Channel, Cascadable Relay Drivers  with Serial/Parallel Interface")
      (fields
        (field (name "MANUFACTURER PART NUMBER") "MAX4821EUP+")
        (field (name "MANUFACTURER") "Maxim Integrated")
      )
      (libsource (lib "MAXxxxx") (part "MAX4821"))
    )
    (comp (ref "U4")
      (value "Register")
      (footprint "SOP65P780X200_HS-28L")
      (description "16-Bit I/O Expander with Serial Interface")
      (fields
        (field (name "MANUFACTURER PART NUMBER") "MCP23017-E/SS")
        (field (name "MANUFACTURER") "Microchip Technology")
      )
      (libsource (lib "MCPxxxxx") (part "MCP23017"))
    )
    (comp (ref "U5")
      (value "Driver")
      (footprint "TSOP65P650X110_HS-20L")
      (description "3.3V/+5V, 8-Channel, Cascadable Relay Drivers  with Serial/Parallel Interface")
      (fields
        (field (name "MANUFACTURER PART NUMBER") "MAX4821EUP+")
        (field (name "MANUFACTURER") "Maxim Integrated")
      )
      (libsource (lib "MAXxxxx") (part "MAX4821"))
    )
    (comp (ref "U6")
      (value "DS1338")
      (footprint "SOIC8")
      (description "IC RTC CLK/CALENDAR I2C 8-SOIC")
      (fields
        (field (name "MANUFACTURER PART NUMBER") "DS1338Z-33+T&R")
        (field (name "MANUFACTURER") "Maxim Integrated")
      )
      (libsource (lib "thermostat_main") (part "DS1338"))
    )
    (comp (ref "U7")
      (value "TLP620")
      (footprint "TLP620")
      (description "OPTOCOUPLER TRANS 5KVRMS 4DIP")
      (fields
        (field (name "MANUFACTURER PART NUMBER") "TLP620(F)")
        (field (name "MANUFACTURER") "Toshiba Semiconductor and Storage")
      )
      (libsource (lib "thermostat_main") (part "TLP620"))
    )
    (comp (ref "U8")
      (value "TLP620")
      (footprint "TLP620")
      (description "OPTOCOUPLER TRANS 5KVRMS 4DIP")
      (fields
        (field (name "MANUFACTURER PART NUMBER") "TLP620(F)")
        (field (name "MANUFACTURER") "Toshiba Semiconductor and Storage")
      )
      (libsource (lib "thermostat_main") (part "TLP620"))
    )
    (comp (ref "U9")
      (value "TLP620")
      (footprint "TLP620")
      (description "OPTOCOUPLER TRANS 5KVRMS 4DIP")
      (fields
        (field (name "MANUFACTURER PART NUMBER") "TLP620(F)")
        (field (name "MANUFACTURER") "Toshiba Semiconductor and Storage")
      )
      (libsource (lib "thermostat_main") (part "TLP620"))
    )
    (comp (ref "U10")
      (value "TLP620")
      (footprint "TLP620")
      (description "OPTOCOUPLER TRANS 5KVRMS 4DIP")
      (fields
        (field (name "MANUFACTURER PART NUMBER") "TLP620(F)")
        (field (name "MANUFACTURER") "Toshiba Semiconductor and Storage")
      )
      (libsource (lib "thermostat_main") (part "TLP620"))
    )
    (comp (ref "U11")
      (value "SN74LVC828ADGVR")
      (footprint "24-TFSOP")
      (description "IC INVERTER 10-INPUT 24TSSOP")
      (fields
        (field (name "MANUFACTURER PART NUMBER") "SN74LVC828APWR")
        (field (name "MANUFACTURER") "Texas Instruments")
      )
      (libsource (lib "thermostat_main") (part "SN74LVC828ADGVR"))
    )
    (comp (ref "U12")
      (value "CM1293A-04SO")
      (footprint "SC74")
      (description "TVS DIODE 3.3VWM 9.9VC SC74")
      (fields (field (name "MANUFACTURER") "ON Semiconductor"))
      (libsource (lib "thermostat_main") (part "CM1293A"))
    )
    (comp (ref "U13")
      (value "CM1293A-04SO")
      (footprint "SC74")
      (description "TVS DIODE 3.3VWM 9.9VC SC74")
      (fields (field (name "MANUFACTURER") "ON Semiconductor"))
      (libsource (lib "thermostat_main") (part "CM1293A"))
    )
    (comp (ref "U14")
      (value "TLP620")
      (footprint "TLP620")
      (description "OPTOCOUPLER TRANS 5KVRMS 4DIP")
      (fields
        (field (name "MANUFACTURER PART NUMBER") "TLP620(F)")
        (field (name "MANUFACTURER") "Toshiba Semiconductor and Storage")
      )
      (libsource (lib "thermostat_main") (part "TLP620"))
    )
    (comp (ref "U15")
      (value "TLP620")
      (footprint "TLP620")
      (description "OPTOCOUPLER TRANS 5KVRMS 4DIP")
      (fields
        (field (name "MANUFACTURER PART NUMBER") "TLP620(F)")
        (field (name "MANUFACTURER") "Toshiba Semiconductor and Storage")
      )
      (libsource (lib "thermostat_main") (part "TLP620"))
    )
    (comp (ref "U16")
      (value "DS2482S-100")
      (footprint "SOIC8")
      (description "IC I2C TO 1WIRE BRIDGE 8SOIC")
      (fields
        (field (name "MANUFACTURER PART NUMBER") "DS2482S-100+T&R")
        (field (name "MANUFACTURER") "Maxim Integrated")
      )
      (libsource (lib "thermostat_main") (part "DS2482S-100"))
    )
    (comp (ref "U17")
      (value "CM1293A-04SO")
      (footprint "SC74")
      (description "TVS DIODE 3.3VWM 9.9VC SC74")
      (fields (field (name "MANUFACTURER") "ON Semiconductor"))
      (libsource (lib "thermostat_main") (part "CM1293A"))
    )
    (comp (ref "U18")
      (value "CM1293A-04SO")
      (footprint "SC74")
      (description "TVS DIODE 3.3VWM 9.9VC SC74")
      (fields (field (name "MANUFACTURER") "ON Semiconductor"))
      (libsource (lib "thermostat_main") (part "CM1293A"))
    )
    (comp (ref "U19")
      (value "TLP620")
      (footprint "TLP620")
      (description "OPTOCOUPLER TRANS 5KVRMS 4DIP")
      (fields
        (field (name "MANUFACTURER PART NUMBER") "TLP620(F)")
        (field (name "MANUFACTURER") "Toshiba Semiconductor and Storage")
      )
      (libsource (lib "thermostat_main") (part "TLP620"))
    )
    (comp (ref "U20")
      (value "TLP620")
      (footprint "TLP620")
      (description "OPTOCOUPLER TRANS 5KVRMS 4DIP")
      (fields
        (field (name "MANUFACTURER PART NUMBER") "TLP620(F)")
        (field (name "MANUFACTURER") "Toshiba Semiconductor and Storage")
      )
      (libsource (lib "thermostat_main") (part "TLP620"))
    )
    (comp (ref "U21")
      (value "TLP620")
      (footprint "TLP620")
      (description "OPTOCOUPLER TRANS 5KVRMS 4DIP")
      (fields
        (field (name "MANUFACTURER PART NUMBER") "TLP620(F)")
        (field (name "MANUFACTURER") "Toshiba Semiconductor and Storage")
      )
      (libsource (lib "thermostat_main") (part "TLP620"))
    )
    (comp (ref "U22")
      (value "TLP620")
      (footprint "TLP620")
      (description "OPTOCOUPLER TRANS 5KVRMS 4DIP")
      (fields
        (field (name "MANUFACTURER PART NUMBER") "TLP620(F)")
        (field (name "MANUFACTURER") "Toshiba Semiconductor and Storage")
      )
      (libsource (lib "thermostat_main") (part "TLP620"))
    )
    (comp (ref "U25")
      (value "SN74LVC828ADGVR")
      (footprint "24-TFSOP")
      (description "IC INVERTER 10-INPUT 24TSSOP")
      (fields
        (field (name "MANUFACTURER PART NUMBER") "SN74LVC828APWR")
        (field (name "MANUFACTURER") "Texas Instruments")
      )
      (libsource (lib "thermostat_main") (part "SN74LVC828ADGVR"))
    )
    (comp (ref "U26")
      (value "TLC272BCDR")
      (footprint "SO8")
      (description "IC OPAMP GP 2.2MHZ 8SOIC")
      (fields (field (name "MANUFACTURER") "Texas Instruments"))
      (libsource (lib "thermostat_main") (part "LMC662"))
    )
    (comp (ref "U27")
      (value "SN74LVC828ADGVR")
      (footprint "24-TFSOP")
      (description "IC INVERTER 10-INPUT 24TSSOP")
      (fields
        (field (name "MANUFACTURER PART NUMBER") "SN74LVC828APWR")
        (field (name "MANUFACTURER") "Texas Instruments")
      )
      (libsource (lib "thermostat_main") (part "SN74LVC828ADGVR"))
    )
    (comp (ref "U28")
      (value "LMC660")
      (footprint "SOIC14")
      (description "IC OPAMP GP 1.4MHZ RRO 14SOIC")
      (fields
        (field (name "MANUFACTURER PART NUMBER") "LMC660AIMX/NOPB")
        (field (name "MANUFACTURER") "Texas Instruments")
      )
      (libsource (lib "thermostat_main") (part "LMC660"))
    )
    (comp (ref "U29")
      (value "AD5245")
      (footprint "SOT23-8")
      (description "IC DGTL POT 256POS SOT23-8")
      (fields
        (field (name "MANUFACTURER PART NUMBER") "AD5245BRJZ10-R2")
        (field (name "MANUFACTURER") "Analog Devices Inc")
      )
      (libsource (lib "thermostat_main") (part "AD5245"))
    )
    (comp (ref "U30")
      (value "74HC4094")
      (footprint "16TSSOP")
      (description "IC SHIFT LATCH REG SIPO 16-TSSOP")
      (fields
        (field (name "MANUFACTURER PART NUMBER") "M74HC4094TTR")
        (field (name "MANUFACTURER") "STMicroelectronics")
      )
      (libsource (lib "thermostat_main") (part "74HC4094"))
    )
    (comp (ref "U31")
      (value "AD7993")
      (footprint "16TSSOP")
      (description "IC ADC 10BIT 4CH W/I2C 16-TSSOP")
      (fields
        (field (name "MANUFACTURER PART NUMBER") "AD7993BRUZ-0")
        (field (name "MANUFACTURER") "Analog Devices Inc")
      )
      (libsource (lib "thermostat_main") (part "AD7993"))
    )
    (comp (ref "U32")
      (value "LM2576")
      (footprint "DDPAK")
      (description "IC REG BUCK 3A TO263-5")
      (fields
        (field (name "MANUFACTURER PART NUMBER") "LM2576HVSX-ADJ/NOPB")
        (field (name "MANUFACTURER") "Texas Instruments")
      )
      (libsource (lib "thermostat_main") (part "LM2576HVSX-5.0"))
    )
    (comp (ref "U33")
      (value "LM4132AMF-3.3/NOPB")
      (footprint "SOT23-5")
      (description "IC VREF SERIES PREC 3.3V SOT23-5")
      (fields
        (field (name "MANUFACTURER PART NUMBER") "LM4132EMF-3.3/NOPB")
        (field (name "MANUFACTURER") "Texas Instruments")
      )
      (libsource (lib "thermostat_main") (part "LM4132AMF-3.3/NOPB"))
    )
    (comp (ref "U34")
      (value "74HC4094")
      (footprint "16TSSOP")
      (description "IC SHIFT LATCH REG SIPO 16-TSSOP")
      (fields
        (field (name "MANUFACTURER PART NUMBER") "M74HC4094TTR")
        (field (name "MANUFACTURER") "STMicroelectronics")
      )
      (libsource (lib "thermostat_main") (part "74HC4094"))
    )
    (comp (ref "U35")
      (value "74HC4040")
      (footprint "16TSSOP")
      (description "IC COUNTER 12STAGE BIN 16-TSSOP")
      (fields
        (field (name "MANUFACTURER PART NUMBER") "MC74HC4040ADTR2G")
        (field (name "MANUFACTURER") "ON Semiconductor")
      )
      (libsource (lib "thermostat_main") (part "74HC4040"))
    )
    (comp (ref "U36")
      (value "NSI45060")
      (footprint "DPAK3")
      (description "IC LED DRVR SBT CCR DPAK")
      (fields
        (field (name "MANUFACTURER PART NUMBER") "NSI45060JDT4G")
        (field (name "MANUFACTURER") "ON Semiconductor")
      )
      (libsource (lib "thermostat_main") (part "NSI45060"))
    )
    (comp (ref "U37")
      (value "LM2576")
      (footprint "DDPAK")
      (description "IC REG BUCK 3A TO263-5")
      (fields
        (field (name "MANUFACTURER PART NUMBER") "LM2576HVSX-ADJ/NOPB")
        (field (name "MANUFACTURER") "Texas Instruments")
      )
      (libsource (lib "thermostat_main") (part "LM2576HVSX-5.0"))
    )
    (comp (ref "U38")
      (value "MAX98306")
      (footprint "TDFN14")
      (description "IC AMP AUDIO 3.7W STER D 14TDFN")
      (fields
        (field (name "MANUFACTURER PART NUMBER") "MAX98306ETD+T")
        (field (name "MANUFACTURER") "Maxim Integrated")
      )
      (libsource (lib "thermostat_main") (part "MAX98306"))
    )
    (comp (ref "U39")
      (value "74HC4094")
      (footprint "16TSSOP")
      (description "IC SHIFT LATCH REG SIPO 16-TSSOP")
      (fields
        (field (name "MANUFACTURER PART NUMBER") "M74HC4094TTR")
        (field (name "MANUFACTURER") "STMicroelectronics")
      )
      (libsource (lib "thermostat_main") (part "74HC4094"))
    )
    (comp (ref "U40")
      (value "TGS5042")
      (footprint "TGS5042-A00")
      (description "Technical Information for Carbon Monoxide Sensors")
      (fields (field (name "MANUFACTURER") "Figaro") (field (name "MANUFACTURER PART NUMBER") "TGS5042-A00"))
      (libsource (lib "thermostat_main") (part "TGS5042"))
    )
    (comp (ref "VR1")
      (value "Varistor")
      (description "VARISTOR 61V 250A DISC 5MM")
      (fields
        (field (name "MANUFACTURER PART NUMBER") "ERZ-V05D680")
        (field (name "MANUFACTURER") "Panasonic Electronic Components")
      )
      (libsource (lib "Miscellaneous Devices") (part "Res Varistor"))
    )
    (comp (ref "VR2")
      (value "Varistor")
      (description "VARISTOR 61V 250A DISC 5MM")
      (fields
        (field (name "MANUFACTURER PART NUMBER") "ERZ-V05D680")
        (field (name "MANUFACTURER") "Panasonic Electronic Components")
      )
      (libsource (lib "Miscellaneous Devices") (part "Res Varistor"))
    )
    (comp (ref "VR3")
      (value "Varistor")
      (description "VARISTOR 61V 250A DISC 5MM")
      (fields
        (field (name "MANUFACTURER PART NUMBER") "ERZ-V05D680")
        (field (name "MANUFACTURER") "Panasonic Electronic Components")
      )
      (libsource (lib "Miscellaneous Devices") (part "Res Varistor"))
    )
    (comp (ref "VR4")
      (value "Varistor")
      (description "VARISTOR 61V 250A DISC 5MM")
      (fields
        (field (name "MANUFACTURER PART NUMBER") "ERZ-V05D680")
        (field (name "MANUFACTURER") "Panasonic Electronic Components")
      )
      (libsource (lib "Miscellaneous Devices") (part "Res Varistor"))
    )
    (comp (ref "VR5")
      (value "Varistor")
      (description "VARISTOR 61V 250A DISC 5MM")
      (fields
        (field (name "MANUFACTURER PART NUMBER") "ERZ-V05D680")
        (field (name "MANUFACTURER") "Panasonic Electronic Components")
      )
      (libsource (lib "Miscellaneous Devices") (part "Res Varistor"))
    )
    (comp (ref "VR6")
      (value "Varistor")
      (description "VARISTOR 61V 250A DISC 5MM")
      (fields
        (field (name "MANUFACTURER PART NUMBER") "ERZ-V05D680")
        (field (name "MANUFACTURER") "Panasonic Electronic Components")
      )
      (libsource (lib "Miscellaneous Devices") (part "Res Varistor"))
    )
    (comp (ref "VR7")
      (value "Varistor")
      (description "VARISTOR 61V 250A DISC 5MM")
      (fields
        (field (name "MANUFACTURER PART NUMBER") "ERZ-V05D680")
        (field (name "MANUFACTURER") "Panasonic Electronic Components")
      )
      (libsource (lib "Miscellaneous Devices") (part "Res Varistor"))
    )
    (comp (ref "VR8")
      (value "Varistor")
      (description "VARISTOR 61V 250A DISC 5MM")
      (fields
        (field (name "MANUFACTURER PART NUMBER") "ERZ-V05D680")
        (field (name "MANUFACTURER") "Panasonic Electronic Components")
      )
      (libsource (lib "Miscellaneous Devices") (part "Res Varistor"))
    )
    (comp (ref "VR9")
      (value "Varistor")
      (description "VARISTOR 61V 250A DISC 5MM")
      (fields
        (field (name "MANUFACTURER PART NUMBER") "ERZ-V05D680")
        (field (name "MANUFACTURER") "Panasonic Electronic Components")
      )
      (libsource (lib "Miscellaneous Devices") (part "Res Varistor"))
    )
    (comp (ref "VR10")
      (value "Varistor")
      (description "VARISTOR 61V 250A DISC 5MM")
      (fields
        (field (name "MANUFACTURER PART NUMBER") "ERZ-V05D680")
        (field (name "MANUFACTURER") "Panasonic Electronic Components")
      )
      (libsource (lib "Miscellaneous Devices") (part "Res Varistor"))
    )
    (comp (ref "VR11")
      (value "Varistor")
      (description "VARISTOR 61V 250A DISC 5MM")
      (fields
        (field (name "MANUFACTURER PART NUMBER") "ERZ-V05D680")
        (field (name "MANUFACTURER") "Panasonic Electronic Components")
      )
      (libsource (lib "Miscellaneous Devices") (part "Res Varistor"))
    )
    (comp (ref "VR12")
      (value "Varistor")
      (description "VARISTOR 61V 250A DISC 5MM")
      (fields
        (field (name "MANUFACTURER PART NUMBER") "ERZ-V05D680")
        (field (name "MANUFACTURER") "Panasonic Electronic Components")
      )
      (libsource (lib "Miscellaneous Devices") (part "Res Varistor"))
    )
    (comp (ref "VR13")
      (value "Varistor")
      (description "VARISTOR 61V 250A DISC 5MM")
      (fields
        (field (name "MANUFACTURER PART NUMBER") "ERZ-V05D680")
        (field (name "MANUFACTURER") "Panasonic Electronic Components")
      )
      (libsource (lib "Miscellaneous Devices") (part "Res Varistor"))
    )
    (comp (ref "VR14")
      (value "Varistor")
      (description "VARISTOR 61V 250A DISC 5MM")
      (fields
        (field (name "MANUFACTURER PART NUMBER") "ERZ-V05D680")
        (field (name "MANUFACTURER") "Panasonic Electronic Components")
      )
      (libsource (lib "Miscellaneous Devices") (part "Res Varistor"))
    )
  )
  (nets
    (net (code "1") (name "/A0") (class "Default")
      (node (ref "U1") (pin "6") (pinfunction "A0_6") (pintype "passive"))
      (node (ref "U2") (pin "1") (pinfunction "GPB0_1") (pintype "passive"))
      (node (ref "U3") (pin "6") (pinfunction "A0_6") (pintype "passive"))
      (node (ref "U5") (pin "6") (pinfunction "A0_6") (pintype "passive"))
    )
    (net (code "2") (name "/A1") (class "Default")
      (node (ref "U1") (pin "7") (pinfunction "A1_7") (pintype "passive"))
      (node (ref "U2") (pin "2") (pinfunction "GPB1_2") (pintype "passive"))
      (node (ref "U3") (pin "7") (pinfunction "A1_7") (pintype "passive"))
      (node (ref "U5") (pin "7") (pinfunction "A1_7") (pintype "passive"))
    )
    (net (code "3") (name "/A2") (class "Default")
      (node (ref "U1") (pin "8") (pinfunction "A2_8") (pintype "passive"))
      (node (ref "U2") (pin "3") (pinfunction "GPB2_3") (pintype "passive"))
      (node (ref "U3") (pin "8") (pinfunction "A2_8") (pintype "passive"))
      (node (ref "U5") (pin "8") (pinfunction "A2_8") (pintype "passive"))
    )
    (net (code "4") (name "/ADC2") (class "Default")
      (node (ref "D32") (pin "3") (pinfunction "A_3") (pintype "passive"))
      (node (ref "R126") (pin "1") (pinfunction "1_1") (pintype "passive"))
      (node (ref "U28") (pin "1") (pinfunction "OUT1_1") (pintype "passive"))
      (node (ref "U28") (pin "2") (pinfunction "IN1(-)_2") (pintype "passive"))
      (node (ref "U31") (pin "9") (pinfunction "VIN4_9") (pintype "passive"))
    )
    (net (code "5") (name "/ADC3") (class "Default")
      (node (ref "D31") (pin "3") (pinfunction "A_3") (pintype "passive"))
      (node (ref "R125") (pin "1") (pinfunction "1_1") (pintype "passive"))
      (node (ref "U28") (pin "6") (pinfunction "IN2(-)_6") (pintype "passive"))
      (node (ref "U28") (pin "7") (pinfunction "OUT2_7") (pintype "passive"))
      (node (ref "U31") (pin "8") (pinfunction "VIN3_8") (pintype "passive"))
    )
    (net (code "6") (name "/ADC4") (class "Default")
      (node (ref "D30") (pin "3") (pinfunction "A_3") (pintype "passive"))
      (node (ref "R124") (pin "1") (pinfunction "1_1") (pintype "passive"))
      (node (ref "U28") (pin "8") (pinfunction "OUT3_8") (pintype "passive"))
      (node (ref "U28") (pin "9") (pinfunction "IN3(-)_9") (pintype "passive"))
      (node (ref "U31") (pin "10") (pinfunction "VIN2_10") (pintype "passive"))
    )
    (net (code "7") (name "/ADC_ALR") (class "Default")
      (node (ref "R117") (pin "2") (pinfunction "2_2") (pintype "passive"))
      (node (ref "U31") (pin "13") (pinfunction "ALR/BUSY_13") (pintype "passive"))
      (node (ref "U4") (pin "28") (pinfunction "GPA7_28") (pintype "passive"))
    )
    (net (code "8") (name "/ADC_CONV") (class "Default")
      (node (ref "U2") (pin "27") (pinfunction "GPA6_27") (pintype "passive"))
      (node (ref "U31") (pin "12") (pinfunction "/CONVST_12") (pintype "passive"))
    )
    (net (code "9") (name "/AUDIO_G") (class "Default")
      (node (ref "P22") (pin "2") (pinfunction "2_2") (pintype "passive"))
      (node (ref "P22") (pin "4") (pinfunction "4_4") (pintype "passive"))
      (node (ref "P22") (pin "6") (pinfunction "6_6") (pintype "passive"))
      (node (ref "P22") (pin "8") (pinfunction "8_8") (pintype "passive"))
      (node (ref "U38") (pin "5") (pinfunction "GAIN_5") (pintype "passive"))
    )
    (net (code "10") (name "/AUDIO_SHDN") (class "Default")
      (node (ref "R11") (pin "1") (pinfunction "1_1") (pintype "passive"))
      (node (ref "U2") (pin "28") (pinfunction "GPA7_28") (pintype "passive"))
      (node (ref "U38") (pin "2") (pinfunction "/SHDN_2") (pintype "passive"))
    )
    (net (code "11") (name "/AUX1") (class "Default")
      (node (ref "K13") (pin "11") (pinfunction "11_11") (pintype "passive"))
      (node (ref "K13") (pin "6") (pinfunction "6_6") (pintype "passive"))
      (node (ref "P3") (pin "8") (pinfunction "8_8") (pintype "passive"))
      (node (ref "R82") (pin "1") (pinfunction "1_1") (pintype "passive"))
    )
    (net (code "12") (name "/AUX2") (class "Default")
      (node (ref "K13") (pin "13") (pinfunction "13_13") (pintype "passive"))
      (node (ref "K13") (pin "4") (pinfunction "4_4") (pintype "passive"))
      (node (ref "P4") (pin "3") (pinfunction "3_3") (pintype "passive"))
      (node (ref "R65") (pin "2") (pinfunction "2_2") (pintype "passive"))
    )
    (net (code "13") (name "/C") (class "Default")
      (node (ref "P21") (pin "2") (pinfunction "GND_2") (pintype "passive"))
      (node (ref "RT1") (pin "1") (pinfunction "1_1") (pintype "passive"))
    )
    (net (code "14") (name "/C1") (class "Default")
      (node (ref "C13") (pin "1") (pinfunction "1_1") (pintype "passive"))
      (node (ref "C14") (pin "1") (pinfunction "1_1") (pintype "passive"))
      (node (ref "C16") (pin "1") (pinfunction "1_1") (pintype "passive"))
      (node (ref "C22") (pin "1") (pinfunction "1_1") (pintype "passive"))
      (node (ref "C24") (pin "1") (pinfunction "1_1") (pintype "passive"))
      (node (ref "C28") (pin "1") (pinfunction "1_1") (pintype "passive"))
      (node (ref "C30") (pin "1") (pinfunction "1_1") (pintype "passive"))
      (node (ref "C36") (pin "1") (pinfunction "1_1") (pintype "passive"))
      (node (ref "P3") (pin "3") (pinfunction "3_3") (pintype "passive"))
      (node (ref "P4") (pin "8") (pinfunction "8_8") (pintype "passive"))
      (node (ref "U10") (pin "2") (pinfunction "AN/CAT_2") (pintype "passive"))
      (node (ref "U14") (pin "2") (pinfunction "AN/CAT_2") (pintype "passive"))
      (node (ref "U15") (pin "2") (pinfunction "AN/CAT_2") (pintype "passive"))
      (node (ref "U19") (pin "2") (pinfunction "AN/CAT_2") (pintype "passive"))
      (node (ref "U20") (pin "2") (pinfunction "AN/CAT_2") (pintype "passive"))
      (node (ref "U21") (pin "2") (pinfunction "AN/CAT_2") (pintype "passive"))
      (node (ref "U22") (pin "2") (pinfunction "AN/CAT_2") (pintype "passive"))
      (node (ref "U7") (pin "2") (pinfunction "AN/CAT_2") (pintype "passive"))
      (node (ref "U8") (pin "2") (pinfunction "AN/CAT_2") (pintype "passive"))
      (node (ref "U9") (pin "2") (pinfunction "AN/CAT_2") (pintype "passive"))
      (node (ref "VR1") (pin "1") (pinfunction "1_1") (pintype "passive"))
      (node (ref "VR11") (pin "1") (pinfunction "1_1") (pintype "passive"))
      (node (ref "VR13") (pin "1") (pinfunction "1_1") (pintype "passive"))
      (node (ref "VR2") (pin "1") (pinfunction "1_1") (pintype "passive"))
      (node (ref "VR3") (pin "1") (pinfunction "1_1") (pintype "passive"))
      (node (ref "VR5") (pin "1") (pinfunction "1_1") (pintype "passive"))
      (node (ref "VR7") (pin "1") (pinfunction "1_1") (pintype "passive"))
      (node (ref "VR9") (pin "1") (pinfunction "1_1") (pintype "passive"))
    )
    (net (code "15") (name "/COM1") (class "Default")
      (node (ref "K11") (pin "13") (pinfunction "13_13") (pintype "passive"))
      (node (ref "K11") (pin "4") (pinfunction "4_4") (pintype "passive"))
      (node (ref "P7") (pin "2") (pinfunction "GND_2") (pintype "passive"))
      (node (ref "R47") (pin "2") (pinfunction "2_2") (pintype "passive"))
    )
    (net (code "16") (name "/COM2") (class "Default")
      (node (ref "K15") (pin "13") (pinfunction "13_13") (pintype "passive"))
      (node (ref "K15") (pin "4") (pinfunction "4_4") (pintype "passive"))
      (node (ref "P8") (pin "2") (pinfunction "GND_2") (pintype "passive"))
      (node (ref "R51") (pin "2") (pinfunction "2_2") (pintype "passive"))
    )
    (net (code "17") (name "/COM3") (class "Default")
      (node (ref "K19") (pin "13") (pinfunction "13_13") (pintype "passive"))
      (node (ref "K19") (pin "4") (pinfunction "4_4") (pintype "passive"))
      (node (ref "P9") (pin "2") (pinfunction "GND_2") (pintype "passive"))
      (node (ref "R57") (pin "2") (pinfunction "2_2") (pintype "passive"))
    )
    (net (code "18") (name "/COM4") (class "Default")
      (node (ref "K12") (pin "13") (pinfunction "13_13") (pintype "passive"))
      (node (ref "K12") (pin "4") (pinfunction "4_4") (pintype "passive"))
      (node (ref "P11") (pin "2") (pinfunction "GND_2") (pintype "passive"))
      (node (ref "R62") (pin "2") (pinfunction "2_2") (pintype "passive"))
    )
    (net (code "19") (name "/COM5") (class "Default")
      (node (ref "K16") (pin "13") (pinfunction "13_13") (pintype "passive"))
      (node (ref "K16") (pin "4") (pinfunction "4_4") (pintype "passive"))
      (node (ref "P12") (pin "2") (pinfunction "GND_2") (pintype "passive"))
      (node (ref "R66") (pin "2") (pinfunction "2_2") (pintype "passive"))
    )
    (net (code "20") (name "/COM6") (class "Default")
      (node (ref "K20") (pin "13") (pinfunction "13_13") (pintype "passive"))
      (node (ref "K20") (pin "4") (pinfunction "4_4") (pintype "passive"))
      (node (ref "P14") (pin "2") (pinfunction "GND_2") (pintype "passive"))
      (node (ref "R75") (pin "2") (pinfunction "2_2") (pintype "passive"))
    )
    (net (code "21") (name "/COMP1") (class "Default")
      (node (ref "C11") (pin "1") (pinfunction "2_1") (pintype "passive"))
      (node (ref "R29") (pin "2") (pinfunction "2_2") (pintype "passive"))
      (node (ref "U11") (pin "2") (pinfunction "A1_2") (pintype "passive"))
      (node (ref "U4") (pin "1") (pinfunction "GPB0_1") (pintype "passive"))
      (node (ref "U7") (pin "4") (pinfunction "COLLECTOR_4") (pintype "passive"))
    )
    (net (code "22") (name "/COMP2") (class "Default")
      (node (ref "C20") (pin "1") (pinfunction "2_1") (pintype "passive"))
      (node (ref "R44") (pin "2") (pinfunction "2_2") (pintype "passive"))
      (node (ref "U11") (pin "3") (pinfunction "A2_3") (pintype "passive"))
      (node (ref "U4") (pin "2") (pinfunction "GPB1_2") (pintype "passive"))
      (node (ref "U9") (pin "4") (pinfunction "COLLECTOR_4") (pintype "passive"))
    )
    (net (code "23") (name "/COMP3") (class "Default")
      (node (ref "C34") (pin "1") (pinfunction "2_1") (pintype "passive"))
      (node (ref "R58") (pin "2") (pinfunction "2_2") (pintype "passive"))
      (node (ref "U11") (pin "4") (pinfunction "A3_4") (pintype "passive"))
      (node (ref "U14") (pin "4") (pinfunction "COLLECTOR_4") (pintype "passive"))
      (node (ref "U4") (pin "3") (pinfunction "GPB2_3") (pintype "passive"))
    )
    (net (code "24") (name "/COMP4") (class "Default")
      (node (ref "C38") (pin "1") (pinfunction "2_1") (pintype "passive"))
      (node (ref "R76") (pin "2") (pinfunction "2_2") (pintype "passive"))
      (node (ref "U11") (pin "5") (pinfunction "A4_5") (pintype "passive"))
      (node (ref "U19") (pin "4") (pinfunction "COLLECTOR_4") (pintype "passive"))
      (node (ref "U4") (pin "4") (pinfunction "GPB3_4") (pintype "passive"))
    )
    (net (code "25") (name "/COMP5") (class "Default")
      (node (ref "C48") (pin "1") (pinfunction "2_1") (pintype "passive"))
      (node (ref "R80") (pin "2") (pinfunction "2_2") (pintype "passive"))
      (node (ref "U11") (pin "6") (pinfunction "A5_6") (pintype "passive"))
      (node (ref "U21") (pin "4") (pinfunction "COLLECTOR_4") (pintype "passive"))
      (node (ref "U4") (pin "21") (pinfunction "GPA0_21") (pintype "passive"))
    )
    (net (code "26") (name "/COMP6") (class "Default")
      (node (ref "C35") (pin "1") (pinfunction "2_1") (pintype "passive"))
      (node (ref "R59") (pin "2") (pinfunction "2_2") (pintype "passive"))
      (node (ref "U11") (pin "7") (pinfunction "A6_7") (pintype "passive"))
      (node (ref "U15") (pin "4") (pinfunction "COLLECTOR_4") (pintype "passive"))
      (node (ref "U4") (pin "22") (pinfunction "GPA1_22") (pintype "passive"))
    )
    (net (code "27") (name "/COMP7") (class "Default")
      (node (ref "C39") (pin "1") (pinfunction "2_1") (pintype "passive"))
      (node (ref "R77") (pin "2") (pinfunction "2_2") (pintype "passive"))
      (node (ref "U11") (pin "8") (pinfunction "A7_8") (pintype "passive"))
      (node (ref "U20") (pin "4") (pinfunction "COLLECTOR_4") (pintype "passive"))
      (node (ref "U4") (pin "23") (pinfunction "GPA2_23") (pintype "passive"))
    )
    (net (code "28") (name "/COMP8") (class "Default")
      (node (ref "C49") (pin "1") (pinfunction "2_1") (pintype "passive"))
      (node (ref "R81") (pin "2") (pinfunction "2_2") (pintype "passive"))
      (node (ref "U11") (pin "9") (pinfunction "A8_9") (pintype "passive"))
      (node (ref "U22") (pin "4") (pinfunction "COLLECTOR_4") (pintype "passive"))
      (node (ref "U4") (pin "24") (pinfunction "GPA3_24") (pintype "passive"))
    )
    (net (code "29") (name "/COMP9") (class "Default")
      (node (ref "C12") (pin "1") (pinfunction "2_1") (pintype "passive"))
      (node (ref "R30") (pin "2") (pinfunction "2_2") (pintype "passive"))
      (node (ref "U11") (pin "10") (pinfunction "A9_10") (pintype "passive"))
      (node (ref "U4") (pin "25") (pinfunction "GPA4_25") (pintype "passive"))
      (node (ref "U8") (pin "4") (pinfunction "COLLECTOR_4") (pintype "passive"))
    )
    (net (code "30") (name "/COMP10") (class "Default")
      (node (ref "C21") (pin "1") (pinfunction "2_1") (pintype "passive"))
      (node (ref "R45") (pin "2") (pinfunction "2_2") (pintype "passive"))
      (node (ref "U10") (pin "4") (pinfunction "COLLECTOR_4") (pintype "passive"))
      (node (ref "U11") (pin "11") (pinfunction "A10_11") (pintype "passive"))
      (node (ref "U4") (pin "26") (pinfunction "GPA5_26") (pintype "passive"))
    )
    (net (code "31") (name "/CO_Aout") (class "Default")
      (node (ref "C64") (pin "2") (pinfunction "2_2") (pintype "passive"))
      (node (ref "C65") (pin "2") (pinfunction "2_2") (pintype "passive"))
      (node (ref "D29") (pin "3") (pinfunction "A_3") (pintype "passive"))
      (node (ref "R118") (pin "1") (pinfunction "1_1") (pintype "passive"))
      (node (ref "R121") (pin "2") (pinfunction "2_2") (pintype "passive"))
      (node (ref "U31") (pin "7") (pinfunction "VIN1_7") (pintype "passive"))
    )
    (net (code "32") (name "/CO_Dout") (class "Default")
      (node (ref "R120") (pin "1") (pinfunction "1_1") (pintype "passive"))
      (node (ref "R123") (pin "2") (pinfunction "2_2") (pintype "passive"))
      (node (ref "U4") (pin "27") (pinfunction "GPA6_27") (pintype "passive"))
    )
    (net (code "33") (name "/CS1") (class "Default")
      (node (ref "R2") (pin "2") (pinfunction "2_2") (pintype "passive"))
      (node (ref "U1") (pin "4") (pinfunction "/CS_4") (pintype "passive"))
      (node (ref "U2") (pin "5") (pinfunction "GPB4_5") (pintype "passive"))
    )
    (net (code "34") (name "/CS2") (class "Default")
      (node (ref "R10") (pin "2") (pinfunction "2_2") (pintype "passive"))
      (node (ref "U2") (pin "8") (pinfunction "GPB7_8") (pintype "passive"))
      (node (ref "U3") (pin "4") (pinfunction "/CS_4") (pintype "passive"))
    )
    (net (code "35") (name "/CS3") (class "Default")
      (node (ref "R16") (pin "2") (pinfunction "2_2") (pintype "passive"))
      (node (ref "U2") (pin "23") (pinfunction "GPA2_23") (pintype "passive"))
      (node (ref "U5") (pin "4") (pinfunction "/CS_4") (pintype "passive"))
    )
    (net (code "36") (name "/DB0") (class "Default")
      (node (ref "P19") (pin "2") (pinfunction "2_2") (pintype "passive"))
      (node (ref "U30") (pin "4") (pinfunction "Q1_4") (pintype "passive"))
    )
    (net (code "37") (name "/DB1") (class "Default")
      (node (ref "P19") (pin "4") (pinfunction "4_4") (pintype "passive"))
      (node (ref "U30") (pin "5") (pinfunction "Q2_5") (pintype "passive"))
    )
    (net (code "38") (name "/DB2") (class "Default")
      (node (ref "P19") (pin "6") (pinfunction "6_6") (pintype "passive"))
      (node (ref "U30") (pin "6") (pinfunction "Q3_6") (pintype "passive"))
    )
    (net (code "39") (name "/DB3") (class "Default")
      (node (ref "P19") (pin "8") (pinfunction "8_8") (pintype "passive"))
      (node (ref "U30") (pin "7") (pinfunction "Q4_7") (pintype "passive"))
    )
    (net (code "40") (name "/DB4") (class "Default")
      (node (ref "P19") (pin "10") (pinfunction "10_10") (pintype "passive"))
      (node (ref "U30") (pin "14") (pinfunction "Q5_14") (pintype "passive"))
    )
    (net (code "41") (name "/DB5") (class "Default")
      (node (ref "P19") (pin "12") (pinfunction "12_12") (pintype "passive"))
      (node (ref "U30") (pin "13") (pinfunction "Q6_13") (pintype "passive"))
    )
    (net (code "42") (name "/DB6") (class "Default")
      (node (ref "P19") (pin "14") (pinfunction "14_14") (pintype "passive"))
      (node (ref "U30") (pin "12") (pinfunction "Q7_12") (pintype "passive"))
    )
    (net (code "43") (name "/DB7") (class "Default")
      (node (ref "P19") (pin "16") (pinfunction "16_16") (pintype "passive"))
      (node (ref "U30") (pin "11") (pinfunction "O8_11") (pintype "passive"))
    )
    (net (code "44") (name "/DB8") (class "Default")
      (node (ref "P19") (pin "13") (pinfunction "13_13") (pintype "passive"))
      (node (ref "U34") (pin "4") (pinfunction "Q1_4") (pintype "passive"))
    )
    (net (code "45") (name "/DB9") (class "Default")
      (node (ref "P19") (pin "15") (pinfunction "15_15") (pintype "passive"))
      (node (ref "U34") (pin "5") (pinfunction "Q2_5") (pintype "passive"))
    )
    (net (code "46") (name "/DB10") (class "Default")
      (node (ref "P19") (pin "17") (pinfunction "17_17") (pintype "passive"))
      (node (ref "U34") (pin "6") (pinfunction "Q3_6") (pintype "passive"))
    )
    (net (code "47") (name "/DB11") (class "Default")
      (node (ref "P19") (pin "19") (pinfunction "19_19") (pintype "passive"))
      (node (ref "U34") (pin "7") (pinfunction "Q4_7") (pintype "passive"))
    )
    (net (code "48") (name "/DB12") (class "Default")
      (node (ref "P19") (pin "21") (pinfunction "21_21") (pintype "passive"))
      (node (ref "U34") (pin "14") (pinfunction "Q5_14") (pintype "passive"))
    )
    (net (code "49") (name "/DB13") (class "Default")
      (node (ref "P19") (pin "23") (pinfunction "23_23") (pintype "passive"))
      (node (ref "U34") (pin "13") (pinfunction "Q6_13") (pintype "passive"))
    )
    (net (code "50") (name "/DB14") (class "Default")
      (node (ref "P19") (pin "25") (pinfunction "25_25") (pintype "passive"))
      (node (ref "U34") (pin "12") (pinfunction "Q7_12") (pintype "passive"))
    )
    (net (code "51") (name "/DB15") (class "Default")
      (node (ref "P19") (pin "27") (pinfunction "27_27") (pintype "passive"))
      (node (ref "U34") (pin "11") (pinfunction "O8_11") (pintype "passive"))
    )
    (net (code "52") (name "/DC") (class "Default")
      (node (ref "P19") (pin "7") (pinfunction "7_7") (pintype "passive"))
      (node (ref "U39") (pin "14") (pinfunction "Q5_14") (pintype "passive"))
    )
    (net (code "53") (name "/G1") (class "Default")
      (node (ref "K7") (pin "11") (pinfunction "11_11") (pintype "passive"))
      (node (ref "K7") (pin "6") (pinfunction "6_6") (pintype "passive"))
      (node (ref "P3") (pin "6") (pinfunction "6_6") (pintype "passive"))
      (node (ref "R63") (pin "1") (pinfunction "1_1") (pintype "passive"))
    )
    (net (code "54") (name "/G2") (class "Default")
      (node (ref "K7") (pin "13") (pinfunction "13_13") (pintype "passive"))
      (node (ref "K7") (pin "4") (pinfunction "4_4") (pintype "passive"))
      (node (ref "P4") (pin "5") (pinfunction "5_5") (pintype "passive"))
      (node (ref "R56") (pin "2") (pinfunction "2_2") (pintype "passive"))
    )
    (net (code "55") (name "/GPIO4") (class "Default")
      (node (ref "P5") (pin "7") (pinfunction "7_7") (pintype "passive"))
      (node (ref "R19") (pin "2") (pinfunction "2_2") (pintype "passive"))
    )
    (net (code "56") (name "/HUM") (class "Default")
      (node (ref "K6") (pin "8") (pinfunction "8_8") (pintype "passive"))
      (node (ref "K6") (pin "9") (pinfunction "9_9") (pintype "passive"))
      (node (ref "P6") (pin "3") (pinfunction "3_3") (pintype "passive"))
    )
    (net (code "57") (name "/Ha") (class "Default")
      (node (ref "K6") (pin "11") (pinfunction "11_11") (pintype "passive"))
      (node (ref "K6") (pin "6") (pinfunction "6_6") (pintype "passive"))
      (node (ref "P6") (pin "1") (pinfunction "1_1") (pintype "passive"))
      (node (ref "R83") (pin "1") (pinfunction "1_1") (pintype "passive"))
    )
    (net (code "58") (name "/Hb") (class "Default")
      (node (ref "K6") (pin "13") (pinfunction "13_13") (pintype "passive"))
      (node (ref "K6") (pin "4") (pinfunction "4_4") (pintype "passive"))
      (node (ref "P6") (pin "2") (pinfunction "2_2") (pintype "passive"))
      (node (ref "R42") (pin "2") (pinfunction "2_2") (pintype "passive"))
    )
    (net (code "59") (name "/INTA") (class "Default")
      (node (ref "R31") (pin "1") (pinfunction "1_1") (pintype "passive"))
      (node (ref "U4") (pin "20") (pinfunction "INTA_20") (pintype "passive"))
    )
    (net (code "60") (name "/INTB") (class "Default")
      (node (ref "R35") (pin "1") (pinfunction "1_1") (pintype "passive"))
      (node (ref "U4") (pin "19") (pinfunction "INTB_19") (pintype "passive"))
    )
    (net (code "61") (name "/LCD_CS") (class "Default")
      (node (ref "P19") (pin "29") (pinfunction "29_29") (pintype "passive"))
      (node (ref "U30") (pin "1") (pinfunction "STROBE_1") (pintype "passive"))
      (node (ref "U34") (pin "1") (pinfunction "STROBE_1") (pintype "passive"))
      (node (ref "U35") (pin "3") (pinfunction "Q5_3") (pintype "passive"))
      (node (ref "U39") (pin "1") (pinfunction "STROBE_1") (pintype "passive"))
    )
    (net (code "62") (name "/LCD_RST") (class "Default")
      (node (ref "P19") (pin "33") (pinfunction "33_33") (pintype "passive"))
      (node (ref "U39") (pin "7") (pinfunction "Q4_7") (pintype "passive"))
    )
    (net (code "63") (name "/LED_BL") (class "Default")
      (node (ref "C93") (pin "1") (pinfunction "2_1") (pintype "passive"))
      (node (ref "P19") (pin "37") (pinfunction "37_37") (pintype "passive"))
      (node (ref "Q9") (pin "3") (pinfunction "C_3") (pintype "passive"))
    )
    (net (code "64") (name "/LVL1") (class "Default")
      (node (ref "U1") (pin "5") (pinfunction "LVL_5") (pintype "passive"))
      (node (ref "U2") (pin "6") (pinfunction "GPB5_6") (pintype "passive"))
    )
    (net (code "65") (name "/LVL2") (class "Default")
      (node (ref "U2") (pin "21") (pinfunction "GPA0_21") (pintype "passive"))
      (node (ref "U3") (pin "5") (pinfunction "LVL_5") (pintype "passive"))
    )
    (net (code "66") (name "/LVL3") (class "Default")
      (node (ref "U2") (pin "24") (pinfunction "GPA3_24") (pintype "passive"))
      (node (ref "U5") (pin "5") (pinfunction "LVL_5") (pintype "passive"))
    )
    (net (code "67") (name "/NO1") (class "Default")
      (node (ref "C17") (pin "1") (pinfunction "1_1") (pintype "passive"))
      (node (ref "K11") (pin "8") (pinfunction "8_8") (pintype "passive"))
      (node (ref "K11") (pin "9") (pinfunction "9_9") (pintype "passive"))
      (node (ref "P7") (pin "1") (pinfunction "VCC_1") (pintype "passive"))
      (node (ref "VR4") (pin "1") (pinfunction "1_1") (pintype "passive"))
    )
    (net (code "68") (name "/NO2") (class "Default")
      (node (ref "C23") (pin "1") (pinfunction "1_1") (pintype "passive"))
      (node (ref "K15") (pin "8") (pinfunction "8_8") (pintype "passive"))
      (node (ref "K15") (pin "9") (pinfunction "9_9") (pintype "passive"))
      (node (ref "P8") (pin "1") (pinfunction "VCC_1") (pintype "passive"))
      (node (ref "VR6") (pin "1") (pinfunction "1_1") (pintype "passive"))
    )
    (net (code "69") (name "/NO3") (class "Default")
      (node (ref "C25") (pin "1") (pinfunction "1_1") (pintype "passive"))
      (node (ref "K19") (pin "8") (pinfunction "8_8") (pintype "passive"))
      (node (ref "K19") (pin "9") (pinfunction "9_9") (pintype "passive"))
      (node (ref "P9") (pin "1") (pinfunction "VCC_1") (pintype "passive"))
      (node (ref "VR8") (pin "1") (pinfunction "1_1") (pintype "passive"))
    )
    (net (code "70") (name "/NO4") (class "Default")
      (node (ref "C29") (pin "1") (pinfunction "1_1") (pintype "passive"))
      (node (ref "K12") (pin "8") (pinfunction "8_8") (pintype "passive"))
      (node (ref "K12") (pin "9") (pinfunction "9_9") (pintype "passive"))
      (node (ref "P11") (pin "1") (pinfunction "VCC_1") (pintype "passive"))
      (node (ref "VR10") (pin "1") (pinfunction "1_1") (pintype "passive"))
    )
    (net (code "71") (name "/NO5") (class "Default")
      (node (ref "C31") (pin "1") (pinfunction "1_1") (pintype "passive"))
      (node (ref "K16") (pin "8") (pinfunction "8_8") (pintype "passive"))
      (node (ref "K16") (pin "9") (pinfunction "9_9") (pintype "passive"))
      (node (ref "P12") (pin "1") (pinfunction "VCC_1") (pintype "passive"))
      (node (ref "VR12") (pin "1") (pinfunction "1_1") (pintype "passive"))
    )
    (net (code "72") (name "/NO6") (class "Default")
      (node (ref "C37") (pin "1") (pinfunction "1_1") (pintype "passive"))
      (node (ref "K20") (pin "8") (pinfunction "8_8") (pintype "passive"))
      (node (ref "K20") (pin "9") (pinfunction "9_9") (pintype "passive"))
      (node (ref "P14") (pin "1") (pinfunction "VCC_1") (pintype "passive"))
      (node (ref "VR14") (pin "1") (pinfunction "1_1") (pintype "passive"))
    )
    (net (code "73") (name "/OB1") (class "Default")
      (node (ref "K9") (pin "11") (pinfunction "11_11") (pintype "passive"))
      (node (ref "K9") (pin "6") (pinfunction "6_6") (pintype "passive"))
      (node (ref "P3") (pin "7") (pinfunction "7_7") (pintype "passive"))
      (node (ref "R78") (pin "1") (pinfunction "1_1") (pintype "passive"))
    )
    (net (code "74") (name "/OB2") (class "Default")
      (node (ref "K9") (pin "13") (pinfunction "13_13") (pintype "passive"))
      (node (ref "K9") (pin "4") (pinfunction "4_4") (pintype "passive"))
      (node (ref "P4") (pin "4") (pinfunction "4_4") (pintype "passive"))
      (node (ref "R61") (pin "2") (pinfunction "2_2") (pintype "passive"))
    )
    (net (code "75") (name "/OUT1_1") (class "Default")
      (node (ref "K2") (pin "16") (pinfunction "16_16") (pintype "passive"))
      (node (ref "U1") (pin "16") (pinfunction "OUT4_16") (pintype "passive"))
    )
    (net (code "76") (name "/OUT1_2") (class "Default")
      (node (ref "K1") (pin "16") (pinfunction "16_16") (pintype "passive"))
      (node (ref "U1") (pin "17") (pinfunction "OUT3_17") (pintype "passive"))
      (node (ref "U27") (pin "2") (pinfunction "A1_2") (pintype "passive"))
    )
    (net (code "77") (name "/OUT1_3") (class "Default")
      (node (ref "K6") (pin "16") (pinfunction "16_16") (pintype "passive"))
      (node (ref "U25") (pin "9") (pinfunction "A8_9") (pintype "passive"))
      (node (ref "U5") (pin "20") (pinfunction "OUT1_20") (pintype "passive"))
    )
    (net (code "78") (name "/OUT2_1") (class "Default")
      (node (ref "K5") (pin "16") (pinfunction "16_16") (pintype "passive"))
      (node (ref "U1") (pin "11") (pinfunction "OUT7_11") (pintype "passive"))
    )
    (net (code "79") (name "/OUT2_2") (class "Default")
      (node (ref "K4") (pin "16") (pinfunction "16_16") (pintype "passive"))
      (node (ref "U1") (pin "14") (pinfunction "OUT5_14") (pintype "passive"))
      (node (ref "U27") (pin "3") (pinfunction "A2_3") (pintype "passive"))
    )
    (net (code "80") (name "/OUT2_3") (class "Default")
      (node (ref "K3") (pin "16") (pinfunction "16_16") (pintype "passive"))
      (node (ref "U1") (pin "20") (pinfunction "OUT1_20") (pintype "passive"))
    )
    (net (code "81") (name "/OUT3_1") (class "Default")
      (node (ref "K8") (pin "16") (pinfunction "16_16") (pintype "passive"))
      (node (ref "U3") (pin "16") (pinfunction "OUT4_16") (pintype "passive"))
    )
    (net (code "82") (name "/OUT3_2") (class "Default")
      (node (ref "K7") (pin "16") (pinfunction "16_16") (pintype "passive"))
      (node (ref "U27") (pin "4") (pinfunction "A3_4") (pintype "passive"))
      (node (ref "U3") (pin "14") (pinfunction "OUT5_14") (pintype "passive"))
    )
    (net (code "83") (name "/OUT3_3") (class "Default")
      (node (ref "K11") (pin "16") (pinfunction "16_16") (pintype "passive"))
      (node (ref "U25") (pin "2") (pinfunction "A1_2") (pintype "passive"))
      (node (ref "U5") (pin "10") (pinfunction "OUT8_10") (pintype "passive"))
    )
    (net (code "84") (name "/OUT4_1") (class "Default")
      (node (ref "K10") (pin "16") (pinfunction "16_16") (pintype "passive"))
      (node (ref "U1") (pin "13") (pinfunction "OUT6_13") (pintype "passive"))
    )
    (net (code "85") (name "/OUT4_2") (class "Default")
      (node (ref "K9") (pin "16") (pinfunction "16_16") (pintype "passive"))
      (node (ref "U1") (pin "19") (pinfunction "OUT2_19") (pintype "passive"))
      (node (ref "U27") (pin "5") (pinfunction "A4_5") (pintype "passive"))
    )
    (net (code "86") (name "/OUT4_3") (class "Default")
      (node (ref "K15") (pin "16") (pinfunction "16_16") (pintype "passive"))
      (node (ref "U25") (pin "3") (pinfunction "A2_3") (pintype "passive"))
      (node (ref "U5") (pin "11") (pinfunction "OUT7_11") (pintype "passive"))
    )
    (net (code "87") (name "/OUT5_1") (class "Default")
      (node (ref "K14") (pin "16") (pinfunction "16_16") (pintype "passive"))
      (node (ref "U3") (pin "19") (pinfunction "OUT2_19") (pintype "passive"))
    )
    (net (code "88") (name "/OUT5_2") (class "Default")
      (node (ref "K13") (pin "16") (pinfunction "16_16") (pintype "passive"))
      (node (ref "U27") (pin "6") (pinfunction "A5_6") (pintype "passive"))
      (node (ref "U3") (pin "17") (pinfunction "OUT3_17") (pintype "passive"))
    )
    (net (code "89") (name "/OUT5_3") (class "Default")
      (node (ref "K19") (pin "16") (pinfunction "16_16") (pintype "passive"))
      (node (ref "U25") (pin "4") (pinfunction "A3_4") (pintype "passive"))
      (node (ref "U5") (pin "13") (pinfunction "OUT6_13") (pintype "passive"))
    )
    (net (code "90") (name "/OUT6_1") (class "Default")
      (node (ref "K18") (pin "16") (pinfunction "16_16") (pintype "passive"))
      (node (ref "U3") (pin "11") (pinfunction "OUT7_11") (pintype "passive"))
    )
    (net (code "91") (name "/OUT6_2") (class "Default")
      (node (ref "K17") (pin "16") (pinfunction "16_16") (pintype "passive"))
      (node (ref "U27") (pin "7") (pinfunction "A6_7") (pintype "passive"))
      (node (ref "U3") (pin "13") (pinfunction "OUT6_13") (pintype "passive"))
    )
    (net (code "92") (name "/OUT6_3") (class "Default")
      (node (ref "K12") (pin "16") (pinfunction "16_16") (pintype "passive"))
      (node (ref "U25") (pin "5") (pinfunction "A4_5") (pintype "passive"))
      (node (ref "U5") (pin "14") (pinfunction "OUT5_14") (pintype "passive"))
    )
    (net (code "93") (name "/OUT7_1") (class "Default")
      (node (ref "K22") (pin "16") (pinfunction "16_16") (pintype "passive"))
      (node (ref "U3") (pin "10") (pinfunction "OUT8_10") (pintype "passive"))
    )
    (net (code "94") (name "/OUT7_2") (class "Default")
      (node (ref "K21") (pin "16") (pinfunction "16_16") (pintype "passive"))
      (node (ref "U27") (pin "8") (pinfunction "A7_8") (pintype "passive"))
      (node (ref "U3") (pin "20") (pinfunction "OUT1_20") (pintype "passive"))
    )
    (net (code "95") (name "/OUT7_3") (class "Default")
      (node (ref "K16") (pin "16") (pinfunction "16_16") (pintype "passive"))
      (node (ref "U25") (pin "6") (pinfunction "A5_6") (pintype "passive"))
      (node (ref "U5") (pin "16") (pinfunction "OUT4_16") (pintype "passive"))
    )
    (net (code "96") (name "/OUT8_3") (class "Default")
      (node (ref "K20") (pin "16") (pinfunction "16_16") (pintype "passive"))
      (node (ref "U25") (pin "7") (pinfunction "A6_7") (pintype "passive"))
      (node (ref "U5") (pin "17") (pinfunction "OUT3_17") (pintype "passive"))
    )
    (net (code "97") (name "/P1") (class "Default")
      (node (ref "P5") (pin "3") (pinfunction "3_3") (pintype "passive"))
      (node (ref "R23") (pin "2") (pinfunction "2_2") (pintype "passive"))
      (node (ref "U12") (pin "1") (pinfunction "CH1_1") (pintype "passive"))
    )
    (net (code "98") (name "/P2") (class "Default")
      (node (ref "P5") (pin "5") (pinfunction "5_5") (pintype "passive"))
      (node (ref "R25") (pin "2") (pinfunction "2_2") (pintype "passive"))
      (node (ref "U12") (pin "3") (pinfunction "CH2_3") (pintype "passive"))
    )
    (net (code "99") (name "/P3") (class "Default")
      (node (ref "P5") (pin "11") (pinfunction "11_11") (pintype "passive"))
      (node (ref "R27") (pin "2") (pinfunction "2_2") (pintype "passive"))
      (node (ref "U12") (pin "4") (pinfunction "CH3_4") (pintype "passive"))
    )
    (net (code "100") (name "/P4") (class "Default")
      (node (ref "P5") (pin "13") (pinfunction "13_13") (pintype "passive"))
      (node (ref "R31") (pin "2") (pinfunction "2_2") (pintype "passive"))
      (node (ref "U12") (pin "6") (pinfunction "CH4_6") (pintype "passive"))
    )
    (net (code "101") (name "/P5") (class "Default")
      (node (ref "P5") (pin "15") (pinfunction "15_15") (pintype "passive"))
      (node (ref "R35") (pin "2") (pinfunction "2_2") (pintype "passive"))
      (node (ref "U17") (pin "1") (pinfunction "CH1_1") (pintype "passive"))
    )
    (net (code "102") (name "/P6") (class "Default")
      (node (ref "P5") (pin "19") (pinfunction "19_19") (pintype "passive"))
      (node (ref "R37") (pin "2") (pinfunction "2_2") (pintype "passive"))
      (node (ref "U17") (pin "3") (pinfunction "CH2_3") (pintype "passive"))
    )
    (net (code "103") (name "/P7") (class "Default")
      (node (ref "P5") (pin "21") (pinfunction "21_21") (pintype "passive"))
      (node (ref "R39") (pin "2") (pinfunction "2_2") (pintype "passive"))
      (node (ref "U17") (pin "4") (pinfunction "CH3_4") (pintype "passive"))
    )
    (net (code "104") (name "/P8") (class "Default")
      (node (ref "P5") (pin "23") (pinfunction "23_23") (pintype "passive"))
      (node (ref "R41") (pin "2") (pinfunction "2_2") (pintype "passive"))
      (node (ref "U17") (pin "6") (pinfunction "CH4_6") (pintype "passive"))
    )
    (net (code "105") (name "/P9") (class "Default")
      (node (ref "P5") (pin "8") (pinfunction "8_8") (pintype "passive"))
      (node (ref "R22") (pin "1") (pinfunction "1_1") (pintype "passive"))
      (node (ref "U13") (pin "1") (pinfunction "CH1_1") (pintype "passive"))
    )
    (net (code "106") (name "/P10") (class "Default")
      (node (ref "P5") (pin "10") (pinfunction "10_10") (pintype "passive"))
      (node (ref "R24") (pin "1") (pinfunction "1_1") (pintype "passive"))
      (node (ref "U13") (pin "3") (pinfunction "CH2_3") (pintype "passive"))
    )
    (net (code "107") (name "/P11") (class "Default")
      (node (ref "P5") (pin "12") (pinfunction "12_12") (pintype "passive"))
      (node (ref "R26") (pin "1") (pinfunction "1_1") (pintype "passive"))
      (node (ref "U13") (pin "4") (pinfunction "CH3_4") (pintype "passive"))
    )
    (net (code "108") (name "/P12") (class "Default")
      (node (ref "P5") (pin "16") (pinfunction "16_16") (pintype "passive"))
      (node (ref "R28") (pin "1") (pinfunction "1_1") (pintype "passive"))
      (node (ref "U13") (pin "6") (pinfunction "CH4_6") (pintype "passive"))
    )
    (net (code "109") (name "/P13") (class "Default")
      (node (ref "P5") (pin "18") (pinfunction "18_18") (pintype "passive"))
      (node (ref "R32") (pin "1") (pinfunction "1_1") (pintype "passive"))
      (node (ref "U18") (pin "1") (pinfunction "CH1_1") (pintype "passive"))
    )
    (net (code "110") (name "/P14") (class "Default")
      (node (ref "P5") (pin "22") (pinfunction "22_22") (pintype "passive"))
      (node (ref "R36") (pin "1") (pinfunction "1_1") (pintype "passive"))
      (node (ref "U18") (pin "3") (pinfunction "CH2_3") (pintype "passive"))
    )
    (net (code "111") (name "/P15") (class "Default")
      (node (ref "P5") (pin "24") (pinfunction "24_24") (pintype "passive"))
      (node (ref "R38") (pin "1") (pinfunction "1_1") (pintype "passive"))
      (node (ref "U18") (pin "4") (pinfunction "CH3_4") (pintype "passive"))
    )
    (net (code "112") (name "/P16") (class "Default")
      (node (ref "P5") (pin "26") (pinfunction "26_26") (pintype "passive"))
      (node (ref "R40") (pin "1") (pinfunction "1_1") (pintype "passive"))
      (node (ref "U18") (pin "6") (pinfunction "CH4_6") (pintype "passive"))
    )
    (net (code "113") (name "/PWM") (class "Default")
      (node (ref "Q10") (pin "1") (pinfunction "B_1") (pintype "passive"))
      (node (ref "R26") (pin "2") (pinfunction "2_2") (pintype "passive"))
    )
    (net (code "114") (name "/R") (class "Default")
      (node (ref "F1") (pin "1") (pinfunction "1_1") (pintype "passive"))
      (node (ref "P21") (pin "1") (pinfunction "VCC_1") (pintype "passive"))
    )
    (net (code "115") (name "/RD") (class "Default")
      (node (ref "P19") (pin "11") (pinfunction "11_11") (pintype "passive"))
      (node (ref "U39") (pin "4") (pinfunction "Q1_4") (pintype "passive"))
    )
    (net (code "116") (name "/REG_CS") (class "Default")
      (node (ref "R38") (pin "2") (pinfunction "2_2") (pintype "passive"))
      (node (ref "U35") (pin "11") (pinfunction "Reset_11") (pintype "passive"))
    )
    (net (code "117") (name "/RELAY_OFF_ST") (class "Default")
      (node (ref "R3") (pin "2") (pinfunction "2_2") (pintype "passive"))
      (node (ref "S2") (pin "3") (pinfunction "3_3") (pintype "passive"))
      (node (ref "U25") (pin "8") (pinfunction "A7_8") (pintype "passive"))
      (node (ref "U4") (pin "5") (pinfunction "GPB4_5") (pintype "passive"))
    )
    (net (code "118") (name "/RESET1") (class "Default")
      (node (ref "D37") (pin "3") (pinfunction "A_3") (pintype "passive"))
      (node (ref "Q6") (pin "3") (pinfunction "C_3") (pintype "passive"))
      (node (ref "R1") (pin "2") (pinfunction "2_2") (pintype "passive"))
      (node (ref "U1") (pin "3") (pinfunction "/RESET_3") (pintype "passive"))
    )
    (net (code "119") (name "/RESET2") (class "Default")
      (node (ref "D38") (pin "3") (pinfunction "A_3") (pintype "passive"))
      (node (ref "Q7") (pin "3") (pinfunction "C_3") (pintype "passive"))
      (node (ref "R9") (pin "2") (pinfunction "2_2") (pintype "passive"))
      (node (ref "U3") (pin "3") (pinfunction "/RESET_3") (pintype "passive"))
    )
    (net (code "120") (name "/RESET3") (class "Default")
      (node (ref "D39") (pin "3") (pinfunction "A_3") (pintype "passive"))
      (node (ref "Q8") (pin "3") (pinfunction "C_3") (pintype "passive"))
      (node (ref "R15") (pin "2") (pinfunction "2_2") (pintype "passive"))
      (node (ref "U5") (pin "3") (pinfunction "/RESET_3") (pintype "passive"))
    )
    (net (code "121") (name "/Rc1") (class "Default")
      (node (ref "K10") (pin "8") (pinfunction "8_8") (pintype "passive"))
      (node (ref "K10") (pin "9") (pinfunction "9_9") (pintype "passive"))
      (node (ref "K14") (pin "8") (pinfunction "8_8") (pintype "passive"))
      (node (ref "K14") (pin "9") (pinfunction "9_9") (pintype "passive"))
      (node (ref "K2") (pin "8") (pinfunction "8_8") (pintype "passive"))
      (node (ref "K2") (pin "9") (pinfunction "9_9") (pintype "passive"))
      (node (ref "K3") (pin "13") (pinfunction "13_13") (pintype "passive"))
      (node (ref "K3") (pin "4") (pinfunction "4_4") (pintype "passive"))
      (node (ref "K5") (pin "8") (pinfunction "8_8") (pintype "passive"))
      (node (ref "K5") (pin "9") (pinfunction "9_9") (pintype "passive"))
      (node (ref "K8") (pin "8") (pinfunction "8_8") (pintype "passive"))
      (node (ref "K8") (pin "9") (pinfunction "9_9") (pintype "passive"))
      (node (ref "P3") (pin "2") (pinfunction "2_2") (pintype "passive"))
      (node (ref "P4") (pin "9") (pinfunction "9_9") (pintype "passive"))
      (node (ref "R49") (pin "1") (pinfunction "1_1") (pintype "passive"))
    )
    (net (code "122") (name "/Rh1") (class "Default")
      (node (ref "K18") (pin "8") (pinfunction "8_8") (pintype "passive"))
      (node (ref "K18") (pin "9") (pinfunction "9_9") (pintype "passive"))
      (node (ref "K22") (pin "8") (pinfunction "8_8") (pintype "passive"))
      (node (ref "K22") (pin "9") (pinfunction "9_9") (pintype "passive"))
      (node (ref "K3") (pin "8") (pinfunction "8_8") (pintype "passive"))
      (node (ref "K3") (pin "9") (pinfunction "9_9") (pintype "passive"))
      (node (ref "P3") (pin "1") (pinfunction "1_1") (pintype "passive"))
      (node (ref "P4") (pin "10") (pinfunction "10_10") (pintype "passive"))
      (node (ref "R34") (pin "1") (pinfunction "1_1") (pintype "passive"))
    )
    (net (code "123") (name "/SCL") (class "Default")
      (node (ref "P15") (pin "5") (pinfunction "SCL_5") (pintype "passive"))
      (node (ref "P16") (pin "3") (pinfunction "3_3") (pintype "passive"))
      (node (ref "R25") (pin "1") (pinfunction "1_1") (pintype "passive"))
      (node (ref "U16") (pin "4") (pinfunction "SCL_4") (pintype "passive"))
      (node (ref "U2") (pin "12") (pinfunction "SCL_12") (pintype "passive"))
      (node (ref "U29") (pin "4") (pinfunction "SCL_4") (pintype "passive"))
      (node (ref "U31") (pin "15") (pinfunction "SCL_15") (pintype "passive"))
      (node (ref "U4") (pin "12") (pinfunction "SCL_12") (pintype "passive"))
      (node (ref "U6") (pin "6") (pinfunction "SCL_6") (pintype "passive"))
    )
    (net (code "124") (name "/SDA") (class "Default")
      (node (ref "P15") (pin "4") (pinfunction "SDA_4") (pintype "passive"))
      (node (ref "P16") (pin "2") (pinfunction "2_2") (pintype "passive"))
      (node (ref "R23") (pin "1") (pinfunction "1_1") (pintype "passive"))
      (node (ref "U16") (pin "5") (pinfunction "SDA_5") (pintype "passive"))
      (node (ref "U2") (pin "13") (pinfunction "SDA_13") (pintype "passive"))
      (node (ref "U29") (pin "5") (pinfunction "SDA_5") (pintype "passive"))
      (node (ref "U31") (pin "14") (pinfunction "SDA_14") (pintype "passive"))
      (node (ref "U4") (pin "13") (pinfunction "SDA_13") (pintype "passive"))
      (node (ref "U6") (pin "5") (pinfunction "SDA_5") (pintype "passive"))
    )
    (net (code "125") (name "/SPI_MISO") (class "Default")
      (node (ref "P1") (pin "4") (pinfunction "4_4") (pintype "passive"))
      (node (ref "P19") (pin "26") (pinfunction "26_26") (pintype "passive"))
      (node (ref "R39") (pin "1") (pinfunction "1_1") (pintype "passive"))
    )
    (net (code "126") (name "/SPI_MOSI") (class "Default")
      (node (ref "P1") (pin "2") (pinfunction "2_2") (pintype "passive"))
      (node (ref "P19") (pin "22") (pinfunction "22_22") (pintype "passive"))
      (node (ref "R37") (pin "1") (pinfunction "1_1") (pintype "passive"))
      (node (ref "U30") (pin "2") (pinfunction "IN_2") (pintype "passive"))
    )
    (net (code "127") (name "/SPI_SCK") (class "Default")
      (node (ref "P1") (pin "6") (pinfunction "6_6") (pintype "passive"))
      (node (ref "P19") (pin "18") (pinfunction "18_18") (pintype "passive"))
      (node (ref "R41") (pin "1") (pinfunction "1_1") (pintype "passive"))
      (node (ref "U30") (pin "3") (pinfunction "CLOCK_3") (pintype "passive"))
      (node (ref "U34") (pin "3") (pinfunction "CLOCK_3") (pintype "passive"))
      (node (ref "U35") (pin "10") (pinfunction "Clock_10") (pintype "passive"))
      (node (ref "U39") (pin "3") (pinfunction "CLOCK_3") (pintype "passive"))
    )
    (net (code "128") (name "/TOUCH_BUSY") (class "Default")
      (node (ref "P19") (pin "24") (pinfunction "24_24") (pintype "passive"))
      (node (ref "R19") (pin "1") (pinfunction "1_1") (pintype "passive"))
    )
    (net (code "129") (name "/TOUCH_CS") (class "Default")
      (node (ref "P19") (pin "20") (pinfunction "20_20") (pintype "passive"))
      (node (ref "R105") (pin "2") (pinfunction "2_2") (pintype "passive"))
      (node (ref "R40") (pin "2") (pinfunction "2_2") (pintype "passive"))
    )
    (net (code "130") (name "/TOUCH_IRQ") (class "Default")
      (node (ref "P19") (pin "28") (pinfunction "28_28") (pintype "passive"))
      (node (ref "R32") (pin "2") (pinfunction "2_2") (pintype "passive"))
    )
    (net (code "131") (name "/UART_RTS") (class "Default")
      (node (ref "P1") (pin "7") (pinfunction "7_7") (pintype "passive"))
      (node (ref "R36") (pin "2") (pinfunction "2_2") (pintype "passive"))
    )
    (net (code "132") (name "/UART_RX") (class "Default")
      (node (ref "P1") (pin "3") (pinfunction "3_3") (pintype "passive"))
      (node (ref "R24") (pin "2") (pinfunction "2_2") (pintype "passive"))
    )
    (net (code "133") (name "/UART_TX") (class "Default")
      (node (ref "P1") (pin "5") (pinfunction "5_5") (pintype "passive"))
      (node (ref "R22") (pin "2") (pinfunction "2_2") (pintype "passive"))
    )
    (net (code "134") (name "/W1{slash}1") (class "Default")
      (node (ref "K17") (pin "11") (pinfunction "11_11") (pintype "passive"))
      (node (ref "K17") (pin "6") (pinfunction "6_6") (pintype "passive"))
      (node (ref "P3") (pin "9") (pinfunction "9_9") (pintype "passive"))
      (node (ref "R64") (pin "1") (pinfunction "1_1") (pintype "passive"))
    )
    (net (code "135") (name "/W1{slash}2") (class "Default")
      (node (ref "K21") (pin "11") (pinfunction "11_11") (pintype "passive"))
      (node (ref "K21") (pin "6") (pinfunction "6_6") (pintype "passive"))
      (node (ref "P3") (pin "10") (pinfunction "10_10") (pintype "passive"))
      (node (ref "R79") (pin "1") (pinfunction "1_1") (pintype "passive"))
    )
    (net (code "136") (name "/W2{slash}1") (class "Default")
      (node (ref "K17") (pin "13") (pinfunction "13_13") (pintype "passive"))
      (node (ref "K17") (pin "4") (pinfunction "4_4") (pintype "passive"))
      (node (ref "P4") (pin "2") (pinfunction "2_2") (pintype "passive"))
      (node (ref "R74") (pin "2") (pinfunction "2_2") (pintype "passive"))
    )
    (net (code "137") (name "/W2{slash}2") (class "Default")
      (node (ref "K21") (pin "13") (pinfunction "13_13") (pintype "passive"))
      (node (ref "K21") (pin "4") (pinfunction "4_4") (pintype "passive"))
      (node (ref "P4") (pin "1") (pinfunction "1_1") (pintype "passive"))
      (node (ref "R43") (pin "2") (pinfunction "2_2") (pintype "passive"))
    )
    (net (code "138") (name "/WR") (class "Default")
      (node (ref "P19") (pin "9") (pinfunction "9_9") (pintype "passive"))
      (node (ref "U39") (pin "5") (pinfunction "Q2_5") (pintype "passive"))
    )
    (net (code "139") (name "/Y1{slash}1") (class "Default")
      (node (ref "K1") (pin "11") (pinfunction "11_11") (pintype "passive"))
      (node (ref "K1") (pin "6") (pinfunction "6_6") (pintype "passive"))
      (node (ref "P3") (pin "4") (pinfunction "4_4") (pintype "passive"))
      (node (ref "R33") (pin "1") (pinfunction "1_1") (pintype "passive"))
    )
    (net (code "140") (name "/Y1{slash}2") (class "Default")
      (node (ref "K4") (pin "11") (pinfunction "11_11") (pintype "passive"))
      (node (ref "K4") (pin "6") (pinfunction "6_6") (pintype "passive"))
      (node (ref "P3") (pin "5") (pinfunction "5_5") (pintype "passive"))
      (node (ref "R48") (pin "1") (pinfunction "1_1") (pintype "passive"))
    )
    (net (code "141") (name "/Y2{slash}1") (class "Default")
      (node (ref "K1") (pin "13") (pinfunction "13_13") (pintype "passive"))
      (node (ref "K1") (pin "4") (pinfunction "4_4") (pintype "passive"))
      (node (ref "P4") (pin "7") (pinfunction "7_7") (pintype "passive"))
      (node (ref "R46") (pin "2") (pinfunction "2_2") (pintype "passive"))
    )
    (net (code "142") (name "/Y2{slash}2") (class "Default")
      (node (ref "K4") (pin "13") (pinfunction "13_13") (pintype "passive"))
      (node (ref "K4") (pin "4") (pinfunction "4_4") (pintype "passive"))
      (node (ref "P4") (pin "6") (pinfunction "6_6") (pintype "passive"))
      (node (ref "R50") (pin "2") (pinfunction "2_2") (pintype "passive"))
    )
    (net (code "143") (name "/ZIGBEE_CS") (class "Default")
      (node (ref "P1") (pin "8") (pinfunction "8_8") (pintype "passive"))
      (node (ref "R13") (pin "2") (pinfunction "2_2") (pintype "passive"))
      (node (ref "U4") (pin "7") (pinfunction "GPB6_7") (pintype "passive"))
    )
    (net (code "144") (name "/ZIGBEE_INT") (class "Default")
      (node (ref "P1") (pin "11") (pinfunction "11_11") (pintype "passive"))
      (node (ref "U4") (pin "6") (pinfunction "GPB5_6") (pintype "passive"))
    )
    (net (code "145") (name "/ZIGBEE_RES") (class "Default")
      (node (ref "P1") (pin "10") (pinfunction "10_10") (pintype "passive"))
      (node (ref "R14") (pin "2") (pinfunction "2_2") (pintype "passive"))
      (node (ref "R27") (pin "1") (pinfunction "1_1") (pintype "passive"))
    )
    (net (code "146") (name "/ZIGBEE_WAKE") (class "Default")
      (node (ref "P1") (pin "13") (pinfunction "13_13") (pintype "passive"))
      (node (ref "U4") (pin "8") (pinfunction "GPB7_8") (pintype "passive"))
    )
    (net (code "147") (name "/ZigBee_IO") (class "Default")
      (node (ref "P1") (pin "9") (pinfunction "9_9") (pintype "passive"))
      (node (ref "R28") (pin "2") (pinfunction "2_2") (pintype "passive"))
    )
    (net (code "148") (name "3.3VCC") (class "Default")
      (node (ref "C1") (pin "1") (pinfunction "2_1") (pintype "passive"))
      (node (ref "C15") (pin "1") (pinfunction "2_1") (pintype "passive"))
      (node (ref "C18") (pin "2") (pinfunction "2_2") (pintype "passive"))
      (node (ref "C19") (pin "2") (pinfunction "2_2") (pintype "passive"))
      (node (ref "C2") (pin "1") (pinfunction "2_1") (pintype "passive"))
      (node (ref "C26") (pin "1") (pinfunction "2_1") (pintype "passive"))
      (node (ref "C27") (pin "2") (pinfunction "2_2") (pintype "passive"))
      (node (ref "C3") (pin "1") (pinfunction "2_1") (pintype "passive"))
      (node (ref "C32") (pin "2") (pinfunction "2_2") (pintype "passive"))
      (node (ref "C33") (pin "2") (pinfunction "2_2") (pintype "passive"))
      (node (ref "C4") (pin "1") (pinfunction "2_1") (pintype "passive"))
      (node (ref "C46") (pin "1") (pinfunction "2_1") (pintype "passive"))
      (node (ref "C47") (pin "1") (pinfunction "2_1") (pintype "passive"))
      (node (ref "C5") (pin "1") (pinfunction "2_1") (pintype "passive"))
      (node (ref "C57") (pin "2") (pinfunction "2_2") (pintype "passive"))
      (node (ref "C59") (pin "1") (pinfunction "2_1") (pintype "passive"))
      (node (ref "C6") (pin "1") (pinfunction "2_1") (pintype "passive"))
      (node (ref "C60") (pin "2") (pinfunction "2_2") (pintype "passive"))
      (node (ref "C66") (pin "2") (pinfunction "2_2") (pintype "passive"))
      (node (ref "C7") (pin "2") (pinfunction "2_2") (pintype "passive"))
      (node (ref "C76") (pin "1") (pinfunction "1_1") (pintype "passive"))
      (node (ref "C77") (pin "1") (pinfunction "1_1") (pintype "passive"))
      (node (ref "C78") (pin "2") (pinfunction "2_2") (pintype "passive"))
      (node (ref "C79") (pin "2") (pinfunction "2_2") (pintype "passive"))
      (node (ref "C81") (pin "2") (pinfunction "2_2") (pintype "passive"))
      (node (ref "D29") (pin "1") (pinfunction "K_1") (pintype "passive"))
      (node (ref "D30") (pin "1") (pinfunction "K_1") (pintype "passive"))
      (node (ref "D31") (pin "1") (pinfunction "K_1") (pintype "passive"))
      (node (ref "D32") (pin "1") (pinfunction "K_1") (pintype "passive"))
      (node (ref "L1") (pin "2") (pinfunction "2_2") (pintype "passive"))
      (node (ref "P1") (pin "1") (pinfunction "1_1") (pintype "passive"))
      (node (ref "P16") (pin "4") (pinfunction "4_4") (pintype "passive"))
      (node (ref "R1") (pin "1") (pinfunction "1_1") (pintype "passive"))
      (node (ref "R10") (pin "1") (pinfunction "1_1") (pintype "passive"))
      (node (ref "R105") (pin "1") (pinfunction "1_1") (pintype "passive"))
      (node (ref "R109") (pin "1") (pinfunction "1_1") (pintype "passive"))
      (node (ref "R11") (pin "2") (pinfunction "2_2") (pintype "passive"))
      (node (ref "R117") (pin "1") (pinfunction "1_1") (pintype "passive"))
      (node (ref "R12") (pin "1") (pinfunction "1_1") (pintype "passive"))
      (node (ref "R124") (pin "2") (pinfunction "2_2") (pintype "passive"))
      (node (ref "R125") (pin "2") (pinfunction "2_2") (pintype "passive"))
      (node (ref "R126") (pin "2") (pinfunction "2_2") (pintype "passive"))
      (node (ref "R13") (pin "1") (pinfunction "1_1") (pintype "passive"))
      (node (ref "R14") (pin "1") (pinfunction "1_1") (pintype "passive"))
      (node (ref "R15") (pin "1") (pinfunction "1_1") (pintype "passive"))
      (node (ref "R16") (pin "1") (pinfunction "1_1") (pintype "passive"))
      (node (ref "R17") (pin "1") (pinfunction "1_1") (pintype "passive"))
      (node (ref "R18") (pin "1") (pinfunction "1_1") (pintype "passive"))
      (node (ref "R2") (pin "1") (pinfunction "1_1") (pintype "passive"))
      (node (ref "R20") (pin "2") (pinfunction "2_2") (pintype "passive"))
      (node (ref "R29") (pin "1") (pinfunction "1_1") (pintype "passive"))
      (node (ref "R3") (pin "1") (pinfunction "1_1") (pintype "passive"))
      (node (ref "R30") (pin "1") (pinfunction "1_1") (pintype "passive"))
      (node (ref "R4") (pin "1") (pinfunction "1_1") (pintype "passive"))
      (node (ref "R44") (pin "1") (pinfunction "1_1") (pintype "passive"))
      (node (ref "R45") (pin "1") (pinfunction "1_1") (pintype "passive"))
      (node (ref "R58") (pin "1") (pinfunction "1_1") (pintype "passive"))
      (node (ref "R59") (pin "1") (pinfunction "1_1") (pintype "passive"))
      (node (ref "R60") (pin "1") (pinfunction "1_1") (pintype "passive"))
      (node (ref "R76") (pin "1") (pinfunction "1_1") (pintype "passive"))
      (node (ref "R77") (pin "1") (pinfunction "1_1") (pintype "passive"))
      (node (ref "R80") (pin "1") (pinfunction "1_1") (pintype "passive"))
      (node (ref "R81") (pin "1") (pinfunction "1_1") (pintype "passive"))
      (node (ref "R9") (pin "1") (pinfunction "1_1") (pintype "passive"))
      (node (ref "U1") (pin "1") (pinfunction "VCC_1") (pintype "passive"))
      (node (ref "U1") (pin "2") (pinfunction "/SET_2") (pintype "passive"))
      (node (ref "U11") (pin "24") (pinfunction "VCC_24") (pintype "passive"))
      (node (ref "U12") (pin "5") (pinfunction "Vp_5") (pintype "passive"))
      (node (ref "U13") (pin "5") (pinfunction "Vp_5") (pintype "passive"))
      (node (ref "U16") (pin "1") (pinfunction "VCC_1") (pintype "passive"))
      (node (ref "U17") (pin "5") (pinfunction "Vp_5") (pintype "passive"))
      (node (ref "U18") (pin "5") (pinfunction "Vp_5") (pintype "passive"))
      (node (ref "U2") (pin "9") (pinfunction "VDD_9") (pintype "passive"))
      (node (ref "U25") (pin "24") (pinfunction "VCC_24") (pintype "passive"))
      (node (ref "U27") (pin "24") (pinfunction "VCC_24") (pintype "passive"))
      (node (ref "U3") (pin "1") (pinfunction "VCC_1") (pintype "passive"))
      (node (ref "U3") (pin "2") (pinfunction "/SET_2") (pintype "passive"))
      (node (ref "U30") (pin "15") (pinfunction "OE_15") (pintype "passive"))
      (node (ref "U30") (pin "16") (pinfunction "VCC_16") (pintype "passive"))
      (node (ref "U31") (pin "11") (pinfunction "AS_11") (pintype "passive"))
      (node (ref "U31") (pin "5") (pinfunction "VDD_5") (pintype "passive"))
      (node (ref "U34") (pin "15") (pinfunction "OE_15") (pintype "passive"))
      (node (ref "U34") (pin "16") (pinfunction "VCC_16") (pintype "passive"))
      (node (ref "U35") (pin "16") (pinfunction "VCC_16") (pintype "passive"))
      (node (ref "U39") (pin "15") (pinfunction "OE_15") (pintype "passive"))
      (node (ref "U39") (pin "16") (pinfunction "VCC_16") (pintype "passive"))
      (node (ref "U4") (pin "15") (pinfunction "A0_15") (pintype "passive"))
      (node (ref "U4") (pin "9") (pinfunction "VDD_9") (pintype "passive"))
      (node (ref "U5") (pin "1") (pinfunction "VCC_1") (pintype "passive"))
      (node (ref "U5") (pin "2") (pinfunction "/SET_2") (pintype "passive"))
      (node (ref "U6") (pin "8") (pinfunction "VCC_8") (pintype "passive"))
    )
    (net (code "149") (name "5VCC") (class "Default")
      (node (ref "C10") (pin "2") (pinfunction "2_2") (pintype "passive"))
      (node (ref "C40") (pin "1") (pinfunction "2_1") (pintype "passive"))
      (node (ref "C41") (pin "2") (pinfunction "2_2") (pintype "passive"))
      (node (ref "C43") (pin "2") (pinfunction "2_2") (pintype "passive"))
      (node (ref "C51") (pin "2") (pinfunction "2_2") (pintype "passive"))
      (node (ref "C53") (pin "1") (pinfunction "2_1") (pintype "passive"))
      (node (ref "C54") (pin "1") (pinfunction "2_1") (pintype "passive"))
      (node (ref "C55") (pin "2") (pinfunction "2_2") (pintype "passive"))
      (node (ref "C61") (pin "1") (pinfunction "2_1") (pintype "passive"))
      (node (ref "C8") (pin "1") (pinfunction "2_1") (pintype "passive"))
      (node (ref "C88") (pin "1") (pinfunction "1_1") (pintype "passive"))
      (node (ref "C9") (pin "1") (pinfunction "2_1") (pintype "passive"))
      (node (ref "D3") (pin "1") (pinfunction "K_1") (pintype "passive"))
      (node (ref "F2") (pin "2") (pinfunction "2_2") (pintype "passive"))
      (node (ref "K1") (pin "1") (pinfunction "1_1") (pintype "passive"))
      (node (ref "K10") (pin "1") (pinfunction "1_1") (pintype "passive"))
      (node (ref "K11") (pin "1") (pinfunction "1_1") (pintype "passive"))
      (node (ref "K12") (pin "1") (pinfunction "1_1") (pintype "passive"))
      (node (ref "K13") (pin "1") (pinfunction "1_1") (pintype "passive"))
      (node (ref "K14") (pin "1") (pinfunction "1_1") (pintype "passive"))
      (node (ref "K15") (pin "1") (pinfunction "1_1") (pintype "passive"))
      (node (ref "K16") (pin "1") (pinfunction "1_1") (pintype "passive"))
      (node (ref "K17") (pin "1") (pinfunction "1_1") (pintype "passive"))
      (node (ref "K18") (pin "1") (pinfunction "1_1") (pintype "passive"))
      (node (ref "K19") (pin "1") (pinfunction "1_1") (pintype "passive"))
      (node (ref "K2") (pin "1") (pinfunction "1_1") (pintype "passive"))
      (node (ref "K20") (pin "1") (pinfunction "1_1") (pintype "passive"))
      (node (ref "K21") (pin "1") (pinfunction "1_1") (pintype "passive"))
      (node (ref "K22") (pin "1") (pinfunction "1_1") (pintype "passive"))
      (node (ref "K3") (pin "1") (pinfunction "1_1") (pintype "passive"))
      (node (ref "K4") (pin "1") (pinfunction "1_1") (pintype "passive"))
      (node (ref "K5") (pin "1") (pinfunction "1_1") (pintype "passive"))
      (node (ref "K6") (pin "1") (pinfunction "1_1") (pintype "passive"))
      (node (ref "K7") (pin "1") (pinfunction "1_1") (pintype "passive"))
      (node (ref "K8") (pin "1") (pinfunction "1_1") (pintype "passive"))
      (node (ref "K9") (pin "1") (pinfunction "1_1") (pintype "passive"))
      (node (ref "L3") (pin "2") (pinfunction "2_2") (pintype "passive"))
      (node (ref "LS1") (pin "1") (pinfunction "1_1") (pintype "passive"))
      (node (ref "P10") (pin "1") (pinfunction "VCC_1") (pintype "passive"))
      (node (ref "P13") (pin "1") (pinfunction "VCC_1") (pintype "passive"))
      (node (ref "P15") (pin "1") (pinfunction "VCC_1") (pintype "passive"))
      (node (ref "P19") (pin "3") (pinfunction "3_3") (pintype "passive"))
      (node (ref "P22") (pin "3") (pinfunction "3_3") (pintype "passive"))
      (node (ref "R113") (pin "1") (pinfunction "1_1") (pintype "passive"))
      (node (ref "R119") (pin "1") (pinfunction "1_1") (pintype "passive"))
      (node (ref "R127") (pin "2") (pinfunction "2_2") (pintype "passive"))
      (node (ref "U1") (pin "15") (pinfunction "COM_15") (pintype "passive"))
      (node (ref "U26") (pin "8") (pinfunction "VCC_8") (pintype "passive"))
      (node (ref "U28") (pin "4") (pinfunction "VCC_4") (pintype "passive"))
      (node (ref "U29") (pin "2") (pinfunction "VDD_2") (pintype "passive"))
      (node (ref "U29") (pin "8") (pinfunction "A_8") (pintype "passive"))
      (node (ref "U3") (pin "15") (pinfunction "COM_15") (pintype "passive"))
      (node (ref "U33") (pin "3") (pinfunction "EN_3") (pintype "passive"))
      (node (ref "U33") (pin "4") (pinfunction "VIN_4") (pintype "passive"))
      (node (ref "U36") (pin "1") (pinfunction "A_1") (pintype "passive"))
      (node (ref "U5") (pin "15") (pinfunction "COM_15") (pintype "passive"))
    )
    (net (code "150") (name "AUDIO_5VCC") (class "Default")
      (node (ref "C85") (pin "1") (pinfunction "1_1") (pintype "passive"))
      (node (ref "C86") (pin "1") (pinfunction "1_1") (pintype "passive"))
      (node (ref "C87") (pin "2") (pinfunction "2_2") (pintype "passive"))
      (node (ref "C91") (pin "1") (pinfunction "2_1") (pintype "passive"))
      (node (ref "C92") (pin "2") (pinfunction "2_2") (pintype "passive"))
      (node (ref "L2") (pin "2") (pinfunction "2_2") (pintype "passive"))
      (node (ref "L3") (pin "1") (pinfunction "1_1") (pintype "passive"))
      (node (ref "R114") (pin "1") (pinfunction "1_1") (pintype "passive"))
      (node (ref "U38") (pin "11") (pinfunction "PVDD_11") (pintype "passive"))
      (node (ref "U38") (pin "12") (pinfunction "PVDD_12") (pintype "passive"))
    )
    (net (code "151") (name "GND") (class "Default")
      (node (ref "BAT1") (pin "2") (pinfunction "2_2") (pintype "passive"))
      (node (ref "C1") (pin "2") (pinfunction "1_2") (pintype "passive"))
      (node (ref "C10") (pin "1") (pinfunction "1_1") (pintype "passive"))
      (node (ref "C11") (pin "2") (pinfunction "1_2") (pintype "passive"))
      (node (ref "C12") (pin "2") (pinfunction "1_2") (pintype "passive"))
      (node (ref "C15") (pin "2") (pinfunction "1_2") (pintype "passive"))
      (node (ref "C18") (pin "1") (pinfunction "1_1") (pintype "passive"))
      (node (ref "C19") (pin "1") (pinfunction "1_1") (pintype "passive"))
      (node (ref "C2") (pin "2") (pinfunction "1_2") (pintype "passive"))
      (node (ref "C20") (pin "2") (pinfunction "1_2") (pintype "passive"))
      (node (ref "C21") (pin "2") (pinfunction "1_2") (pintype "passive"))
      (node (ref "C26") (pin "2") (pinfunction "1_2") (pintype "passive"))
      (node (ref "C27") (pin "1") (pinfunction "1_1") (pintype "passive"))
      (node (ref "C3") (pin "2") (pinfunction "1_2") (pintype "passive"))
      (node (ref "C32") (pin "1") (pinfunction "1_1") (pintype "passive"))
      (node (ref "C33") (pin "1") (pinfunction "1_1") (pintype "passive"))
      (node (ref "C34") (pin "2") (pinfunction "1_2") (pintype "passive"))
      (node (ref "C35") (pin "2") (pinfunction "1_2") (pintype "passive"))
      (node (ref "C38") (pin "2") (pinfunction "1_2") (pintype "passive"))
      (node (ref "C39") (pin "2") (pinfunction "1_2") (pintype "passive"))
      (node (ref "C4") (pin "2") (pinfunction "1_2") (pintype "passive"))
      (node (ref "C40") (pin "2") (pinfunction "1_2") (pintype "passive"))
      (node (ref "C41") (pin "1") (pinfunction "1_1") (pintype "passive"))
      (node (ref "C43") (pin "1") (pinfunction "1_1") (pintype "passive"))
      (node (ref "C44") (pin "2") (pinfunction "2_2") (pintype "passive"))
      (node (ref "C46") (pin "2") (pinfunction "1_2") (pintype "passive"))
      (node (ref "C47") (pin "2") (pinfunction "1_2") (pintype "passive"))
      (node (ref "C48") (pin "2") (pinfunction "1_2") (pintype "passive"))
      (node (ref "C49") (pin "2") (pinfunction "1_2") (pintype "passive"))
      (node (ref "C5") (pin "2") (pinfunction "1_2") (pintype "passive"))
      (node (ref "C51") (pin "1") (pinfunction "1_1") (pintype "passive"))
      (node (ref "C52") (pin "1") (pinfunction "1_1") (pintype "passive"))
      (node (ref "C53") (pin "2") (pinfunction "1_2") (pintype "passive"))
      (node (ref "C54") (pin "2") (pinfunction "1_2") (pintype "passive"))
      (node (ref "C55") (pin "1") (pinfunction "1_1") (pintype "passive"))
      (node (ref "C56") (pin "1") (pinfunction "1_1") (pintype "passive"))
      (node (ref "C57") (pin "1") (pinfunction "1_1") (pintype "passive"))
      (node (ref "C58") (pin "1") (pinfunction "1_1") (pintype "passive"))
      (node (ref "C59") (pin "2") (pinfunction "1_2") (pintype "passive"))
      (node (ref "C6") (pin "2") (pinfunction "1_2") (pintype "passive"))
      (node (ref "C60") (pin "1") (pinfunction "1_1") (pintype "passive"))
      (node (ref "C61") (pin "2") (pinfunction "1_2") (pintype "passive"))
      (node (ref "C64") (pin "1") (pinfunction "1_1") (pintype "passive"))
      (node (ref "C65") (pin "1") (pinfunction "1_1") (pintype "passive"))
      (node (ref "C66") (pin "1") (pinfunction "1_1") (pintype "passive"))
      (node (ref "C67") (pin "1") (pinfunction "1_1") (pintype "passive"))
      (node (ref "C68") (pin "1") (pinfunction "1_1") (pintype "passive"))
      (node (ref "C69") (pin "1") (pinfunction "1_1") (pintype "passive"))
      (node (ref "C7") (pin "1") (pinfunction "1_1") (pintype "passive"))
      (node (ref "C70") (pin "2") (pinfunction "2_2") (pintype "passive"))
      (node (ref "C71") (pin "1") (pinfunction "1_1") (pintype "passive"))
      (node (ref "C76") (pin "2") (pinfunction "2_2") (pintype "passive"))
      (node (ref "C77") (pin "2") (pinfunction "2_2") (pintype "passive"))
      (node (ref "C78") (pin "1") (pinfunction "1_1") (pintype "passive"))
      (node (ref "C79") (pin "1") (pinfunction "1_1") (pintype "passive"))
      (node (ref "C8") (pin "2") (pinfunction "1_2") (pintype "passive"))
      (node (ref "C81") (pin "1") (pinfunction "1_1") (pintype "passive"))
      (node (ref "C83") (pin "2") (pinfunction "2_2") (pintype "passive"))
      (node (ref "C84") (pin "1") (pinfunction "1_1") (pintype "passive"))
      (node (ref "C85") (pin "2") (pinfunction "2_2") (pintype "passive"))
      (node (ref "C86") (pin "2") (pinfunction "2_2") (pintype "passive"))
      (node (ref "C87") (pin "1") (pinfunction "1_1") (pintype "passive"))
      (node (ref "C88") (pin "2") (pinfunction "2_2") (pintype "passive"))
      (node (ref "C89") (pin "2") (pinfunction "2_2") (pintype "passive"))
      (node (ref "C9") (pin "2") (pinfunction "1_2") (pintype "passive"))
      (node (ref "C90") (pin "2") (pinfunction "2_2") (pintype "passive"))
      (node (ref "C91") (pin "2") (pinfunction "1_2") (pintype "passive"))
      (node (ref "C92") (pin "1") (pinfunction "1_1") (pintype "passive"))
      (node (ref "C93") (pin "2") (pinfunction "1_2") (pintype "passive"))
      (node (ref "D1") (pin "2") (pinfunction "K_2") (pintype "passive"))
      (node (ref "D10") (pin "2") (pinfunction "K_2") (pintype "passive"))
      (node (ref "D11") (pin "2") (pinfunction "K_2") (pintype "passive"))
      (node (ref "D12") (pin "2") (pinfunction "K_2") (pintype "passive"))
      (node (ref "D13") (pin "2") (pinfunction "K_2") (pintype "passive"))
      (node (ref "D14") (pin "2") (pinfunction "K_2") (pintype "passive"))
      (node (ref "D15") (pin "2") (pinfunction "K_2") (pintype "passive"))
      (node (ref "D16") (pin "2") (pinfunction "K_2") (pintype "passive"))
      (node (ref "D17") (pin "2") (pinfunction "K_2") (pintype "passive"))
      (node (ref "D18") (pin "2") (pinfunction "K_2") (pintype "passive"))
      (node (ref "D19") (pin "2") (pinfunction "K_2") (pintype "passive"))
      (node (ref "D2") (pin "2") (pinfunction "K_2") (pintype "passive"))
      (node (ref "D20") (pin "2") (pinfunction "K_2") (pintype "passive"))
      (node (ref "D21") (pin "2") (pinfunction "K_2") (pintype "passive"))
      (node (ref "D22") (pin "2") (pinfunction "K_2") (pintype "passive"))
      (node (ref "D23") (pin "2") (pinfunction "K_2") (pintype "passive"))
      (node (ref "D24") (pin "2") (pinfunction "K_2") (pintype "passive"))
      (node (ref "D25") (pin "2") (pinfunction "K_2") (pintype "passive"))
      (node (ref "D26") (pin "2") (pinfunction "K_2") (pintype "passive"))
      (node (ref "D27") (pin "2") (pinfunction "K_2") (pintype "passive"))
      (node (ref "D28") (pin "2") (pinfunction "K_2") (pintype "passive"))
      (node (ref "D33") (pin "3") (pinfunction "A_3") (pintype "passive"))
      (node (ref "D34") (pin "3") (pinfunction "A_3") (pintype "passive"))
      (node (ref "D35") (pin "3") (pinfunction "A_3") (pintype "passive"))
      (node (ref "D36") (pin "3") (pinfunction "A_3") (pintype "passive"))
      (node (ref "D4") (pin "2") (pinfunction "K_2") (pintype "passive"))
      (node (ref "D5") (pin "2") (pinfunction "K_2") (pintype "passive"))
      (node (ref "D6") (pin "2") (pinfunction "K_2") (pintype "passive"))
      (node (ref "D7") (pin "2") (pinfunction "K_2") (pintype "passive"))
      (node (ref "D8") (pin "2") (pinfunction "K_2") (pintype "passive"))
      (node (ref "D9") (pin "2") (pinfunction "K_2") (pintype "passive"))
      (node (ref "J1") (pin "1") (pinfunction "S_1") (pintype "power_in"))
      (node (ref "P1") (pin "14") (pinfunction "14_14") (pintype "passive"))
      (node (ref "P10") (pin "3") (pinfunction "GND_3") (pintype "passive"))
      (node (ref "P13") (pin "3") (pinfunction "GND_3") (pintype "passive"))
      (node (ref "P15") (pin "3") (pinfunction "GND_3") (pintype "passive"))
      (node (ref "P16") (pin "1") (pinfunction "1_1") (pintype "passive"))
      (node (ref "P17") (pin "2") (pinfunction "GND_2") (pintype "passive"))
      (node (ref "P18") (pin "2") (pinfunction "GND_2") (pintype "passive"))
      (node (ref "P19") (pin "1") (pinfunction "1_1") (pintype "passive"))
      (node (ref "P20") (pin "2") (pinfunction "GND_2") (pintype "passive"))
      (node (ref "P22") (pin "7") (pinfunction "7_7") (pintype "passive"))
      (node (ref "P23") (pin "2") (pinfunction "GND_2") (pintype "passive"))
      (node (ref "P24") (pin "2") (pinfunction "GND_2") (pintype "passive"))
      (node (ref "P5") (pin "14") (pinfunction "14_14") (pintype "passive"))
      (node (ref "P5") (pin "20") (pinfunction "20_20") (pintype "passive"))
      (node (ref "P5") (pin "25") (pinfunction "25_25") (pintype "passive"))
      (node (ref "P5") (pin "6") (pinfunction "6_6") (pintype "passive"))
      (node (ref "P5") (pin "9") (pinfunction "9_9") (pintype "passive"))
      (node (ref "Q1") (pin "3") (pinfunction "D_3") (pintype "passive"))
      (node (ref "Q10") (pin "2") (pinfunction "E_2") (pintype "passive"))
      (node (ref "Q6") (pin "2") (pinfunction "E_2") (pintype "passive"))
      (node (ref "Q7") (pin "2") (pinfunction "E_2") (pintype "passive"))
      (node (ref "Q8") (pin "2") (pinfunction "E_2") (pintype "passive"))
      (node (ref "R104") (pin "2") (pinfunction "2_2") (pintype "passive"))
      (node (ref "R107") (pin "2") (pinfunction "2_2") (pintype "passive"))
      (node (ref "R110") (pin "1") (pinfunction "1_1") (pintype "passive"))
      (node (ref "R112") (pin "1") (pinfunction "1_1") (pintype "passive"))
      (node (ref "R115") (pin "1") (pinfunction "1_1") (pintype "passive"))
      (node (ref "R116") (pin "2") (pinfunction "2_2") (pintype "passive"))
      (node (ref "R121") (pin "1") (pinfunction "1_1") (pintype "passive"))
      (node (ref "R122") (pin "2") (pinfunction "2_2") (pintype "passive"))
      (node (ref "R123") (pin "1") (pinfunction "1_1") (pintype "passive"))
      (node (ref "R95") (pin "2") (pinfunction "2_2") (pintype "passive"))
      (node (ref "S2") (pin "2") (pinfunction "2_2") (pintype "passive"))
      (node (ref "U1") (pin "12") (pinfunction "PGND_12") (pintype "passive"))
      (node (ref "U1") (pin "18") (pinfunction "PGND_18") (pintype "passive"))
      (node (ref "U1") (pin "9") (pinfunction "GND_9") (pintype "passive"))
      (node (ref "U10") (pin "3") (pinfunction "EMITTER_3") (pintype "passive"))
      (node (ref "U11") (pin "1") (pinfunction "/OE1_1") (pintype "passive"))
      (node (ref "U11") (pin "12") (pinfunction "GND_12") (pintype "passive"))
      (node (ref "U11") (pin "13") (pinfunction "/OE2_13") (pintype "passive"))
      (node (ref "U12") (pin "2") (pinfunction "Vn_2") (pintype "passive"))
      (node (ref "U13") (pin "2") (pinfunction "Vn_2") (pintype "passive"))
      (node (ref "U14") (pin "3") (pinfunction "EMITTER_3") (pintype "passive"))
      (node (ref "U15") (pin "3") (pinfunction "EMITTER_3") (pintype "passive"))
      (node (ref "U16") (pin "3") (pinfunction "GND_3") (pintype "passive"))
      (node (ref "U16") (pin "7") (pinfunction "AD1_7") (pintype "passive"))
      (node (ref "U16") (pin "8") (pinfunction "AD0_8") (pintype "passive"))
      (node (ref "U17") (pin "2") (pinfunction "Vn_2") (pintype "passive"))
      (node (ref "U18") (pin "2") (pinfunction "Vn_2") (pintype "passive"))
      (node (ref "U19") (pin "3") (pinfunction "EMITTER_3") (pintype "passive"))
      (node (ref "U2") (pin "10") (pinfunction "VSS_10") (pintype "passive"))
      (node (ref "U2") (pin "15") (pinfunction "A0_15") (pintype "passive"))
      (node (ref "U2") (pin "16") (pinfunction "A1_16") (pintype "passive"))
      (node (ref "U2") (pin "17") (pinfunction "A2_17") (pintype "passive"))
      (node (ref "U20") (pin "3") (pinfunction "EMITTER_3") (pintype "passive"))
      (node (ref "U21") (pin "3") (pinfunction "EMITTER_3") (pintype "passive"))
      (node (ref "U22") (pin "3") (pinfunction "EMITTER_3") (pintype "passive"))
      (node (ref "U25") (pin "1") (pinfunction "/OE1_1") (pintype "passive"))
      (node (ref "U25") (pin "12") (pinfunction "GND_12") (pintype "passive"))
      (node (ref "U25") (pin "13") (pinfunction "/OE2_13") (pintype "passive"))
      (node (ref "U26") (pin "4") (pinfunction "GND_4") (pintype "passive"))
      (node (ref "U27") (pin "1") (pinfunction "/OE1_1") (pintype "passive"))
      (node (ref "U27") (pin "12") (pinfunction "GND_12") (pintype "passive"))
      (node (ref "U27") (pin "13") (pinfunction "/OE2_13") (pintype "passive"))
      (node (ref "U28") (pin "11") (pinfunction "GND_11") (pintype "passive"))
      (node (ref "U29") (pin "3") (pinfunction "GND_3") (pintype "passive"))
      (node (ref "U29") (pin "6") (pinfunction "AD0_6") (pintype "passive"))
      (node (ref "U29") (pin "7") (pinfunction "B_7") (pintype "passive"))
      (node (ref "U3") (pin "12") (pinfunction "PGND_12") (pintype "passive"))
      (node (ref "U3") (pin "18") (pinfunction "PGND_18") (pintype "passive"))
      (node (ref "U3") (pin "9") (pinfunction "GND_9") (pintype "passive"))
      (node (ref "U30") (pin "8") (pinfunction "GND_8") (pintype "passive"))
      (node (ref "U31") (pin "1") (pinfunction "AGND_1") (pintype "passive"))
      (node (ref "U31") (pin "16") (pinfunction "AGND_16") (pintype "passive"))
      (node (ref "U31") (pin "2") (pinfunction "AGND_2") (pintype "passive"))
      (node (ref "U31") (pin "3") (pinfunction "AGND_3") (pintype "passive"))
      (node (ref "U31") (pin "4") (pinfunction "AGND_4") (pintype "passive"))
      (node (ref "U32") (pin "3") (pinfunction "GND_3") (pintype "passive"))
      (node (ref "U32") (pin "5") (pinfunction "/ON_5") (pintype "passive"))
      (node (ref "U32") (pin "6") (pinfunction "_GND_6") (pintype "passive"))
      (node (ref "U33") (pin "2") (pinfunction "GND_2") (pintype "passive"))
      (node (ref "U34") (pin "8") (pinfunction "GND_8") (pintype "passive"))
      (node (ref "U35") (pin "8") (pinfunction "GND_8") (pintype "passive"))
      (node (ref "U37") (pin "3") (pinfunction "GND_3") (pintype "passive"))
      (node (ref "U37") (pin "5") (pinfunction "/ON_5") (pintype "passive"))
      (node (ref "U37") (pin "6") (pinfunction "_GND_6") (pintype "passive"))
      (node (ref "U38") (pin "1") (pinfunction "PGND_1") (pintype "passive"))
      (node (ref "U38") (pin "15") (pinfunction "_GND_15") (pintype "passive"))
      (node (ref "U38") (pin "8") (pinfunction "PGND_8") (pintype "passive"))
      (node (ref "U39") (pin "8") (pinfunction "GND_8") (pintype "passive"))
      (node (ref "U4") (pin "10") (pinfunction "VSS_10") (pintype "passive"))
      (node (ref "U4") (pin "16") (pinfunction "A1_16") (pintype "passive"))
      (node (ref "U4") (pin "17") (pinfunction "A2_17") (pintype "passive"))
      (node (ref "U5") (pin "12") (pinfunction "PGND_12") (pintype "passive"))
      (node (ref "U5") (pin "18") (pinfunction "PGND_18") (pintype "passive"))
      (node (ref "U5") (pin "9") (pinfunction "GND_9") (pintype "passive"))
      (node (ref "U6") (pin "4") (pinfunction "GND_4") (pintype "passive"))
      (node (ref "U7") (pin "3") (pinfunction "EMITTER_3") (pintype "passive"))
      (node (ref "U8") (pin "3") (pinfunction "EMITTER_3") (pintype "passive"))
      (node (ref "U9") (pin "3") (pinfunction "EMITTER_3") (pintype "passive"))
    )
    (net (code "152") (name "Net-(C13-Pad2)") (class "Default")
      (node (ref "C13") (pin "2") (pinfunction "2_2") (pintype "passive"))
      (node (ref "R42") (pin "1") (pinfunction "1_1") (pintype "passive"))
      (node (ref "VR1") (pin "2") (pinfunction "2_2") (pintype "passive"))
    )
    (net (code "153") (name "Net-(C14-Pad2)") (class "Default")
      (node (ref "C14") (pin "2") (pinfunction "2_2") (pintype "passive"))
      (node (ref "R43") (pin "1") (pinfunction "1_1") (pintype "passive"))
      (node (ref "VR2") (pin "2") (pinfunction "2_2") (pintype "passive"))
    )
    (net (code "154") (name "Net-(C16-Pad2)") (class "Default")
      (node (ref "C16") (pin "2") (pinfunction "2_2") (pintype "passive"))
      (node (ref "R46") (pin "1") (pinfunction "1_1") (pintype "passive"))
      (node (ref "VR3") (pin "2") (pinfunction "2_2") (pintype "passive"))
    )
    (net (code "155") (name "Net-(C17-Pad2)") (class "Default")
      (node (ref "C17") (pin "2") (pinfunction "2_2") (pintype "passive"))
      (node (ref "R47") (pin "1") (pinfunction "1_1") (pintype "passive"))
      (node (ref "VR4") (pin "2") (pinfunction "2_2") (pintype "passive"))
    )
    (net (code "156") (name "Net-(C22-Pad2)") (class "Default")
      (node (ref "C22") (pin "2") (pinfunction "2_2") (pintype "passive"))
      (node (ref "R50") (pin "1") (pinfunction "1_1") (pintype "passive"))
      (node (ref "VR5") (pin "2") (pinfunction "2_2") (pintype "passive"))
    )
    (net (code "157") (name "Net-(C23-Pad2)") (class "Default")
      (node (ref "C23") (pin "2") (pinfunction "2_2") (pintype "passive"))
      (node (ref "R51") (pin "1") (pinfunction "1_1") (pintype "passive"))
      (node (ref "VR6") (pin "2") (pinfunction "2_2") (pintype "passive"))
    )
    (net (code "158") (name "Net-(C24-Pad2)") (class "Default")
      (node (ref "C24") (pin "2") (pinfunction "2_2") (pintype "passive"))
      (node (ref "R56") (pin "1") (pinfunction "1_1") (pintype "passive"))
      (node (ref "VR7") (pin "2") (pinfunction "2_2") (pintype "passive"))
    )
    (net (code "159") (name "Net-(C25-Pad2)") (class "Default")
      (node (ref "C25") (pin "2") (pinfunction "2_2") (pintype "passive"))
      (node (ref "R57") (pin "1") (pinfunction "1_1") (pintype "passive"))
      (node (ref "VR8") (pin "2") (pinfunction "2_2") (pintype "passive"))
    )
    (net (code "160") (name "Net-(C28-Pad2)") (class "Default")
      (node (ref "C28") (pin "2") (pinfunction "2_2") (pintype "passive"))
      (node (ref "R61") (pin "1") (pinfunction "1_1") (pintype "passive"))
      (node (ref "VR9") (pin "2") (pinfunction "2_2") (pintype "passive"))
    )
    (net (code "161") (name "Net-(C29-Pad2)") (class "Default")
      (node (ref "C29") (pin "2") (pinfunction "2_2") (pintype "passive"))
      (node (ref "R62") (pin "1") (pinfunction "1_1") (pintype "passive"))
      (node (ref "VR10") (pin "2") (pinfunction "2_2") (pintype "passive"))
    )
    (net (code "162") (name "Net-(C30-Pad2)") (class "Default")
      (node (ref "C30") (pin "2") (pinfunction "2_2") (pintype "passive"))
      (node (ref "R65") (pin "1") (pinfunction "1_1") (pintype "passive"))
      (node (ref "VR11") (pin "2") (pinfunction "2_2") (pintype "passive"))
    )
    (net (code "163") (name "Net-(C31-Pad2)") (class "Default")
      (node (ref "C31") (pin "2") (pinfunction "2_2") (pintype "passive"))
      (node (ref "R66") (pin "1") (pinfunction "1_1") (pintype "passive"))
      (node (ref "VR12") (pin "2") (pinfunction "2_2") (pintype "passive"))
    )
    (net (code "164") (name "Net-(C36-Pad2)") (class "Default")
      (node (ref "C36") (pin "2") (pinfunction "2_2") (pintype "passive"))
      (node (ref "R74") (pin "1") (pinfunction "1_1") (pintype "passive"))
      (node (ref "VR13") (pin "2") (pinfunction "2_2") (pintype "passive"))
    )
    (net (code "165") (name "Net-(C37-Pad2)") (class "Default")
      (node (ref "C37") (pin "2") (pinfunction "2_2") (pintype "passive"))
      (node (ref "R75") (pin "1") (pinfunction "1_1") (pintype "passive"))
      (node (ref "VR14") (pin "2") (pinfunction "2_2") (pintype "passive"))
    )
    (net (code "166") (name "Net-(D1-A)") (class "Default")
      (node (ref "D1") (pin "1") (pinfunction "A_1") (pintype "passive"))
      (node (ref "R7") (pin "2") (pinfunction "2_2") (pintype "passive"))
    )
    (net (code "167") (name "Net-(D2-A)") (class "Default")
      (node (ref "D2") (pin "1") (pinfunction "A_1") (pintype "passive"))
      (node (ref "R8") (pin "2") (pinfunction "2_2") (pintype "passive"))
    )
    (net (code "168") (name "Net-(D3-A)") (class "Default")
      (node (ref "D3") (pin "3") (pinfunction "A_3") (pintype "passive"))
      (node (ref "LS1") (pin "2") (pinfunction "2_2") (pintype "passive"))
      (node (ref "Q1") (pin "2") (pinfunction "S_2") (pintype "passive"))
    )
    (net (code "169") (name "Net-(D4-A)") (class "Default")
      (node (ref "D4") (pin "1") (pinfunction "A_1") (pintype "passive"))
      (node (ref "R52") (pin "1") (pinfunction "1_1") (pintype "passive"))
    )
    (net (code "170") (name "Net-(D5-A)") (class "Default")
      (node (ref "D5") (pin "1") (pinfunction "A_1") (pintype "passive"))
      (node (ref "R53") (pin "1") (pinfunction "1_1") (pintype "passive"))
    )
    (net (code "171") (name "Net-(D6-A)") (class "Default")
      (node (ref "D6") (pin "1") (pinfunction "A_1") (pintype "passive"))
      (node (ref "R54") (pin "1") (pinfunction "1_1") (pintype "passive"))
    )
    (net (code "172") (name "Net-(D7-A)") (class "Default")
      (node (ref "D7") (pin "1") (pinfunction "A_1") (pintype "passive"))
      (node (ref "R55") (pin "1") (pinfunction "1_1") (pintype "passive"))
    )
    (net (code "173") (name "Net-(D8-A)") (class "Default")
      (node (ref "D8") (pin "1") (pinfunction "A_1") (pintype "passive"))
      (node (ref "R67") (pin "2") (pinfunction "2_2") (pintype "passive"))
    )
    (net (code "174") (name "Net-(D9-A)") (class "Default")
      (node (ref "D9") (pin "1") (pinfunction "A_1") (pintype "passive"))
      (node (ref "R68") (pin "2") (pinfunction "2_2") (pintype "passive"))
    )
    (net (code "175") (name "Net-(D10-A)") (class "Default")
      (node (ref "D10") (pin "1") (pinfunction "A_1") (pintype "passive"))
      (node (ref "R69") (pin "2") (pinfunction "2_2") (pintype "passive"))
    )
    (net (code "176") (name "Net-(D11-A)") (class "Default")
      (node (ref "D11") (pin "1") (pinfunction "A_1") (pintype "passive"))
      (node (ref "R70") (pin "2") (pinfunction "2_2") (pintype "passive"))
    )
    (net (code "177") (name "Net-(D12-A)") (class "Default")
      (node (ref "D12") (pin "1") (pinfunction "A_1") (pintype "passive"))
      (node (ref "R71") (pin "2") (pinfunction "2_2") (pintype "passive"))
    )
    (net (code "178") (name "Net-(D13-A)") (class "Default")
      (node (ref "D13") (pin "1") (pinfunction "A_1") (pintype "passive"))
      (node (ref "R72") (pin "2") (pinfunction "2_2") (pintype "passive"))
    )
    (net (code "179") (name "Net-(D14-A)") (class "Default")
      (node (ref "D14") (pin "1") (pinfunction "A_1") (pintype "passive"))
      (node (ref "R84") (pin "1") (pinfunction "1_1") (pintype "passive"))
    )
    (net (code "180") (name "Net-(D15-A)") (class "Default")
      (node (ref "D15") (pin "1") (pinfunction "A_1") (pintype "passive"))
      (node (ref "R85") (pin "1") (pinfunction "1_1") (pintype "passive"))
    )
    (net (code "181") (name "Net-(D16-A)") (class "Default")
      (node (ref "D16") (pin "1") (pinfunction "A_1") (pintype "passive"))
      (node (ref "R86") (pin "1") (pinfunction "1_1") (pintype "passive"))
    )
    (net (code "182") (name "Net-(D17-A)") (class "Default")
      (node (ref "D17") (pin "1") (pinfunction "A_1") (pintype "passive"))
      (node (ref "R87") (pin "1") (pinfunction "1_1") (pintype "passive"))
    )
    (net (code "183") (name "Net-(D18-A)") (class "Default")
      (node (ref "D18") (pin "1") (pinfunction "A_1") (pintype "passive"))
      (node (ref "R88") (pin "1") (pinfunction "1_1") (pintype "passive"))
    )
    (net (code "184") (name "Net-(D19-A)") (class "Default")
      (node (ref "D19") (pin "1") (pinfunction "A_1") (pintype "passive"))
      (node (ref "R89") (pin "1") (pinfunction "1_1") (pintype "passive"))
    )
    (net (code "185") (name "Net-(D20-A)") (class "Default")
      (node (ref "D20") (pin "1") (pinfunction "A_1") (pintype "passive"))
      (node (ref "R90") (pin "1") (pinfunction "1_1") (pintype "passive"))
    )
    (net (code "186") (name "Net-(D21-A)") (class "Default")
      (node (ref "D21") (pin "1") (pinfunction "A_1") (pintype "passive"))
      (node (ref "R91") (pin "1") (pinfunction "1_1") (pintype "passive"))
    )
    (net (code "187") (name "Net-(D22-A)") (class "Default")
      (node (ref "D22") (pin "1") (pinfunction "A_1") (pintype "passive"))
      (node (ref "R96") (pin "2") (pinfunction "2_2") (pintype "passive"))
    )
    (net (code "188") (name "Net-(D23-A)") (class "Default")
      (node (ref "D23") (pin "1") (pinfunction "A_1") (pintype "passive"))
      (node (ref "R97") (pin "2") (pinfunction "2_2") (pintype "passive"))
    )
    (net (code "189") (name "Net-(D24-A)") (class "Default")
      (node (ref "D24") (pin "1") (pinfunction "A_1") (pintype "passive"))
      (node (ref "R100") (pin "2") (pinfunction "2_2") (pintype "passive"))
    )
    (net (code "190") (name "Net-(D25-A)") (class "Default")
      (node (ref "D25") (pin "1") (pinfunction "A_1") (pintype "passive"))
      (node (ref "R101") (pin "2") (pinfunction "2_2") (pintype "passive"))
    )
    (net (code "191") (name "Net-(D26-A)") (class "Default")
      (node (ref "D26") (pin "1") (pinfunction "A_1") (pintype "passive"))
      (node (ref "R98") (pin "2") (pinfunction "2_2") (pintype "passive"))
    )
    (net (code "192") (name "Net-(D27-A)") (class "Default")
      (node (ref "D27") (pin "1") (pinfunction "A_1") (pintype "passive"))
      (node (ref "R99") (pin "2") (pinfunction "2_2") (pintype "passive"))
    )
    (net (code "193") (name "Net-(D28-A)") (class "Default")
      (node (ref "D28") (pin "1") (pinfunction "A_1") (pintype "passive"))
      (node (ref "R102") (pin "2") (pinfunction "2_2") (pintype "passive"))
    )
    (net (code "194") (name "Net-(D33-K)") (class "Default")
      (node (ref "D33") (pin "1") (pinfunction "K_1") (pintype "passive"))
      (node (ref "L1") (pin "1") (pinfunction "1_1") (pintype "passive"))
      (node (ref "U32") (pin "2") (pinfunction "OUT_2") (pintype "passive"))
    )
    (net (code "195") (name "Net-(D34-C-Pad2)") (class "Default")
      (node (ref "D34") (pin "2") (pinfunction "C_2") (pintype "passive"))
      (node (ref "F1") (pin "2") (pinfunction "2_2") (pintype "passive"))
    )
    (net (code "196") (name "Net-(D34-C-Pad4)") (class "Default")
      (node (ref "D34") (pin "4") (pinfunction "C_4") (pintype "passive"))
      (node (ref "RT1") (pin "2") (pinfunction "2_2") (pintype "passive"))
    )
    (net (code "197") (name "Net-(D34-K)") (class "Default")
      (node (ref "C70") (pin "1") (pinfunction "1_1") (pintype "passive"))
      (node (ref "C71") (pin "2") (pinfunction "2_2") (pintype "passive"))
      (node (ref "C83") (pin "1") (pinfunction "1_1") (pintype "passive"))
      (node (ref "C84") (pin "2") (pinfunction "2_2") (pintype "passive"))
      (node (ref "D34") (pin "1") (pinfunction "K_1") (pintype "passive"))
      (node (ref "D35") (pin "1") (pinfunction "K_1") (pintype "passive"))
      (node (ref "P23") (pin "1") (pinfunction "VCC_1") (pintype "passive"))
      (node (ref "P24") (pin "1") (pinfunction "VCC_1") (pintype "passive"))
      (node (ref "U32") (pin "1") (pinfunction "Vin_1") (pintype "passive"))
      (node (ref "U37") (pin "1") (pinfunction "Vin_1") (pintype "passive"))
    )
    (net (code "198") (name "Net-(D36-K)") (class "Default")
      (node (ref "D36") (pin "1") (pinfunction "K_1") (pintype "passive"))
      (node (ref "L2") (pin "1") (pinfunction "1_1") (pintype "passive"))
      (node (ref "U37") (pin "2") (pinfunction "OUT_2") (pintype "passive"))
    )
    (net (code "199") (name "Net-(D37-K)") (class "Default")
      (node (ref "D37") (pin "1") (pinfunction "K_1") (pintype "passive"))
      (node (ref "U2") (pin "4") (pinfunction "GPB3_4") (pintype "passive"))
    )
    (net (code "200") (name "Net-(D38-K)") (class "Default")
      (node (ref "D38") (pin "1") (pinfunction "K_1") (pintype "passive"))
      (node (ref "U2") (pin "7") (pinfunction "GPB6_7") (pintype "passive"))
    )
    (net (code "201") (name "Net-(D39-K)") (class "Default")
      (node (ref "D39") (pin "1") (pinfunction "K_1") (pintype "passive"))
      (node (ref "U2") (pin "22") (pinfunction "GPA1_22") (pintype "passive"))
    )
    (net (code "202") (name "Net-(F2-Pad1)") (class "Default")
      (node (ref "F2") (pin "1") (pinfunction "1_1") (pintype "passive"))
      (node (ref "P5") (pin "2") (pinfunction "2_2") (pintype "passive"))
      (node (ref "P5") (pin "4") (pinfunction "4_4") (pintype "passive"))
    )
    (net (code "203") (name "Net-(J1-R)") (class "Default")
      (node (ref "C82") (pin "2") (pinfunction "2_2") (pintype "passive"))
      (node (ref "J1") (pin "3") (pinfunction "R_3") (pintype "input"))
    )
    (net (code "204") (name "Net-(J1-T)") (class "Default")
      (node (ref "C80") (pin "2") (pinfunction "2_2") (pintype "passive"))
      (node (ref "J1") (pin "2") (pinfunction "T_2") (pintype "input"))
    )
    (net (code "205") (name "Net-(K1-Pad8)") (class "Default")
      (node (ref "K1") (pin "8") (pinfunction "8_8") (pintype "passive"))
      (node (ref "K1") (pin "9") (pinfunction "9_9") (pintype "passive"))
      (node (ref "K2") (pin "13") (pinfunction "13_13") (pintype "passive"))
      (node (ref "K2") (pin "4") (pinfunction "4_4") (pintype "passive"))
    )
    (net (code "206") (name "Net-(K4-Pad8)") (class "Default")
      (node (ref "K4") (pin "8") (pinfunction "8_8") (pintype "passive"))
      (node (ref "K4") (pin "9") (pinfunction "9_9") (pintype "passive"))
      (node (ref "K5") (pin "13") (pinfunction "13_13") (pintype "passive"))
      (node (ref "K5") (pin "4") (pinfunction "4_4") (pintype "passive"))
    )
    (net (code "207") (name "Net-(K7-Pad8)") (class "Default")
      (node (ref "K7") (pin "8") (pinfunction "8_8") (pintype "passive"))
      (node (ref "K7") (pin "9") (pinfunction "9_9") (pintype "passive"))
      (node (ref "K8") (pin "13") (pinfunction "13_13") (pintype "passive"))
      (node (ref "K8") (pin "4") (pinfunction "4_4") (pintype "passive"))
    )
    (net (code "208") (name "Net-(K10-Pad13)") (class "Default")
      (node (ref "K10") (pin "13") (pinfunction "13_13") (pintype "passive"))
      (node (ref "K10") (pin "4") (pinfunction "4_4") (pintype "passive"))
      (node (ref "K9") (pin "8") (pinfunction "8_8") (pintype "passive"))
      (node (ref "K9") (pin "9") (pinfunction "9_9") (pintype "passive"))
    )
    (net (code "209") (name "Net-(K13-Pad8)") (class "Default")
      (node (ref "K13") (pin "8") (pinfunction "8_8") (pintype "passive"))
      (node (ref "K13") (pin "9") (pinfunction "9_9") (pintype "passive"))
      (node (ref "K14") (pin "13") (pinfunction "13_13") (pintype "passive"))
      (node (ref "K14") (pin "4") (pinfunction "4_4") (pintype "passive"))
    )
    (net (code "210") (name "Net-(K17-Pad8)") (class "Default")
      (node (ref "K17") (pin "8") (pinfunction "8_8") (pintype "passive"))
      (node (ref "K17") (pin "9") (pinfunction "9_9") (pintype "passive"))
      (node (ref "K18") (pin "13") (pinfunction "13_13") (pintype "passive"))
      (node (ref "K18") (pin "4") (pinfunction "4_4") (pintype "passive"))
    )
    (net (code "211") (name "Net-(K21-Pad8)") (class "Default")
      (node (ref "K21") (pin "8") (pinfunction "8_8") (pintype "passive"))
      (node (ref "K21") (pin "9") (pinfunction "9_9") (pintype "passive"))
      (node (ref "K22") (pin "13") (pinfunction "13_13") (pintype "passive"))
      (node (ref "K22") (pin "4") (pinfunction "4_4") (pintype "passive"))
    )
    (net (code "212") (name "Net-(P2-Pad1)") (class "Default")
      (node (ref "P2") (pin "1") (pinfunction "1_1") (pintype "passive"))
      (node (ref "S1") (pin "1") (pinfunction "1_1") (pintype "passive"))
    )
    (net (code "213") (name "Net-(P2-Pad2)") (class "Default")
      (node (ref "P2") (pin "2") (pinfunction "2_2") (pintype "passive"))
      (node (ref "S1") (pin "2") (pinfunction "2_2") (pintype "passive"))
    )
    (net (code "214") (name "Net-(P5-Pad1)") (class "Default")
      (node (ref "P5") (pin "1") (pinfunction "1_1") (pintype "passive"))
      (node (ref "R20") (pin "1") (pinfunction "1_1") (pintype "passive"))
    )
    (net (code "215") (name "Net-(P10-IO)") (class "Default")
      (node (ref "P10") (pin "2") (pinfunction "IO_2") (pintype "passive"))
      (node (ref "P13") (pin "2") (pinfunction "IO_2") (pintype "passive"))
      (node (ref "Q5") (pin "3") (pinfunction "D_3") (pintype "passive"))
      (node (ref "R73") (pin "2") (pinfunction "2_2") (pintype "passive"))
      (node (ref "U16") (pin "2") (pinfunction "IO_2") (pintype "passive"))
    )
    (net (code "216") (name "Net-(P17-AN)") (class "Default")
      (node (ref "P17") (pin "1") (pinfunction "AN_1") (pintype "passive"))
      (node (ref "R93") (pin "2") (pinfunction "2_2") (pintype "passive"))
    )
    (net (code "217") (name "Net-(P18-AN)") (class "Default")
      (node (ref "P18") (pin "1") (pinfunction "AN_1") (pintype "passive"))
      (node (ref "R103") (pin "2") (pinfunction "2_2") (pintype "passive"))
    )
    (net (code "218") (name "Net-(P20-AN)") (class "Default")
      (node (ref "P20") (pin "1") (pinfunction "AN_1") (pintype "passive"))
      (node (ref "R106") (pin "2") (pinfunction "2_2") (pintype "passive"))
    )
    (net (code "219") (name "Net-(P22-Pad1)") (class "Default")
      (node (ref "P22") (pin "1") (pinfunction "1_1") (pintype "passive"))
      (node (ref "R113") (pin "2") (pinfunction "2_2") (pintype "passive"))
    )
    (net (code "220") (name "Net-(P22-Pad5)") (class "Default")
      (node (ref "P22") (pin "5") (pinfunction "5_5") (pintype "passive"))
      (node (ref "R116") (pin "1") (pinfunction "1_1") (pintype "passive"))
    )
    (net (code "221") (name "Net-(Q1-G)") (class "Default")
      (node (ref "Q1") (pin "1") (pinfunction "G_1") (pintype "passive"))
      (node (ref "R17") (pin "2") (pinfunction "2_2") (pintype "passive"))
      (node (ref "U6") (pin "7") (pinfunction "SQW/OUT_7") (pintype "passive"))
    )
    (net (code "222") (name "Net-(Q5-G)") (class "Default")
      (node (ref "Q5") (pin "1") (pinfunction "G_1") (pintype "passive"))
      (node (ref "U16") (pin "6") (pinfunction "PCTLZ_6") (pintype "passive"))
    )
    (net (code "223") (name "Net-(Q5-S)") (class "Default")
      (node (ref "Q5") (pin "2") (pinfunction "S_2") (pintype "passive"))
      (node (ref "R60") (pin "2") (pinfunction "2_2") (pintype "passive"))
      (node (ref "R73") (pin "1") (pinfunction "1_1") (pintype "passive"))
    )
    (net (code "224") (name "Net-(Q6-B)") (class "Default")
      (node (ref "Q6") (pin "1") (pinfunction "B_1") (pintype "passive"))
      (node (ref "Q7") (pin "1") (pinfunction "B_1") (pintype "passive"))
      (node (ref "Q8") (pin "1") (pinfunction "B_1") (pintype "passive"))
      (node (ref "R18") (pin "2") (pinfunction "2_2") (pintype "passive"))
      (node (ref "S2") (pin "1") (pinfunction "1_1") (pintype "passive"))
    )
    (net (code "225") (name "Net-(Q9-B)") (class "Default")
      (node (ref "Q9") (pin "1") (pinfunction "B_1") (pintype "passive"))
      (node (ref "R128") (pin "1") (pinfunction "1_1") (pintype "passive"))
    )
    (net (code "226") (name "Net-(Q9-E)") (class "Default")
      (node (ref "Q9") (pin "2") (pinfunction "E_2") (pintype "passive"))
      (node (ref "U36") (pin "4") (pinfunction "C_4") (pintype "passive"))
    )
    (net (code "227") (name "Net-(Q10-C)") (class "Default")
      (node (ref "Q10") (pin "3") (pinfunction "C_3") (pintype "passive"))
      (node (ref "R127") (pin "1") (pinfunction "1_1") (pintype "passive"))
      (node (ref "R128") (pin "2") (pinfunction "2_2") (pintype "passive"))
    )
    (net (code "228") (name "Net-(R33-Pad2)") (class "Default")
      (node (ref "R33") (pin "2") (pinfunction "2_2") (pintype "passive"))
      (node (ref "U7") (pin "1") (pinfunction "AN/CAT_1") (pintype "passive"))
    )
    (net (code "229") (name "Net-(R34-Pad2)") (class "Default")
      (node (ref "R34") (pin "2") (pinfunction "2_2") (pintype "passive"))
      (node (ref "U8") (pin "1") (pinfunction "AN/CAT_1") (pintype "passive"))
    )
    (net (code "230") (name "Net-(R48-Pad2)") (class "Default")
      (node (ref "R48") (pin "2") (pinfunction "2_2") (pintype "passive"))
      (node (ref "U9") (pin "1") (pinfunction "AN/CAT_1") (pintype "passive"))
    )
    (net (code "231") (name "Net-(R49-Pad2)") (class "Default")
      (node (ref "R49") (pin "2") (pinfunction "2_2") (pintype "passive"))
      (node (ref "U10") (pin "1") (pinfunction "AN/CAT_1") (pintype "passive"))
    )
    (net (code "232") (name "Net-(R63-Pad2)") (class "Default")
      (node (ref "R63") (pin "2") (pinfunction "2_2") (pintype "passive"))
      (node (ref "U14") (pin "1") (pinfunction "AN/CAT_1") (pintype "passive"))
    )
    (net (code "233") (name "Net-(R64-Pad2)") (class "Default")
      (node (ref "R64") (pin "2") (pinfunction "2_2") (pintype "passive"))
      (node (ref "U15") (pin "1") (pinfunction "AN/CAT_1") (pintype "passive"))
    )
    (net (code "234") (name "Net-(R78-Pad2)") (class "Default")
      (node (ref "R78") (pin "2") (pinfunction "2_2") (pintype "passive"))
      (node (ref "U19") (pin "1") (pinfunction "AN/CAT_1") (pintype "passive"))
    )
    (net (code "235") (name "Net-(R79-Pad2)") (class "Default")
      (node (ref "R79") (pin "2") (pinfunction "2_2") (pintype "passive"))
      (node (ref "U20") (pin "1") (pinfunction "AN/CAT_1") (pintype "passive"))
    )
    (net (code "236") (name "Net-(R82-Pad2)") (class "Default")
      (node (ref "R82") (pin "2") (pinfunction "2_2") (pintype "passive"))
      (node (ref "U21") (pin "1") (pinfunction "AN/CAT_1") (pintype "passive"))
    )
    (net (code "237") (name "Net-(R83-Pad2)") (class "Default")
      (node (ref "R83") (pin "2") (pinfunction "2_2") (pintype "passive"))
      (node (ref "U22") (pin "1") (pinfunction "AN/CAT_1") (pintype "passive"))
    )
    (net (code "238") (name "Net-(U2-GPA4)") (class "Default")
      (node (ref "R7") (pin "1") (pinfunction "1_1") (pintype "passive"))
      (node (ref "U2") (pin "25") (pinfunction "GPA4_25") (pintype "passive"))
    )
    (net (code "239") (name "Net-(U2-GPA5)") (class "Default")
      (node (ref "R8") (pin "1") (pinfunction "1_1") (pintype "passive"))
      (node (ref "U2") (pin "26") (pinfunction "GPA5_26") (pintype "passive"))
    )
    (net (code "240") (name "Net-(U2-{slash}RESET)") (class "Default")
      (node (ref "R4") (pin "2") (pinfunction "2_2") (pintype "passive"))
      (node (ref "U2") (pin "18") (pinfunction "/RESET_18") (pintype "passive"))
    )
    (net (code "241") (name "Net-(U4-{slash}RESET)") (class "Default")
      (node (ref "R12") (pin "2") (pinfunction "2_2") (pintype "passive"))
      (node (ref "U4") (pin "18") (pinfunction "/RESET_18") (pintype "passive"))
    )
    (net (code "242") (name "Net-(U6-VBAT)") (class "Default")
      (node (ref "BAT1") (pin "1") (pinfunction "1_1") (pintype "passive"))
      (node (ref "U6") (pin "3") (pinfunction "VBAT_3") (pintype "passive"))
    )
    (net (code "243") (name "Net-(U6-X1)") (class "Default")
      (node (ref "BQ1") (pin "1") (pintype "passive"))
      (node (ref "U6") (pin "1") (pinfunction "X1_1") (pintype "passive"))
    )
    (net (code "244") (name "Net-(U6-X2)") (class "Default")
      (node (ref "BQ1") (pin "4") (pintype "passive"))
      (node (ref "U6") (pin "2") (pinfunction "X2_2") (pintype "passive"))
    )
    (net (code "245") (name "Net-(U11-Y1)") (class "Default")
      (node (ref "R52") (pin "2") (pinfunction "2_2") (pintype "passive"))
      (node (ref "U11") (pin "23") (pinfunction "Y1_23") (pintype "passive"))
    )
    (net (code "246") (name "Net-(U11-Y2)") (class "Default")
      (node (ref "R53") (pin "2") (pinfunction "2_2") (pintype "passive"))
      (node (ref "U11") (pin "22") (pinfunction "Y2_22") (pintype "passive"))
    )
    (net (code "247") (name "Net-(U11-Y3)") (class "Default")
      (node (ref "R54") (pin "2") (pinfunction "2_2") (pintype "passive"))
      (node (ref "U11") (pin "21") (pinfunction "Y3_21") (pintype "passive"))
    )
    (net (code "248") (name "Net-(U11-Y4)") (class "Default")
      (node (ref "R55") (pin "2") (pinfunction "2_2") (pintype "passive"))
      (node (ref "U11") (pin "20") (pinfunction "Y4_20") (pintype "passive"))
    )
    (net (code "249") (name "Net-(U11-Y5)") (class "Default")
      (node (ref "R72") (pin "1") (pinfunction "1_1") (pintype "passive"))
      (node (ref "U11") (pin "19") (pinfunction "Y5_19") (pintype "passive"))
    )
    (net (code "250") (name "Net-(U11-Y6)") (class "Default")
      (node (ref "R71") (pin "1") (pinfunction "1_1") (pintype "passive"))
      (node (ref "U11") (pin "18") (pinfunction "Y6_18") (pintype "passive"))
    )
    (net (code "251") (name "Net-(U11-Y7)") (class "Default")
      (node (ref "R70") (pin "1") (pinfunction "1_1") (pintype "passive"))
      (node (ref "U11") (pin "17") (pinfunction "Y7_17") (pintype "passive"))
    )
    (net (code "252") (name "Net-(U11-Y8)") (class "Default")
      (node (ref "R69") (pin "1") (pinfunction "1_1") (pintype "passive"))
      (node (ref "U11") (pin "16") (pinfunction "Y8_16") (pintype "passive"))
    )
    (net (code "253") (name "Net-(U11-Y9)") (class "Default")
      (node (ref "R68") (pin "1") (pinfunction "1_1") (pintype "passive"))
      (node (ref "U11") (pin "15") (pinfunction "Y9_15") (pintype "passive"))
    )
    (net (code "254") (name "Net-(U11-Y10)") (class "Default")
      (node (ref "R67") (pin "1") (pinfunction "1_1") (pintype "passive"))
      (node (ref "U11") (pin "14") (pinfunction "Y10_14") (pintype "passive"))
    )
    (net (code "255") (name "Net-(U25-Y1)") (class "Default")
      (node (ref "R84") (pin "2") (pinfunction "2_2") (pintype "passive"))
      (node (ref "U25") (pin "23") (pinfunction "Y1_23") (pintype "passive"))
    )
    (net (code "256") (name "Net-(U25-Y2)") (class "Default")
      (node (ref "R85") (pin "2") (pinfunction "2_2") (pintype "passive"))
      (node (ref "U25") (pin "22") (pinfunction "Y2_22") (pintype "passive"))
    )
    (net (code "257") (name "Net-(U25-Y3)") (class "Default")
      (node (ref "R86") (pin "2") (pinfunction "2_2") (pintype "passive"))
      (node (ref "U25") (pin "21") (pinfunction "Y3_21") (pintype "passive"))
    )
    (net (code "258") (name "Net-(U25-Y4)") (class "Default")
      (node (ref "R87") (pin "2") (pinfunction "2_2") (pintype "passive"))
      (node (ref "U25") (pin "20") (pinfunction "Y4_20") (pintype "passive"))
    )
    (net (code "259") (name "Net-(U25-Y5)") (class "Default")
      (node (ref "R99") (pin "1") (pinfunction "1_1") (pintype "passive"))
      (node (ref "U25") (pin "19") (pinfunction "Y5_19") (pintype "passive"))
    )
    (net (code "260") (name "Net-(U25-Y6)") (class "Default")
      (node (ref "R98") (pin "1") (pinfunction "1_1") (pintype "passive"))
      (node (ref "U25") (pin "18") (pinfunction "Y6_18") (pintype "passive"))
    )
    (net (code "261") (name "Net-(U25-Y7)") (class "Default")
      (node (ref "R97") (pin "1") (pinfunction "1_1") (pintype "passive"))
      (node (ref "U25") (pin "17") (pinfunction "Y7_17") (pintype "passive"))
    )
    (net (code "262") (name "Net-(U25-Y8)") (class "Default")
      (node (ref "R96") (pin "1") (pinfunction "1_1") (pintype "passive"))
      (node (ref "U25") (pin "16") (pinfunction "Y8_16") (pintype "passive"))
    )
    (net (code "263") (name "Net-(U26-IN1_(+))") (class "Default")
      (node (ref "R6") (pin "2") (pinfunction "2_2") (pintype "passive"))
      (node (ref "U26") (pin "3") (pinfunction "IN1_(+)_3") (pintype "passive"))
      (node (ref "U40") (pin "1") (pinfunction "C_1") (pintype "passive"))
    )
    (net (code "264") (name "Net-(U26-IN1_(-))") (class "Default")
      (node (ref "C42") (pin "1") (pinfunction "1_1") (pintype "passive"))
      (node (ref "R5") (pin "1") (pinfunction "1_1") (pintype "passive"))
      (node (ref "R94") (pin "1") (pinfunction "1_1") (pintype "passive"))
      (node (ref "U26") (pin "2") (pinfunction "IN1_(-)_2") (pintype "passive"))
    )
    (net (code "265") (name "Net-(U26-IN2_(+))") (class "Default")
      (node (ref "C42") (pin "2") (pinfunction "2_2") (pintype "passive"))
      (node (ref "R118") (pin "2") (pinfunction "2_2") (pintype "passive"))
      (node (ref "R5") (pin "2") (pinfunction "2_2") (pintype "passive"))
      (node (ref "U26") (pin "1") (pinfunction "OUT1_1") (pintype "passive"))
      (node (ref "U26") (pin "5") (pinfunction "IN2_(+)_5") (pintype "passive"))
    )
    (net (code "266") (name "Net-(U26-IN2_(-))") (class "Default")
      (node (ref "U26") (pin "6") (pinfunction "IN2_(-)_6") (pintype "passive"))
      (node (ref "U29") (pin "1") (pinfunction "W_1") (pintype "passive"))
    )
    (net (code "267") (name "Net-(U26-OUT2)") (class "Default")
      (node (ref "R120") (pin "2") (pinfunction "2_2") (pintype "passive"))
      (node (ref "U26") (pin "7") (pinfunction "OUT2_7") (pintype "passive"))
    )
    (net (code "268") (name "Net-(U27-Y1)") (class "Default")
      (node (ref "R88") (pin "2") (pinfunction "2_2") (pintype "passive"))
      (node (ref "U27") (pin "23") (pinfunction "Y1_23") (pintype "passive"))
    )
    (net (code "269") (name "Net-(U27-Y2)") (class "Default")
      (node (ref "R89") (pin "2") (pinfunction "2_2") (pintype "passive"))
      (node (ref "U27") (pin "22") (pinfunction "Y2_22") (pintype "passive"))
    )
    (net (code "270") (name "Net-(U27-Y3)") (class "Default")
      (node (ref "R90") (pin "2") (pinfunction "2_2") (pintype "passive"))
      (node (ref "U27") (pin "21") (pinfunction "Y3_21") (pintype "passive"))
    )
    (net (code "271") (name "Net-(U27-Y4)") (class "Default")
      (node (ref "R91") (pin "2") (pinfunction "2_2") (pintype "passive"))
      (node (ref "U27") (pin "20") (pinfunction "Y4_20") (pintype "passive"))
    )
    (net (code "272") (name "Net-(U27-Y5)") (class "Default")
      (node (ref "R102") (pin "1") (pinfunction "1_1") (pintype "passive"))
      (node (ref "U27") (pin "19") (pinfunction "Y5_19") (pintype "passive"))
    )
    (net (code "273") (name "Net-(U27-Y6)") (class "Default")
      (node (ref "R101") (pin "1") (pinfunction "1_1") (pintype "passive"))
      (node (ref "U27") (pin "18") (pinfunction "Y6_18") (pintype "passive"))
    )
    (net (code "274") (name "Net-(U27-Y7)") (class "Default")
      (node (ref "R100") (pin "1") (pinfunction "1_1") (pintype "passive"))
      (node (ref "U27") (pin "17") (pinfunction "Y7_17") (pintype "passive"))
    )
    (net (code "275") (name "Net-(U28-IN1(+))") (class "Default")
      (node (ref "C52") (pin "2") (pinfunction "2_2") (pintype "passive"))
      (node (ref "R93") (pin "1") (pinfunction "1_1") (pintype "passive"))
      (node (ref "R95") (pin "1") (pinfunction "1_1") (pintype "passive"))
      (node (ref "U28") (pin "3") (pinfunction "IN1(+)_3") (pintype "passive"))
    )
    (net (code "276") (name "Net-(U28-IN2(+))") (class "Default")
      (node (ref "C56") (pin "2") (pinfunction "2_2") (pintype "passive"))
      (node (ref "R103") (pin "1") (pinfunction "1_1") (pintype "passive"))
      (node (ref "R104") (pin "1") (pinfunction "1_1") (pintype "passive"))
      (node (ref "U28") (pin "5") (pinfunction "IN2(+)_5") (pintype "passive"))
    )
    (net (code "277") (name "Net-(U28-IN3(+))") (class "Default")
      (node (ref "C58") (pin "2") (pinfunction "2_2") (pintype "passive"))
      (node (ref "R106") (pin "1") (pinfunction "1_1") (pintype "passive"))
      (node (ref "R107") (pin "1") (pinfunction "1_1") (pintype "passive"))
      (node (ref "U28") (pin "10") (pinfunction "IN3(+)_10") (pintype "passive"))
    )
    (net (code "278") (name "Net-(U30-QS0)") (class "Default")
      (node (ref "U30") (pin "9") (pinfunction "QS0_9") (pintype "passive"))
      (node (ref "U34") (pin "2") (pinfunction "IN_2") (pintype "passive"))
    )
    (net (code "279") (name "Net-(U31-REF)") (class "Default")
      (node (ref "C67") (pin "2") (pinfunction "2_2") (pintype "passive"))
      (node (ref "C68") (pin "2") (pinfunction "2_2") (pintype "passive"))
      (node (ref "C69") (pin "2") (pinfunction "2_2") (pintype "passive"))
      (node (ref "U31") (pin "6") (pinfunction "REF_6") (pintype "passive"))
      (node (ref "U33") (pin "5") (pinfunction "VREF_5") (pintype "passive"))
    )
    (net (code "280") (name "Net-(U32-FB)") (class "Default")
      (node (ref "R109") (pin "2") (pinfunction "2_2") (pintype "passive"))
      (node (ref "R110") (pin "2") (pinfunction "2_2") (pintype "passive"))
      (node (ref "U32") (pin "4") (pinfunction "FB_4") (pintype "passive"))
    )
    (net (code "281") (name "Net-(U34-QS0)") (class "Default")
      (node (ref "U34") (pin "9") (pinfunction "QS0_9") (pintype "passive"))
      (node (ref "U39") (pin "2") (pinfunction "IN_2") (pintype "passive"))
    )
    (net (code "282") (name "Net-(U36-R)") (class "Default")
      (node (ref "R112") (pin "2") (pinfunction "2_2") (pintype "passive"))
      (node (ref "U36") (pin "3") (pinfunction "R_3") (pintype "passive"))
    )
    (net (code "283") (name "Net-(U37-FB)") (class "Default")
      (node (ref "R114") (pin "2") (pinfunction "2_2") (pintype "passive"))
      (node (ref "R115") (pin "2") (pinfunction "2_2") (pintype "passive"))
      (node (ref "U37") (pin "4") (pinfunction "FB_4") (pintype "passive"))
    )
    (net (code "284") (name "Net-(U38-INL+)") (class "Default")
      (node (ref "C80") (pin "1") (pinfunction "1_1") (pintype "passive"))
      (node (ref "U38") (pin "3") (pinfunction "INL+_3") (pintype "passive"))
    )
    (net (code "285") (name "Net-(U38-INL-)") (class "Default")
      (node (ref "C89") (pin "1") (pinfunction "1_1") (pintype "passive"))
      (node (ref "U38") (pin "4") (pinfunction "INL-_4") (pintype "passive"))
    )
    (net (code "286") (name "Net-(U38-INR+)") (class "Default")
      (node (ref "C82") (pin "1") (pinfunction "1_1") (pintype "passive"))
      (node (ref "U38") (pin "7") (pinfunction "INR+_7") (pintype "passive"))
    )
    (net (code "287") (name "Net-(U38-INR-)") (class "Default")
      (node (ref "C90") (pin "1") (pinfunction "1_1") (pintype "passive"))
      (node (ref "U38") (pin "6") (pinfunction "INR-_6") (pintype "passive"))
    )
    (net (code "288") (name "Net-(U38-OUTL+)") (class "Default")
      (node (ref "P25") (pin "2") (pinfunction "2_2") (pintype "passive"))
      (node (ref "U38") (pin "13") (pinfunction "OUTL+_13") (pintype "passive"))
    )
    (net (code "289") (name "Net-(U38-OUTL-)") (class "Default")
      (node (ref "P25") (pin "1") (pinfunction "1_1") (pintype "passive"))
      (node (ref "U38") (pin "14") (pinfunction "OUTL-_14") (pintype "passive"))
    )
    (net (code "290") (name "Net-(U38-OUTR+)") (class "Default")
      (node (ref "P26") (pin "1") (pinfunction "1_1") (pintype "passive"))
      (node (ref "U38") (pin "10") (pinfunction "OUTR+_10") (pintype "passive"))
    )
    (net (code "291") (name "Net-(U38-OUTR-)") (class "Default")
      (node (ref "P26") (pin "2") (pinfunction "2_2") (pintype "passive"))
      (node (ref "U38") (pin "9") (pinfunction "OUTR-_9") (pintype "passive"))
    )
    (net (code "292") (name "Net-(U40-W)") (class "Default")
      (node (ref "C44") (pin "1") (pinfunction "1_1") (pintype "passive"))
      (node (ref "R119") (pin "2") (pinfunction "2_2") (pintype "passive"))
      (node (ref "R122") (pin "1") (pinfunction "1_1") (pintype "passive"))
      (node (ref "R6") (pin "1") (pinfunction "1_1") (pintype "passive"))
      (node (ref "R94") (pin "2") (pinfunction "2_2") (pintype "passive"))
      (node (ref "U40") (pin "0") (pinfunction "W_0") (pintype "passive"))
    )
    (net (code "293") (name "unconnected-(K2-Pad6)") (class "Default")
      (node (ref "K2") (pin "6") (pinfunction "6_6") (pintype "passive+no_connect"))
    )
    (net (code "294") (name "unconnected-(K2-Pad11)") (class "Default")
      (node (ref "K2") (pin "11") (pinfunction "11_11") (pintype "passive+no_connect"))
    )
    (net (code "295") (name "unconnected-(K3-Pad6)") (class "Default")
      (node (ref "K3") (pin "6") (pinfunction "6_6") (pintype "passive+no_connect"))
    )
    (net (code "296") (name "unconnected-(K3-Pad11)") (class "Default")
      (node (ref "K3") (pin "11") (pinfunction "11_11") (pintype "passive+no_connect"))
    )
    (net (code "297") (name "unconnected-(K5-Pad6)") (class "Default")
      (node (ref "K5") (pin "6") (pinfunction "6_6") (pintype "passive+no_connect"))
    )
    (net (code "298") (name "unconnected-(K5-Pad11)") (class "Default")
      (node (ref "K5") (pin "11") (pinfunction "11_11") (pintype "passive+no_connect"))
    )
    (net (code "299") (name "unconnected-(K8-Pad6)") (class "Default")
      (node (ref "K8") (pin "6") (pinfunction "6_6") (pintype "passive+no_connect"))
    )
    (net (code "300") (name "unconnected-(K8-Pad11)") (class "Default")
      (node (ref "K8") (pin "11") (pinfunction "11_11") (pintype "passive+no_connect"))
    )
    (net (code "301") (name "unconnected-(K10-Pad6)") (class "Default")
      (node (ref "K10") (pin "6") (pinfunction "6_6") (pintype "passive+no_connect"))
    )
    (net (code "302") (name "unconnected-(K10-Pad11)") (class "Default")
      (node (ref "K10") (pin "11") (pinfunction "11_11") (pintype "passive+no_connect"))
    )
    (net (code "303") (name "unconnected-(K11-Pad6)") (class "Default")
      (node (ref "K11") (pin "6") (pinfunction "6_6") (pintype "passive+no_connect"))
    )
    (net (code "304") (name "unconnected-(K11-Pad11)") (class "Default")
      (node (ref "K11") (pin "11") (pinfunction "11_11") (pintype "passive+no_connect"))
    )
    (net (code "305") (name "unconnected-(K12-Pad6)") (class "Default")
      (node (ref "K12") (pin "6") (pinfunction "6_6") (pintype "passive+no_connect"))
    )
    (net (code "306") (name "unconnected-(K12-Pad11)") (class "Default")
      (node (ref "K12") (pin "11") (pinfunction "11_11") (pintype "passive+no_connect"))
    )
    (net (code "307") (name "unconnected-(K14-Pad6)") (class "Default")
      (node (ref "K14") (pin "6") (pinfunction "6_6") (pintype "passive+no_connect"))
    )
    (net (code "308") (name "unconnected-(K14-Pad11)") (class "Default")
      (node (ref "K14") (pin "11") (pinfunction "11_11") (pintype "passive+no_connect"))
    )
    (net (code "309") (name "unconnected-(K15-Pad6)") (class "Default")
      (node (ref "K15") (pin "6") (pinfunction "6_6") (pintype "passive+no_connect"))
    )
    (net (code "310") (name "unconnected-(K15-Pad11)") (class "Default")
      (node (ref "K15") (pin "11") (pinfunction "11_11") (pintype "passive+no_connect"))
    )
    (net (code "311") (name "unconnected-(K16-Pad6)") (class "Default")
      (node (ref "K16") (pin "6") (pinfunction "6_6") (pintype "passive+no_connect"))
    )
    (net (code "312") (name "unconnected-(K16-Pad11)") (class "Default")
      (node (ref "K16") (pin "11") (pinfunction "11_11") (pintype "passive+no_connect"))
    )
    (net (code "313") (name "unconnected-(K18-Pad6)") (class "Default")
      (node (ref "K18") (pin "6") (pinfunction "6_6") (pintype "passive+no_connect"))
    )
    (net (code "314") (name "unconnected-(K18-Pad11)") (class "Default")
      (node (ref "K18") (pin "11") (pinfunction "11_11") (pintype "passive+no_connect"))
    )
    (net (code "315") (name "unconnected-(K19-Pad6)") (class "Default")
      (node (ref "K19") (pin "6") (pinfunction "6_6") (pintype "passive+no_connect"))
    )
    (net (code "316") (name "unconnected-(K19-Pad11)") (class "Default")
      (node (ref "K19") (pin "11") (pinfunction "11_11") (pintype "passive+no_connect"))
    )
    (net (code "317") (name "unconnected-(K20-Pad6)") (class "Default")
      (node (ref "K20") (pin "6") (pinfunction "6_6") (pintype "passive+no_connect"))
    )
    (net (code "318") (name "unconnected-(K20-Pad11)") (class "Default")
      (node (ref "K20") (pin "11") (pinfunction "11_11") (pintype "passive+no_connect"))
    )
    (net (code "319") (name "unconnected-(K22-Pad6)") (class "Default")
      (node (ref "K22") (pin "6") (pinfunction "6_6") (pintype "passive+no_connect"))
    )
    (net (code "320") (name "unconnected-(K22-Pad11)") (class "Default")
      (node (ref "K22") (pin "11") (pinfunction "11_11") (pintype "passive+no_connect"))
    )
    (net (code "321") (name "unconnected-(LS2-Pad1)") (class "Default")
      (node (ref "LS2") (pin "1") (pinfunction "1_1") (pintype "passive"))
    )
    (net (code "322") (name "unconnected-(LS2-Pad2)") (class "Default")
      (node (ref "LS2") (pin "2") (pinfunction "2_2") (pintype "passive"))
    )
    (net (code "323") (name "unconnected-(LS3-Pad1)") (class "Default")
      (node (ref "LS3") (pin "1") (pinfunction "1_1") (pintype "passive"))
    )
    (net (code "324") (name "unconnected-(LS3-Pad2)") (class "Default")
      (node (ref "LS3") (pin "2") (pinfunction "2_2") (pintype "passive"))
    )
    (net (code "325") (name "unconnected-(P1-Pad12)") (class "Default")
      (node (ref "P1") (pin "12") (pinfunction "12_12") (pintype "passive+no_connect"))
    )
    (net (code "326") (name "unconnected-(P5-Pad17)") (class "Default")
      (node (ref "P5") (pin "17") (pinfunction "17_17") (pintype "passive+no_connect"))
    )
    (net (code "327") (name "unconnected-(P19-Pad5)") (class "Default")
      (node (ref "P19") (pin "5") (pinfunction "5_5") (pintype "passive+no_connect"))
    )
    (net (code "328") (name "unconnected-(P19-Pad30)") (class "Default")
      (node (ref "P19") (pin "30") (pinfunction "30_30") (pintype "passive+no_connect"))
    )
    (net (code "329") (name "unconnected-(P19-Pad31)") (class "Default")
      (node (ref "P19") (pin "31") (pinfunction "31_31") (pintype "passive+no_connect"))
    )
    (net (code "330") (name "unconnected-(P19-Pad32)") (class "Default")
      (node (ref "P19") (pin "32") (pinfunction "32_32") (pintype "passive+no_connect"))
    )
    (net (code "331") (name "unconnected-(P19-Pad34)") (class "Default")
      (node (ref "P19") (pin "34") (pinfunction "34_34") (pintype "passive+no_connect"))
    )
    (net (code "332") (name "unconnected-(P19-Pad35)") (class "Default")
      (node (ref "P19") (pin "35") (pinfunction "35_35") (pintype "passive+no_connect"))
    )
    (net (code "333") (name "unconnected-(P19-Pad36)") (class "Default")
      (node (ref "P19") (pin "36") (pinfunction "36_36") (pintype "passive+no_connect"))
    )
    (net (code "334") (name "unconnected-(P19-Pad38)") (class "Default")
      (node (ref "P19") (pin "38") (pinfunction "38_38") (pintype "passive+no_connect"))
    )
    (net (code "335") (name "unconnected-(P19-Pad39)") (class "Default")
      (node (ref "P19") (pin "39") (pinfunction "39_39") (pintype "passive+no_connect"))
    )
    (net (code "336") (name "unconnected-(P19-Pad40)") (class "Default")
      (node (ref "P19") (pin "40") (pinfunction "40_40") (pintype "passive+no_connect"))
    )
    (net (code "337") (name "unconnected-(U1-OUT8-Pad10)") (class "Default")
      (node (ref "U1") (pin "10") (pinfunction "OUT8_10") (pintype "passive+no_connect"))
    )
    (net (code "338") (name "unconnected-(U2-INTA-Pad20)") (class "Default")
      (node (ref "U2") (pin "20") (pinfunction "INTA_20") (pintype "passive+no_connect"))
    )
    (net (code "339") (name "unconnected-(U2-INTB-Pad19)") (class "Default")
      (node (ref "U2") (pin "19") (pinfunction "INTB_19") (pintype "passive+no_connect"))
    )
    (net (code "340") (name "unconnected-(U2-NC-Pad11)") (class "Default")
      (node (ref "U2") (pin "11") (pinfunction "NC_11") (pintype "passive+no_connect"))
    )
    (net (code "341") (name "unconnected-(U2-NC-Pad14)") (class "Default")
      (node (ref "U2") (pin "14") (pinfunction "NC_14") (pintype "passive+no_connect"))
    )
    (net (code "342") (name "unconnected-(U4-NC-Pad11)") (class "Default")
      (node (ref "U4") (pin "11") (pinfunction "NC_11") (pintype "passive+no_connect"))
    )
    (net (code "343") (name "unconnected-(U4-NC-Pad14)") (class "Default")
      (node (ref "U4") (pin "14") (pinfunction "NC_14") (pintype "passive+no_connect"))
    )
    (net (code "344") (name "unconnected-(U5-OUT2-Pad19)") (class "Default")
      (node (ref "U5") (pin "19") (pinfunction "OUT2_19") (pintype "passive+no_connect"))
    )
    (net (code "345") (name "unconnected-(U25-A9-Pad10)") (class "Default")
      (node (ref "U25") (pin "10") (pinfunction "A9_10") (pintype "passive+no_connect"))
    )
    (net (code "346") (name "unconnected-(U25-A10-Pad11)") (class "Default")
      (node (ref "U25") (pin "11") (pinfunction "A10_11") (pintype "passive+no_connect"))
    )
    (net (code "347") (name "unconnected-(U25-Y9-Pad15)") (class "Default")
      (node (ref "U25") (pin "15") (pinfunction "Y9_15") (pintype "passive+no_connect"))
    )
    (net (code "348") (name "unconnected-(U25-Y10-Pad14)") (class "Default")
      (node (ref "U25") (pin "14") (pinfunction "Y10_14") (pintype "passive+no_connect"))
    )
    (net (code "349") (name "unconnected-(U27-A8-Pad9)") (class "Default")
      (node (ref "U27") (pin "9") (pinfunction "A8_9") (pintype "passive+no_connect"))
    )
    (net (code "350") (name "unconnected-(U27-A9-Pad10)") (class "Default")
      (node (ref "U27") (pin "10") (pinfunction "A9_10") (pintype "passive+no_connect"))
    )
    (net (code "351") (name "unconnected-(U27-A10-Pad11)") (class "Default")
      (node (ref "U27") (pin "11") (pinfunction "A10_11") (pintype "passive+no_connect"))
    )
    (net (code "352") (name "unconnected-(U27-Y8-Pad16)") (class "Default")
      (node (ref "U27") (pin "16") (pinfunction "Y8_16") (pintype "passive+no_connect"))
    )
    (net (code "353") (name "unconnected-(U27-Y9-Pad15)") (class "Default")
      (node (ref "U27") (pin "15") (pinfunction "Y9_15") (pintype "passive+no_connect"))
    )
    (net (code "354") (name "unconnected-(U27-Y10-Pad14)") (class "Default")
      (node (ref "U27") (pin "14") (pinfunction "Y10_14") (pintype "passive+no_connect"))
    )
    (net (code "355") (name "unconnected-(U28-IN4(+)-Pad12)") (class "Default")
      (node (ref "U28") (pin "12") (pinfunction "IN4(+)_12") (pintype "passive+no_connect"))
    )
    (net (code "356") (name "unconnected-(U28-IN4(-)-Pad13)") (class "Default")
      (node (ref "U28") (pin "13") (pinfunction "IN4(-)_13") (pintype "passive+no_connect"))
    )
    (net (code "357") (name "unconnected-(U28-OUT4-Pad14)") (class "Default")
      (node (ref "U28") (pin "14") (pinfunction "OUT4_14") (pintype "passive"))
    )
    (net (code "358") (name "unconnected-(U30-QS1-Pad10)") (class "Default")
      (node (ref "U30") (pin "10") (pinfunction "QS1_10") (pintype "passive+no_connect"))
    )
    (net (code "359") (name "unconnected-(U33-N{slash}C-Pad1)") (class "Default")
      (node (ref "U33") (pin "1") (pinfunction "N/C_1") (pintype "passive+no_connect"))
    )
    (net (code "360") (name "unconnected-(U34-QS1-Pad10)") (class "Default")
      (node (ref "U34") (pin "10") (pinfunction "QS1_10") (pintype "passive+no_connect"))
    )
    (net (code "361") (name "unconnected-(U35-Q1-Pad9)") (class "Default")
      (node (ref "U35") (pin "9") (pinfunction "Q1_9") (pintype "passive+no_connect"))
    )
    (net (code "362") (name "unconnected-(U35-Q2-Pad7)") (class "Default")
      (node (ref "U35") (pin "7") (pinfunction "Q2_7") (pintype "passive+no_connect"))
    )
    (net (code "363") (name "unconnected-(U35-Q3-Pad6)") (class "Default")
      (node (ref "U35") (pin "6") (pinfunction "Q3_6") (pintype "passive+no_connect"))
    )
    (net (code "364") (name "unconnected-(U35-Q4-Pad5)") (class "Default")
      (node (ref "U35") (pin "5") (pinfunction "Q4_5") (pintype "passive+no_connect"))
    )
    (net (code "365") (name "unconnected-(U35-Q6-Pad2)") (class "Default")
      (node (ref "U35") (pin "2") (pinfunction "Q6_2") (pintype "passive+no_connect"))
    )
    (net (code "366") (name "unconnected-(U35-Q7-Pad4)") (class "Default")
      (node (ref "U35") (pin "4") (pinfunction "Q7_4") (pintype "passive+no_connect"))
    )
    (net (code "367") (name "unconnected-(U35-Q8-Pad13)") (class "Default")
      (node (ref "U35") (pin "13") (pinfunction "Q8_13") (pintype "passive+no_connect"))
    )
    (net (code "368") (name "unconnected-(U35-Q9-Pad12)") (class "Default")
      (node (ref "U35") (pin "12") (pinfunction "Q9_12") (pintype "passive+no_connect"))
    )
    (net (code "369") (name "unconnected-(U35-Q10-Pad14)") (class "Default")
      (node (ref "U35") (pin "14") (pinfunction "Q10_14") (pintype "passive+no_connect"))
    )
    (net (code "370") (name "unconnected-(U35-Q11-Pad15)") (class "Default")
      (node (ref "U35") (pin "15") (pinfunction "Q11_15") (pintype "passive+no_connect"))
    )
    (net (code "371") (name "unconnected-(U35-Q12-Pad1)") (class "Default")
      (node (ref "U35") (pin "1") (pinfunction "Q12_1") (pintype "passive+no_connect"))
    )
    (net (code "372") (name "unconnected-(U39-O8-Pad11)") (class "Default")
      (node (ref "U39") (pin "11") (pinfunction "O8_11") (pintype "passive+no_connect"))
    )
    (net (code "373") (name "unconnected-(U39-Q3-Pad6)") (class "Default")
      (node (ref "U39") (pin "6") (pinfunction "Q3_6") (pintype "passive+no_connect"))
    )
    (net (code "374") (name "unconnected-(U39-Q6-Pad13)") (class "Default")
      (node (ref "U39") (pin "13") (pinfunction "Q6_13") (pintype "passive+no_connect"))
    )
    (net (code "375") (name "unconnected-(U39-Q7-Pad12)") (class "Default")
      (node (ref "U39") (pin "12") (pinfunction "Q7_12") (pintype "passive+no_connect"))
    )
    (net (code "376") (name "unconnected-(U39-QS0-Pad9)") (class "Default")
      (node (ref "U39") (pin "9") (pinfunction "QS0_9") (pintype "passive+no_connect"))
    )
    (net (code "377") (name "unconnected-(U39-QS1-Pad10)") (class "Default")
      (node (ref "U39") (pin "10") (pinfunction "QS1_10") (pintype "passive+no_connect"))
    )
  )
)
